# JTAG_-V1_6-ASCII.net
KiCad netlist of a schematic drawn in Altium Designer
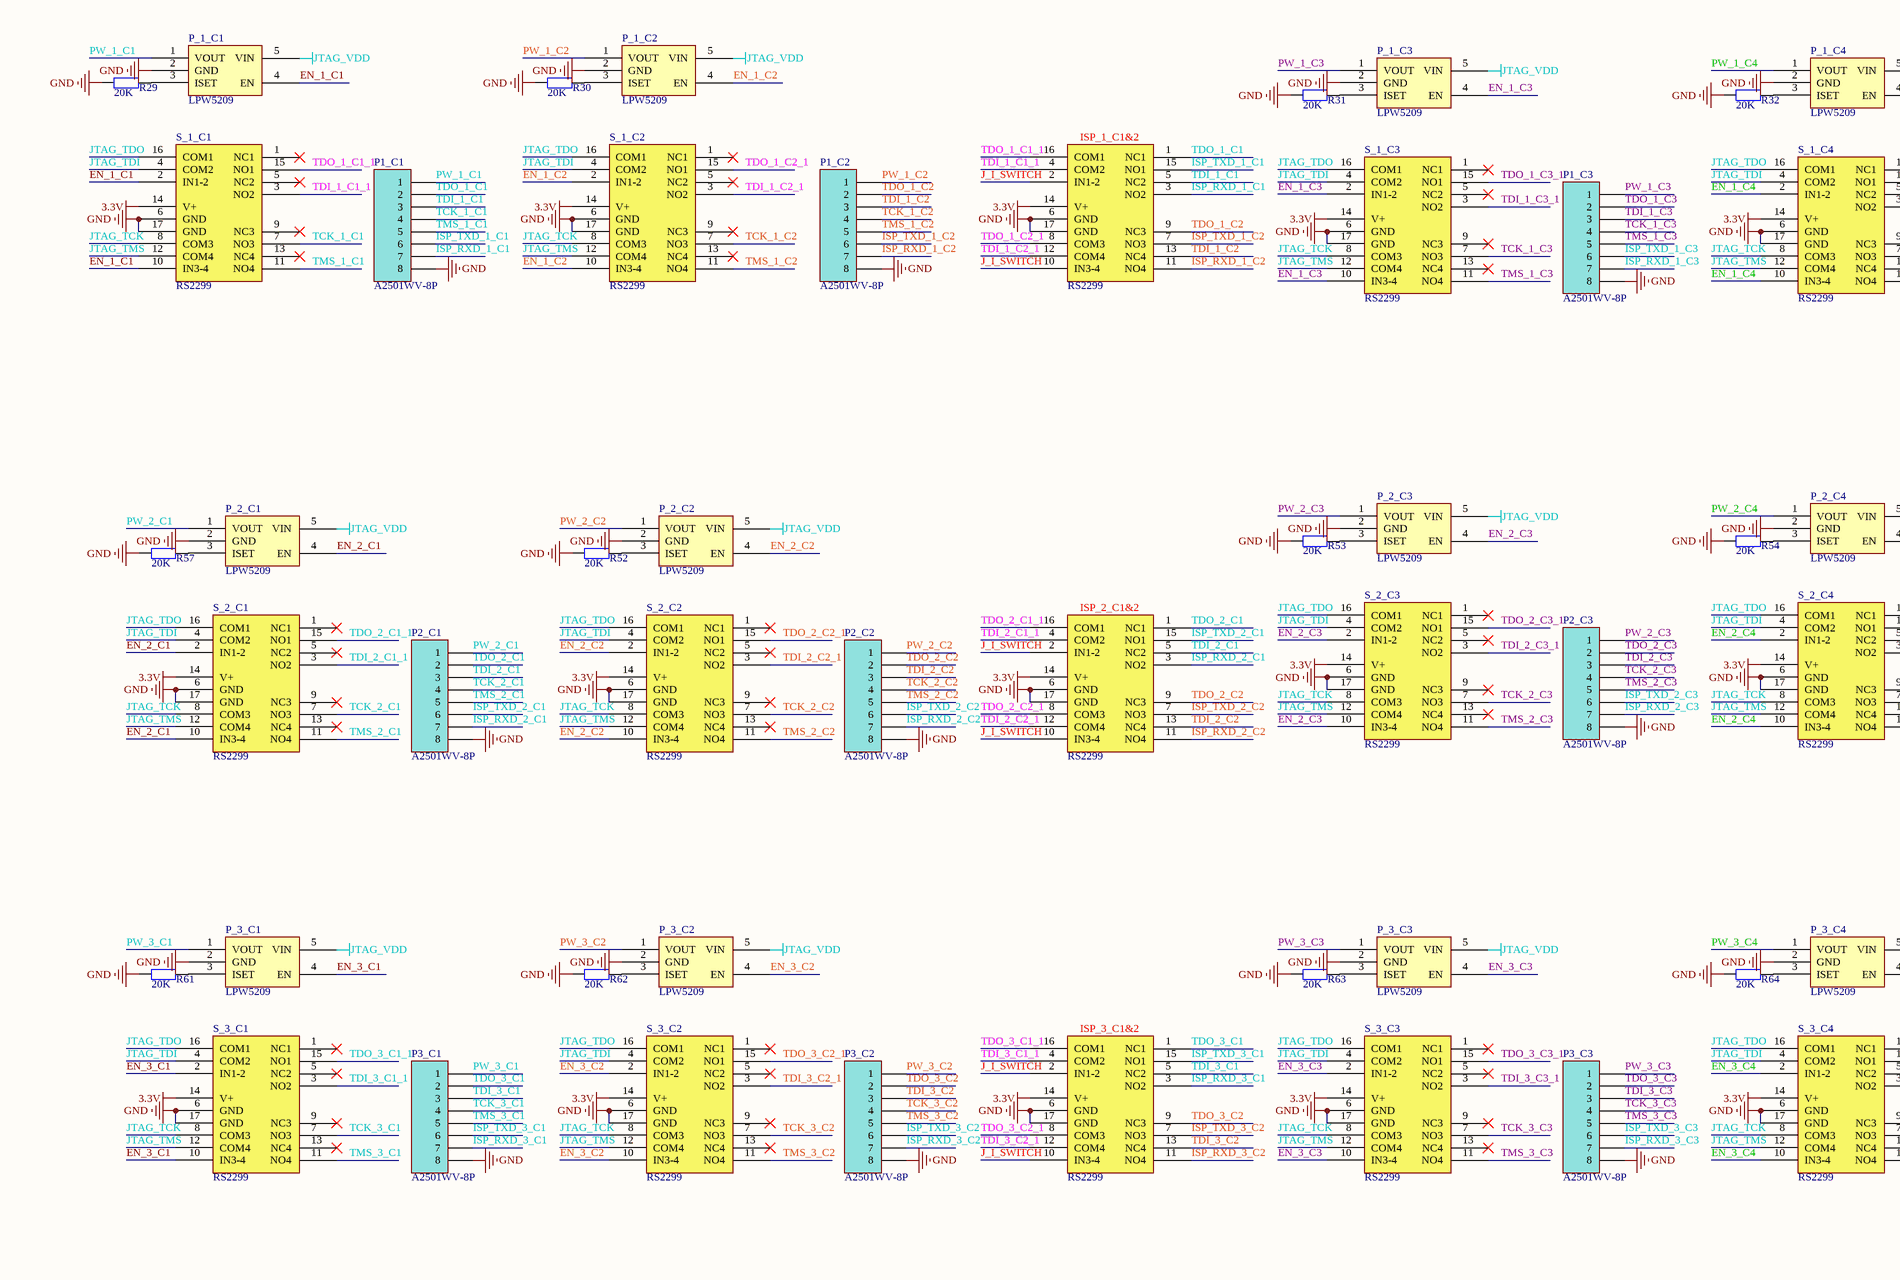
[diagram p0: JTAG批量下载板-V1.6-ASCII.SchDoc, top left]
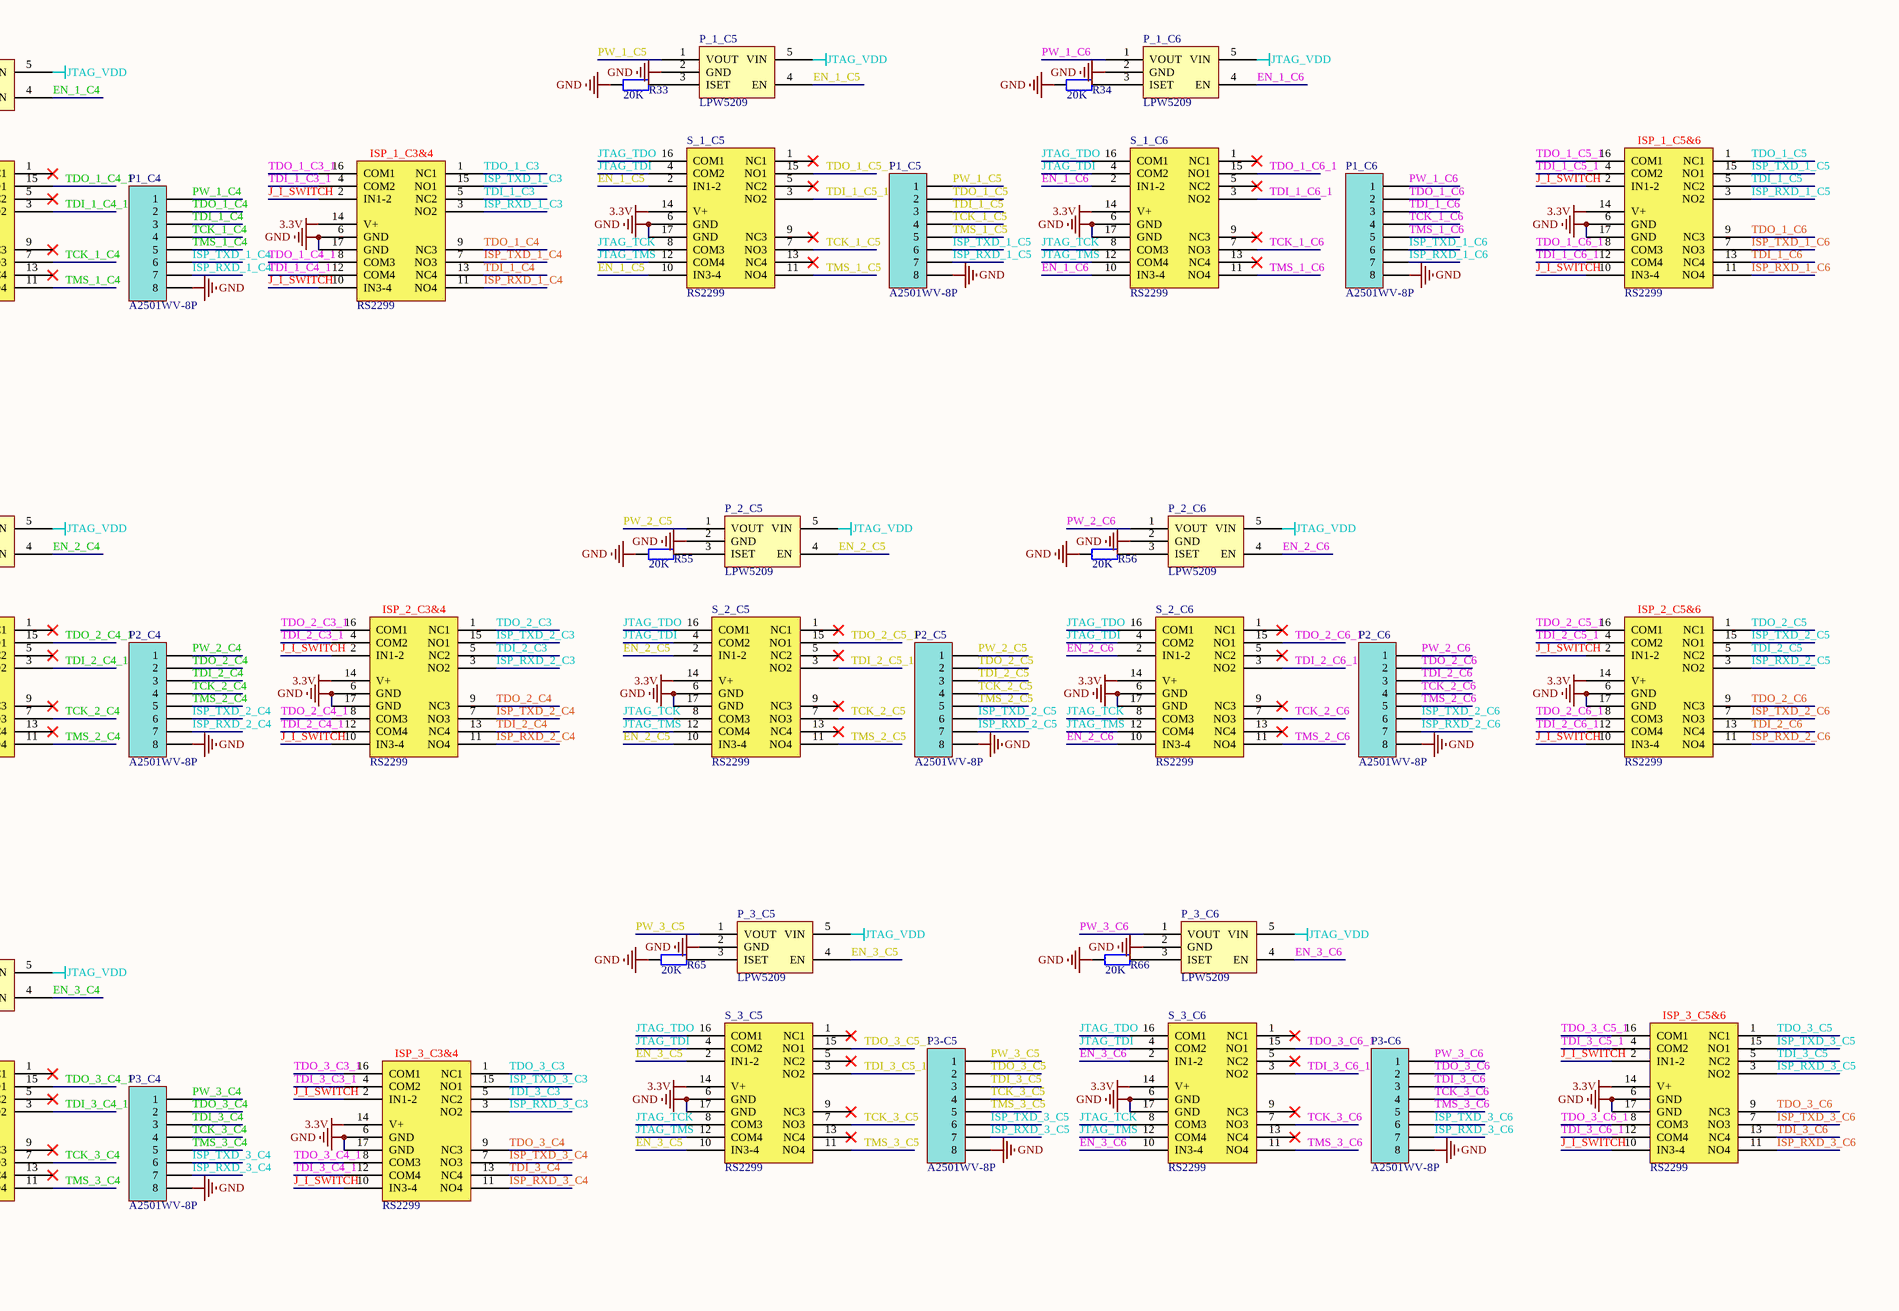
[diagram p1: JTAG批量下载板-V1.6-ASCII.SchDoc, top right]
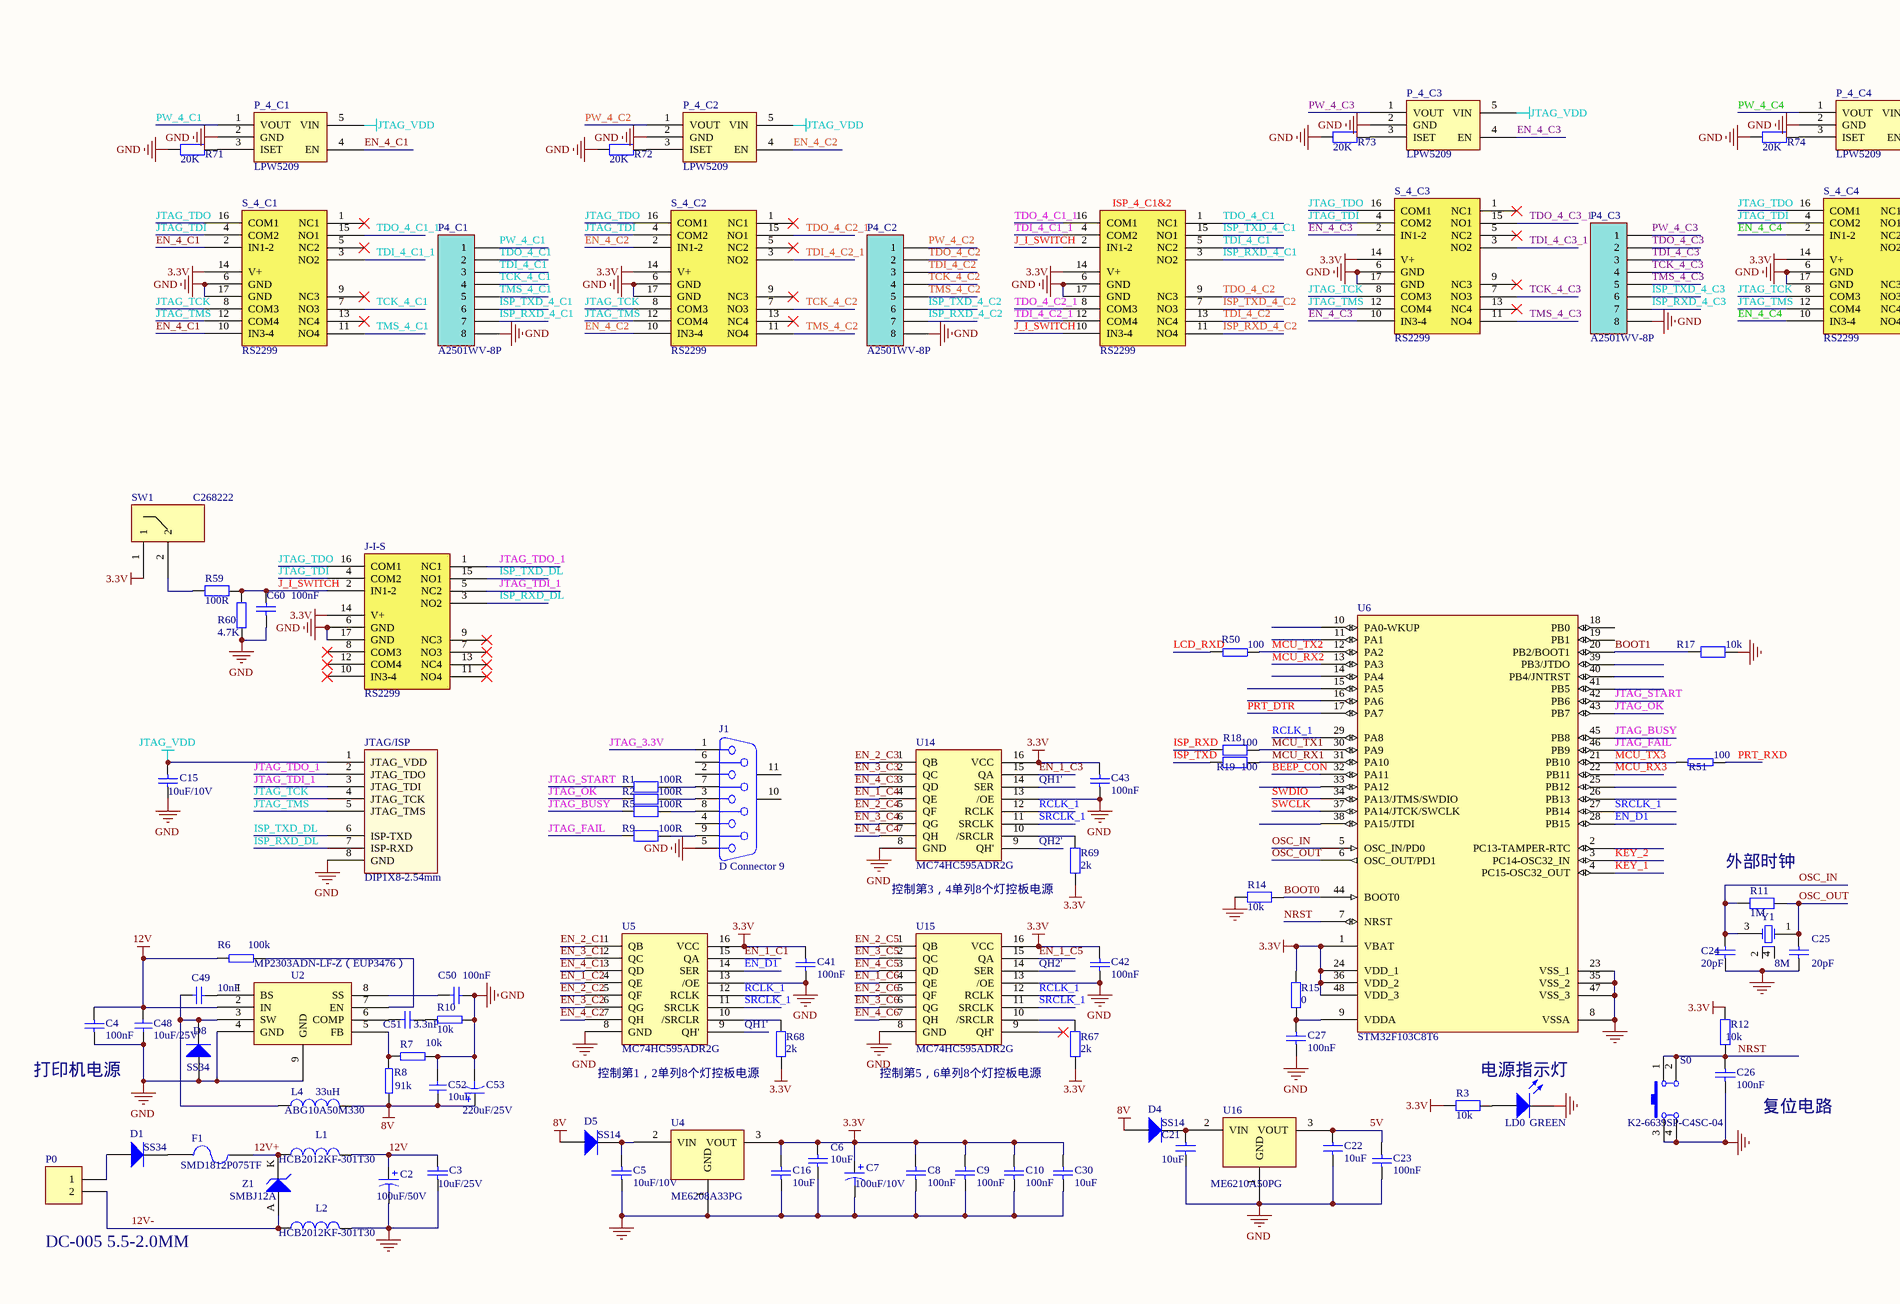
[diagram p2: JTAG批量下载板-V1.6-ASCII.SchDoc, bottom left]
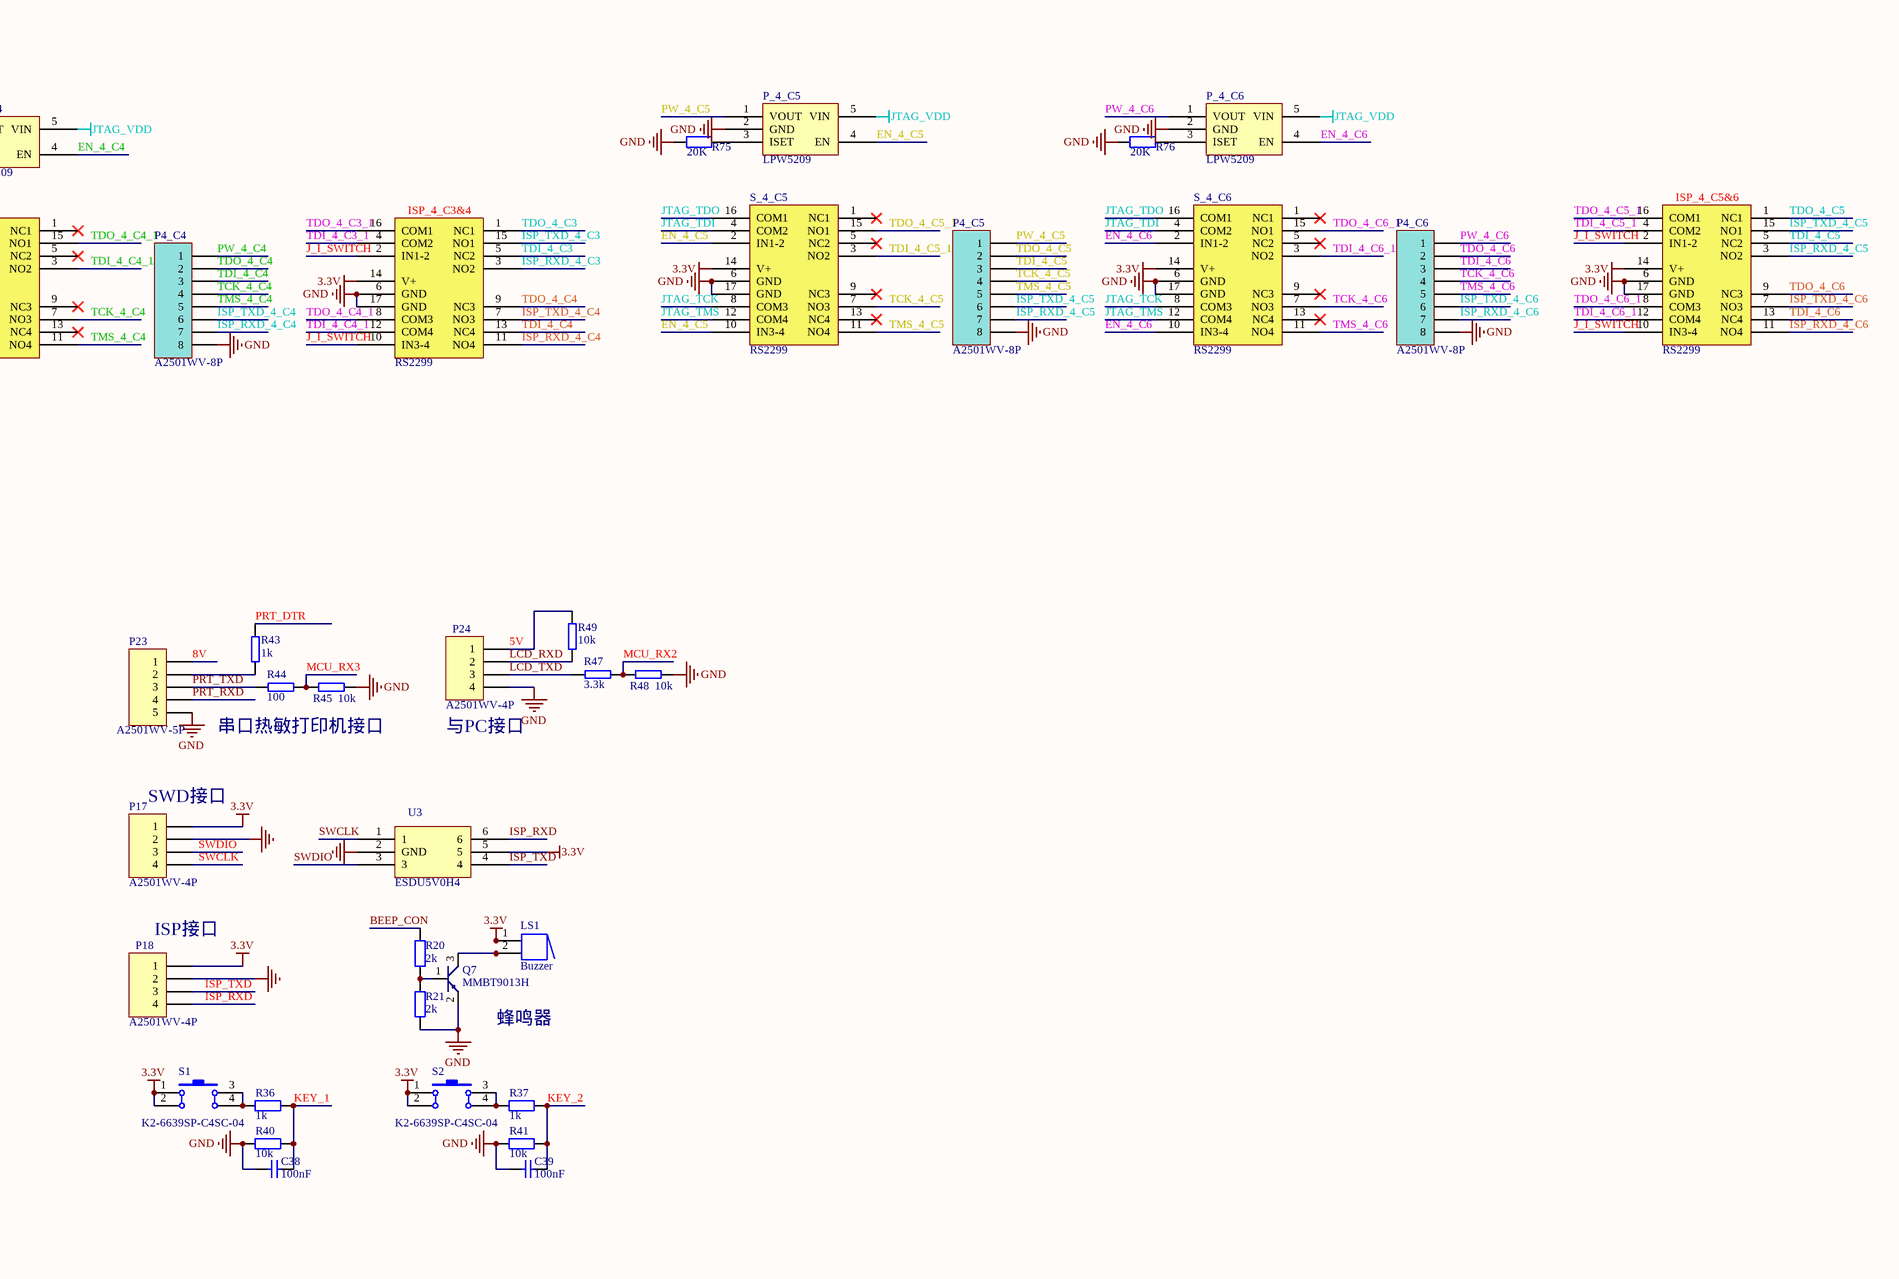
[diagram p3: JTAG批量下载板-V1.6-ASCII.SchDoc, bottom right]

(export (version "E")
  (design (tool "Eeschema 10.0.6"))
  (components
    (comp (ref "C2")
      (value "100uF/50V")
      (footprint "RB-6*9")
      (description "Polarized Capacitor (Radial)")
      (fields (field (name "PUBLISHER") "Altium Limited"))
      (libsource (lib "Miscellaneous Devices") (part "Cap Pol1"))
    )
    (comp (ref "C3")
      (value "10uF/25V")
      (footprint "C0805")
      (description "Capacitor")
      (fields (field (name "PUBLISHER") "Altium Limited"))
      (libsource (lib "Miscellaneous Devices") (part "Cap"))
    )
    (comp (ref "C4")
      (value "100nF")
      (footprint "C0603")
      (description "Capacitor")
      (fields (field (name "PUBLISHER") "Altium Limited"))
      (libsource (lib "Miscellaneous Devices") (part "Cap"))
    )
    (comp (ref "C5")
      (value "10uF/10V")
      (footprint "C0603")
      (description "Capacitor")
      (fields (field (name "PUBLISHER") "Altium Limited"))
      (libsource (lib "Miscellaneous Devices") (part "Cap"))
    )
    (comp (ref "C6")
      (value "10uF")
      (footprint "C0603")
      (description "Capacitor")
      (fields (field (name "PUBLISHER") "Altium Limited"))
      (libsource (lib "Miscellaneous Devices") (part "Cap"))
    )
    (comp (ref "C7")
      (value "100uF/10V")
      (footprint "C3528")
      (description "Polarized Capacitor (Radial)")
      (fields (field (name "PUBLISHER") "Altium Limited"))
      (libsource (lib "Miscellaneous Devices") (part "Cap Pol1"))
    )
    (comp (ref "C8")
      (value "100nF")
      (footprint "C0603")
      (description "Capacitor")
      (fields (field (name "PUBLISHER") "Altium Limited"))
      (libsource (lib "Miscellaneous Devices") (part "Cap"))
    )
    (comp (ref "C9")
      (value "100nF")
      (footprint "C0603")
      (description "Capacitor")
      (fields (field (name "PUBLISHER") "Altium Limited"))
      (libsource (lib "Miscellaneous Devices") (part "Cap"))
    )
    (comp (ref "C10")
      (value "100nF")
      (footprint "C0603")
      (description "Capacitor")
      (fields (field (name "PUBLISHER") "Altium Limited"))
      (libsource (lib "Miscellaneous Devices") (part "Cap"))
    )
    (comp (ref "C15")
      (value "10uF/10V")
      (footprint "C0603")
      (description "Capacitor")
      (fields (field (name "PUBLISHER") "Altium Limited"))
      (libsource (lib "Miscellaneous Devices") (part "Cap"))
    )
    (comp (ref "C16")
      (value "10uF")
      (footprint "C0603")
      (description "Capacitor")
      (fields (field (name "PUBLISHER") "Altium Limited"))
      (libsource (lib "Miscellaneous Devices") (part "Cap"))
    )
    (comp (ref "C21")
      (value "10uF")
      (footprint "C0603")
      (description "Capacitor")
      (fields (field (name "PUBLISHER") "Altium Limited"))
      (libsource (lib "Miscellaneous Devices") (part "Cap"))
    )
    (comp (ref "C22")
      (value "10uF")
      (footprint "C0603")
      (description "Capacitor")
      (fields (field (name "PUBLISHER") "Altium Limited"))
      (libsource (lib "Miscellaneous Devices") (part "Cap"))
    )
    (comp (ref "C23")
      (value "100nF")
      (footprint "C0603")
      (description "Capacitor")
      (fields (field (name "PUBLISHER") "Altium Limited"))
      (libsource (lib "Miscellaneous Devices") (part "Cap"))
    )
    (comp (ref "C24")
      (value "20pF")
      (footprint "C0603")
      (description "Capacitor")
      (fields (field (name "PUBLISHER") "Altium Limited"))
      (libsource (lib "Miscellaneous Devices") (part "Cap"))
    )
    (comp (ref "C25")
      (value "20pF")
      (footprint "C0603")
      (description "Capacitor")
      (fields (field (name "PUBLISHER") "Altium Limited"))
      (libsource (lib "Miscellaneous Devices") (part "Cap"))
    )
    (comp (ref "C26")
      (value "100nF")
      (footprint "C0603")
      (description "Capacitor")
      (fields (field (name "PUBLISHER") "Altium Limited"))
      (libsource (lib "Miscellaneous Devices") (part "Cap"))
    )
    (comp (ref "C27")
      (value "100nF")
      (footprint "C0603")
      (description "Capacitor")
      (fields (field (name "PUBLISHER") "Altium Limited"))
      (libsource (lib "Miscellaneous Devices") (part "Cap"))
    )
    (comp (ref "C30")
      (value "10uF")
      (footprint "C0603")
      (description "Capacitor")
      (fields (field (name "PUBLISHER") "Altium Limited"))
      (libsource (lib "Miscellaneous Devices") (part "Cap"))
    )
    (comp (ref "C38")
      (value "100nF")
      (footprint "C0603")
      (description "电容器")
      (libsource (lib "*") (part "Capacitor"))
    )
    (comp (ref "C39")
      (value "100nF")
      (footprint "C0603")
      (description "电容器")
      (libsource (lib "*") (part "Capacitor"))
    )
    (comp (ref "C41")
      (value "100nF")
      (footprint "C0603")
      (description "Capacitor")
      (fields (field (name "PUBLISHER") "Altium Limited"))
      (libsource (lib "Miscellaneous Devices") (part "Cap"))
    )
    (comp (ref "C42")
      (value "100nF")
      (footprint "C0603")
      (description "Capacitor")
      (fields (field (name "PUBLISHER") "Altium Limited"))
      (libsource (lib "Miscellaneous Devices") (part "Cap"))
    )
    (comp (ref "C43")
      (value "100nF")
      (footprint "C0603")
      (description "Capacitor")
      (fields (field (name "PUBLISHER") "Altium Limited"))
      (libsource (lib "Miscellaneous Devices") (part "Cap"))
    )
    (comp (ref "C48")
      (value "10uF/25V")
      (footprint "C0805")
      (description "电容器")
      (libsource (lib "*") (part "Capacitor"))
    )
    (comp (ref "C49")
      (value "10nF")
      (footprint "C0603")
      (description "电容器")
      (libsource (lib "*") (part "Capacitor"))
    )
    (comp (ref "C50")
      (value "100nF")
      (footprint "C0603")
      (description "电容器")
      (libsource (lib "*") (part "Capacitor"))
    )
    (comp (ref "C51")
      (value "3.3nF")
      (footprint "C0603")
      (description "电容器")
      (libsource (lib "*") (part "Capacitor"))
    )
    (comp (ref "C52")
      (value "10uF")
      (footprint "C0603")
      (description "电容器")
      (libsource (lib "*") (part "Capacitor"))
    )
    (comp (ref "C53")
      (value "220uF/25V")
      (footprint "RB-6*9")
      (description "Polarized Capacitor (Radial)")
      (fields (field (name "PUBLISHER") "Altium Limited"))
      (libsource (lib "Miscellaneous Devices") (part "Cap Pol1"))
    )
    (comp (ref "C60")
      (value "100nF")
      (footprint "C0603")
      (description "Capacitor")
      (fields (field (name "PUBLISHER") "Altium Limited"))
      (libsource (lib "Miscellaneous Devices") (part "Cap"))
    )
    (comp (ref "D1")
      (value "SS34")
      (footprint "SMB")
      (description "1 Amp General Purpose Rectifier")
      (fields (field (name "PUBLISHER") "Altium Limited"))
      (libsource (lib "Miscellaneous Devices") (part "Diode 1N4001"))
    )
    (comp (ref "D4")
      (value "SS14")
      (footprint "SOD-123F")
      (description "1 Amp General Purpose Rectifier")
      (fields (field (name "PUBLISHER") "Altium Limited"))
      (libsource (lib "Miscellaneous Devices") (part "Diode 1N4001"))
    )
    (comp (ref "D5")
      (value "SS14")
      (footprint "SOD-123F")
      (description "1 Amp General Purpose Rectifier")
      (fields (field (name "PUBLISHER") "Altium Limited"))
      (libsource (lib "Miscellaneous Devices") (part "Diode 1N4001"))
    )
    (comp (ref "D8")
      (value "SS34")
      (footprint "SMB")
      (description "通用二极管")
      (fields (field (name "PUBLISHER") "Altium Limited"))
      (libsource (lib "*") (part "Diode"))
    )
    (comp (ref "F1")
      (value "SMD1812P075TF")
      (footprint "1812")
      (description "Fuse")
      (fields (field (name "PUBLISHER") "Altium Limited"))
      (libsource (lib "Miscellaneous Devices") (part "Fuse 2"))
    )
    (comp (ref "ISP_1_C1&2")
      (value "RS2299")
      (footprint "QFN16")
      (libsource (lib "JTAG批量下载板-V0.5") (part "RS2299"))
    )
    (comp (ref "ISP_1_C3&4")
      (value "RS2299")
      (footprint "QFN16")
      (libsource (lib "JTAG批量下载板-V0.5") (part "RS2299"))
    )
    (comp (ref "ISP_1_C5&6")
      (value "RS2299")
      (footprint "QFN16")
      (libsource (lib "JTAG批量下载板-V0.5") (part "RS2299"))
    )
    (comp (ref "ISP_2_C1&2")
      (value "RS2299")
      (footprint "QFN16")
      (libsource (lib "JTAG批量下载板-V0.5") (part "RS2299"))
    )
    (comp (ref "ISP_2_C3&4")
      (value "RS2299")
      (footprint "QFN16")
      (libsource (lib "JTAG批量下载板-V0.5") (part "RS2299"))
    )
    (comp (ref "ISP_2_C5&6")
      (value "RS2299")
      (footprint "QFN16")
      (libsource (lib "JTAG批量下载板-V0.5") (part "RS2299"))
    )
    (comp (ref "ISP_3_C1&2")
      (value "RS2299")
      (footprint "QFN16")
      (libsource (lib "JTAG批量下载板-V0.5") (part "RS2299"))
    )
    (comp (ref "ISP_3_C3&4")
      (value "RS2299")
      (footprint "QFN16")
      (libsource (lib "JTAG批量下载板-V0.5") (part "RS2299"))
    )
    (comp (ref "ISP_3_C5&6")
      (value "RS2299")
      (footprint "QFN16")
      (libsource (lib "JTAG批量下载板-V0.5") (part "RS2299"))
    )
    (comp (ref "ISP_4_C1&2")
      (value "RS2299")
      (footprint "QFN16")
      (libsource (lib "JTAG批量下载板-V0.5") (part "RS2299"))
    )
    (comp (ref "ISP_4_C3&4")
      (value "RS2299")
      (footprint "QFN16")
      (libsource (lib "JTAG批量下载板-V0.5") (part "RS2299"))
    )
    (comp (ref "ISP_4_C5&6")
      (value "RS2299")
      (footprint "QFN16")
      (libsource (lib "JTAG批量下载板-V0.5") (part "RS2299"))
    )
    (comp (ref "J-I-S")
      (value "RS2299")
      (footprint "QFN16")
      (libsource (lib "JTAG批量下载板-V0.5") (part "RS2299"))
    )
    (comp (ref "J1")
      (value "D Connector 9")
      (footprint "DSUB1.385-2H9")
      (description "Receptacle Assembly, 9 Position, Right Angle")
      (fields (field (name "PUBLISHER") "Altium Limited"))
      (libsource (lib "Miscellaneous Connectors") (part "D Connector 9"))
    )
    (comp (ref "JTAG/ISP")
      (value "DIP1X8-2.54mm")
      (footprint "XH2.5-8P")
      (libsource (lib "JTAG批量下载板-V1.0") (part "DIP1X6-2.54mm"))
    )
    (comp (ref "L1")
      (value "HCB2012KF-301T30")
      (footprint "R0805")
      (description "Inductor")
      (fields (field (name "PUBLISHER") "Altium Limited"))
      (libsource (lib "Miscellaneous Devices") (part "Inductor"))
    )
    (comp (ref "L2")
      (value "HCB2012KF-301T30")
      (footprint "R0805")
      (description "Inductor")
      (fields (field (name "PUBLISHER") "Altium Limited"))
      (libsource (lib "Miscellaneous Devices") (part "Inductor"))
    )
    (comp (ref "L4")
      (value "33uH")
      (footprint "L1040")
      (description "Inductor")
      (fields (field (name "ALTIUM_VALUE") "ABG10A50M330") (field (name "PUBLISHER") "Altium Limited"))
      (libsource (lib "") (part "Inductor_1"))
    )
    (comp (ref "LD0")
      (value "GREEN")
      (footprint "LED-0603")
      (description "LED灯")
      (fields (field (name "PUBLISHER") "Altium Limited"))
      (libsource (lib "*") (part "LED0"))
    )
    (comp (ref "LS1")
      (value "Buzzer")
      (footprint "BUZZER-small")
      (description "Magnetic Transducer Buzzer")
      (fields (field (name "PUBLISHER") "Altium Limited"))
      (libsource (lib "JTAG-1") (part "Buzzer"))
    )
    (comp (ref "P0")
      (value "DC-005 5.5-2.0MM")
      (footprint "DC-005A")
      (description "Header, 2-Pin")
      (fields (field (name "PUBLISHER") "Altium Limited"))
      (libsource (lib "Miscellaneous Connectors") (part "Header 2"))
    )
    (comp (ref "P1_C1")
      (value "A2501WV-8P")
      (footprint "XH2.5-8P")
      (description "Header, 6-Pin")
      (fields (field (name "PUBLISHER") "Altium Limited"))
      (libsource (lib "JTAG批量下载板-V1.0") (part "Header 8"))
    )
    (comp (ref "P1_C2")
      (value "A2501WV-8P")
      (footprint "XH2.5-8P")
      (description "Header, 6-Pin")
      (fields (field (name "PUBLISHER") "Altium Limited"))
      (libsource (lib "JTAG批量下载板-V1.0") (part "Header 8"))
    )
    (comp (ref "P1_C3")
      (value "A2501WV-8P")
      (footprint "XH2.5-8P")
      (description "Header, 6-Pin")
      (fields (field (name "PUBLISHER") "Altium Limited"))
      (libsource (lib "JTAG批量下载板-V1.0") (part "Header 8"))
    )
    (comp (ref "P1_C4")
      (value "A2501WV-8P")
      (footprint "XH2.5-8P")
      (description "Header, 6-Pin")
      (fields (field (name "PUBLISHER") "Altium Limited"))
      (libsource (lib "JTAG批量下载板-V1.0") (part "Header 8"))
    )
    (comp (ref "P1_C5")
      (value "A2501WV-8P")
      (footprint "XH2.5-8P")
      (description "Header, 6-Pin")
      (fields (field (name "PUBLISHER") "Altium Limited"))
      (libsource (lib "JTAG批量下载板-V1.0") (part "Header 8"))
    )
    (comp (ref "P1_C6")
      (value "A2501WV-8P")
      (footprint "XH2.5-8P")
      (description "Header, 6-Pin")
      (fields (field (name "PUBLISHER") "Altium Limited"))
      (libsource (lib "JTAG批量下载板-V1.0") (part "Header 8"))
    )
    (comp (ref "P2_C1")
      (value "A2501WV-8P")
      (footprint "XH2.5-8P")
      (description "Header, 6-Pin")
      (fields (field (name "PUBLISHER") "Altium Limited"))
      (libsource (lib "JTAG批量下载板-V1.0") (part "Header 8"))
    )
    (comp (ref "P2_C2")
      (value "A2501WV-8P")
      (footprint "XH2.5-8P")
      (description "Header, 6-Pin")
      (fields (field (name "PUBLISHER") "Altium Limited"))
      (libsource (lib "JTAG批量下载板-V1.0") (part "Header 8"))
    )
    (comp (ref "P2_C3")
      (value "A2501WV-8P")
      (footprint "XH2.5-8P")
      (description "Header, 6-Pin")
      (fields (field (name "PUBLISHER") "Altium Limited"))
      (libsource (lib "JTAG批量下载板-V1.0") (part "Header 8"))
    )
    (comp (ref "P2_C4")
      (value "A2501WV-8P")
      (footprint "XH2.5-8P")
      (description "Header, 6-Pin")
      (fields (field (name "PUBLISHER") "Altium Limited"))
      (libsource (lib "JTAG批量下载板-V1.0") (part "Header 8"))
    )
    (comp (ref "P2_C5")
      (value "A2501WV-8P")
      (footprint "XH2.5-8P")
      (description "Header, 6-Pin")
      (fields (field (name "PUBLISHER") "Altium Limited"))
      (libsource (lib "JTAG批量下载板-V1.0") (part "Header 8"))
    )
    (comp (ref "P2_C6")
      (value "A2501WV-8P")
      (footprint "XH2.5-8P")
      (description "Header, 6-Pin")
      (fields (field (name "PUBLISHER") "Altium Limited"))
      (libsource (lib "JTAG批量下载板-V1.0") (part "Header 8"))
    )
    (comp (ref "P3-C5")
      (value "A2501WV-8P")
      (footprint "XH2.5-8P")
      (description "Header, 6-Pin")
      (fields (field (name "PUBLISHER") "Altium Limited"))
      (libsource (lib "JTAG批量下载板-V1.0") (part "Header 8"))
    )
    (comp (ref "P3-C6")
      (value "A2501WV-8P")
      (footprint "XH2.5-8P")
      (description "Header, 6-Pin")
      (fields (field (name "PUBLISHER") "Altium Limited"))
      (libsource (lib "JTAG批量下载板-V1.0") (part "Header 8"))
    )
    (comp (ref "P3_C1")
      (value "A2501WV-8P")
      (footprint "XH2.5-8P")
      (description "Header, 6-Pin")
      (fields (field (name "PUBLISHER") "Altium Limited"))
      (libsource (lib "JTAG批量下载板-V1.0") (part "Header 8"))
    )
    (comp (ref "P3_C2")
      (value "A2501WV-8P")
      (footprint "XH2.5-8P")
      (description "Header, 6-Pin")
      (fields (field (name "PUBLISHER") "Altium Limited"))
      (libsource (lib "JTAG批量下载板-V1.0") (part "Header 8"))
    )
    (comp (ref "P3_C3")
      (value "A2501WV-8P")
      (footprint "XH2.5-8P")
      (description "Header, 6-Pin")
      (fields (field (name "PUBLISHER") "Altium Limited"))
      (libsource (lib "JTAG批量下载板-V1.0") (part "Header 8"))
    )
    (comp (ref "P3_C4")
      (value "A2501WV-8P")
      (footprint "XH2.5-8P")
      (description "Header, 6-Pin")
      (fields (field (name "PUBLISHER") "Altium Limited"))
      (libsource (lib "JTAG批量下载板-V1.0") (part "Header 8"))
    )
    (comp (ref "P4_C1")
      (value "A2501WV-8P")
      (footprint "XH2.5-8P")
      (description "Header, 6-Pin")
      (fields (field (name "PUBLISHER") "Altium Limited"))
      (libsource (lib "JTAG批量下载板-V1.0") (part "Header 8"))
    )
    (comp (ref "P4_C2")
      (value "A2501WV-8P")
      (footprint "XH2.5-8P")
      (description "Header, 6-Pin")
      (fields (field (name "PUBLISHER") "Altium Limited"))
      (libsource (lib "JTAG批量下载板-V1.0") (part "Header 8"))
    )
    (comp (ref "P4_C3")
      (value "A2501WV-8P")
      (footprint "XH2.5-8P")
      (description "Header, 6-Pin")
      (fields (field (name "PUBLISHER") "Altium Limited"))
      (libsource (lib "JTAG批量下载板-V1.0") (part "Header 8"))
    )
    (comp (ref "P4_C4")
      (value "A2501WV-8P")
      (footprint "XH2.5-8P")
      (description "Header, 6-Pin")
      (fields (field (name "PUBLISHER") "Altium Limited"))
      (libsource (lib "JTAG批量下载板-V1.0") (part "Header 8"))
    )
    (comp (ref "P4_C5")
      (value "A2501WV-8P")
      (footprint "XH2.5-8P")
      (description "Header, 6-Pin")
      (fields (field (name "PUBLISHER") "Altium Limited"))
      (libsource (lib "JTAG批量下载板-V1.0") (part "Header 8"))
    )
    (comp (ref "P4_C6")
      (value "A2501WV-8P")
      (footprint "XH2.5-8P")
      (description "Header, 6-Pin")
      (fields (field (name "PUBLISHER") "Altium Limited"))
      (libsource (lib "JTAG批量下载板-V1.0") (part "Header 8"))
    )
    (comp (ref "P17")
      (value "A2501WV-4P")
      (footprint "XH2.5-4P")
      (description "Header, 4-Pin")
      (fields (field (name "PUBLISHER") "Altium Limited"))
      (libsource (lib "*") (part "Header 4"))
    )
    (comp (ref "P18")
      (value "A2501WV-4P")
      (footprint "XH2.5-4P")
      (description "Header, 4-Pin")
      (fields (field (name "PUBLISHER") "Altium Limited"))
      (libsource (lib "*") (part "Header 4"))
    )
    (comp (ref "P23")
      (value "A2501WV-5P")
      (footprint "XH2.5-5P")
      (description "Header, 5-Pin")
      (fields (field (name "PUBLISHER") "Altium Limited"))
      (libsource (lib "Miscellaneous Connectors") (part "Header 5"))
    )
    (comp (ref "P24")
      (value "A2501WV-4P")
      (footprint "XH2.5-4P")
      (description "Header, 4-Pin")
      (fields (field (name "PUBLISHER") "Altium Limited"))
      (libsource (lib "*") (part "Header 4"))
    )
    (comp (ref "P_1_C1")
      (value "LPW5209")
      (footprint "SOT-23-5")
      (libsource (lib "JTAG批量下载板-V0.1") (part "LPW5209"))
    )
    (comp (ref "P_1_C2")
      (value "LPW5209")
      (footprint "SOT-23-5")
      (libsource (lib "JTAG批量下载板-V0.1") (part "LPW5209"))
    )
    (comp (ref "P_1_C3")
      (value "LPW5209")
      (footprint "SOT-23-5")
      (libsource (lib "JTAG批量下载板-V0.1") (part "LPW5209"))
    )
    (comp (ref "P_1_C4")
      (value "LPW5209")
      (footprint "SOT-23-5")
      (libsource (lib "JTAG批量下载板-V0.1") (part "LPW5209"))
    )
    (comp (ref "P_1_C5")
      (value "LPW5209")
      (footprint "SOT-23-5")
      (libsource (lib "JTAG批量下载板-V0.1") (part "LPW5209"))
    )
    (comp (ref "P_1_C6")
      (value "LPW5209")
      (footprint "SOT-23-5")
      (libsource (lib "JTAG批量下载板-V0.1") (part "LPW5209"))
    )
    (comp (ref "P_2_C1")
      (value "LPW5209")
      (footprint "SOT-23-5")
      (libsource (lib "JTAG批量下载板-V0.1") (part "LPW5209"))
    )
    (comp (ref "P_2_C2")
      (value "LPW5209")
      (footprint "SOT-23-5")
      (libsource (lib "JTAG批量下载板-V0.1") (part "LPW5209"))
    )
    (comp (ref "P_2_C3")
      (value "LPW5209")
      (footprint "SOT-23-5")
      (libsource (lib "JTAG批量下载板-V0.1") (part "LPW5209"))
    )
    (comp (ref "P_2_C4")
      (value "LPW5209")
      (footprint "SOT-23-5")
      (libsource (lib "JTAG批量下载板-V0.1") (part "LPW5209"))
    )
    (comp (ref "P_2_C5")
      (value "LPW5209")
      (footprint "SOT-23-5")
      (libsource (lib "JTAG批量下载板-V0.1") (part "LPW5209"))
    )
    (comp (ref "P_2_C6")
      (value "LPW5209")
      (footprint "SOT-23-5")
      (libsource (lib "JTAG批量下载板-V0.1") (part "LPW5209"))
    )
    (comp (ref "P_3_C1")
      (value "LPW5209")
      (footprint "SOT-23-5")
      (libsource (lib "JTAG批量下载板-V0.1") (part "LPW5209"))
    )
    (comp (ref "P_3_C2")
      (value "LPW5209")
      (footprint "SOT-23-5")
      (libsource (lib "JTAG批量下载板-V0.1") (part "LPW5209"))
    )
    (comp (ref "P_3_C3")
      (value "LPW5209")
      (footprint "SOT-23-5")
      (libsource (lib "JTAG批量下载板-V0.1") (part "LPW5209"))
    )
    (comp (ref "P_3_C4")
      (value "LPW5209")
      (footprint "SOT-23-5")
      (libsource (lib "JTAG批量下载板-V0.1") (part "LPW5209"))
    )
    (comp (ref "P_3_C5")
      (value "LPW5209")
      (footprint "SOT-23-5")
      (libsource (lib "JTAG批量下载板-V0.1") (part "LPW5209"))
    )
    (comp (ref "P_3_C6")
      (value "LPW5209")
      (footprint "SOT-23-5")
      (libsource (lib "JTAG批量下载板-V0.1") (part "LPW5209"))
    )
    (comp (ref "P_4_C1")
      (value "LPW5209")
      (footprint "SOT-23-5")
      (libsource (lib "JTAG批量下载板-V0.1") (part "LPW5209"))
    )
    (comp (ref "P_4_C2")
      (value "LPW5209")
      (footprint "SOT-23-5")
      (libsource (lib "JTAG批量下载板-V0.1") (part "LPW5209"))
    )
    (comp (ref "P_4_C3")
      (value "LPW5209")
      (footprint "SOT-23-5")
      (libsource (lib "JTAG批量下载板-V0.1") (part "LPW5209"))
    )
    (comp (ref "P_4_C4")
      (value "LPW5209")
      (footprint "SOT-23-5")
      (libsource (lib "JTAG批量下载板-V0.1") (part "LPW5209"))
    )
    (comp (ref "P_4_C5")
      (value "LPW5209")
      (footprint "SOT-23-5")
      (libsource (lib "JTAG批量下载板-V0.1") (part "LPW5209"))
    )
    (comp (ref "P_4_C6")
      (value "LPW5209")
      (footprint "SOT-23-5")
      (libsource (lib "JTAG批量下载板-V0.1") (part "LPW5209"))
    )
    (comp (ref "Q7")
      (value "MMBT9013H")
      (footprint "SOT-23")
      (description "8050/BCW846/BCW847")
      (libsource (lib "MY_STD_SCH") (part "MY_NPN"))
    )
    (comp (ref "R1")
      (value "100R")
      (footprint "R0603")
      (description "Resistor")
      (fields (field (name "PUBLISHER") "Altium Limited"))
      (libsource (lib "") (part "Res2_1"))
    )
    (comp (ref "R2")
      (value "100R")
      (footprint "R0603")
      (description "Resistor")
      (fields (field (name "PUBLISHER") "Altium Limited"))
      (libsource (lib "") (part "Res2_1"))
    )
    (comp (ref "R3")
      (value "10k")
      (footprint "R0603")
      (description "Resistor")
      (fields (field (name "PUBLISHER") "Altium Limited"))
      (libsource (lib "Miscellaneous Devices") (part "Res2"))
    )
    (comp (ref "R5")
      (value "100R")
      (footprint "R0603")
      (description "Resistor")
      (fields (field (name "PUBLISHER") "Altium Limited"))
      (libsource (lib "") (part "Res2_1"))
    )
    (comp (ref "R6")
      (value "100k")
      (footprint "R0603")
      (description "电阻器")
      (libsource (lib "*") (part "Resistance"))
    )
    (comp (ref "R7")
      (value "10k")
      (footprint "R0603")
      (description "电阻器")
      (libsource (lib "*") (part "Resistance"))
    )
    (comp (ref "R8")
      (value "91k")
      (footprint "R0603")
      (description "电阻器")
      (libsource (lib "*") (part "Resistance"))
    )
    (comp (ref "R9")
      (value "100R")
      (footprint "R0603")
      (description "Resistor")
      (fields (field (name "PUBLISHER") "Altium Limited"))
      (libsource (lib "") (part "Res2_1"))
    )
    (comp (ref "R10")
      (value "10k")
      (footprint "R0603")
      (description "电阻器")
      (libsource (lib "*") (part "Resistance"))
    )
    (comp (ref "R11")
      (value "1M")
      (footprint "R0603")
      (description "Resistor")
      (fields (field (name "PUBLISHER") "Altium Limited"))
      (libsource (lib "Miscellaneous Devices") (part "Res2"))
    )
    (comp (ref "R12")
      (value "10k")
      (footprint "R0603")
      (description "Resistor")
      (fields (field (name "PUBLISHER") "Altium Limited"))
      (libsource (lib "") (part "Res2_2"))
    )
    (comp (ref "R14")
      (value "10k")
      (footprint "R0603")
      (description "Resistor")
      (fields (field (name "PUBLISHER") "Altium Limited"))
      (libsource (lib "Miscellaneous Devices") (part "Res2"))
    )
    (comp (ref "R15")
      (value "0")
      (footprint "R0603")
      (description "Resistor")
      (fields (field (name "PUBLISHER") "Altium Limited"))
      (libsource (lib "") (part "Res2_2"))
    )
    (comp (ref "R17")
      (value "10k")
      (footprint "R0603")
      (description "Resistor")
      (fields (field (name "PUBLISHER") "Altium Limited"))
      (libsource (lib "") (part "Res2_1"))
    )
    (comp (ref "R18")
      (value "100")
      (footprint "R0603")
      (description "Resistor")
      (fields (field (name "PUBLISHER") "Altium Limited"))
      (libsource (lib "Miscellaneous Devices") (part "Res2"))
    )
    (comp (ref "R19")
      (value "100")
      (footprint "R0603")
      (description "Resistor")
      (fields (field (name "PUBLISHER") "Altium Limited"))
      (libsource (lib "Miscellaneous Devices") (part "Res2"))
    )
    (comp (ref "R20")
      (value "2k")
      (footprint "R0603")
      (description "Resistor")
      (fields (field (name "PUBLISHER") "Altium Limited"))
      (libsource (lib "") (part "Res2_3"))
    )
    (comp (ref "R21")
      (value "2k")
      (footprint "R0603")
      (description "Resistor")
      (fields (field (name "PUBLISHER") "Altium Limited"))
      (libsource (lib "") (part "Res2_2"))
    )
    (comp (ref "R29")
      (value "20K")
      (footprint "R0603")
      (description "Resistor")
      (fields (field (name "PUBLISHER") "Altium Limited"))
      (libsource (lib "") (part "Res2_1"))
    )
    (comp (ref "R30")
      (value "20K")
      (footprint "R0603")
      (description "Resistor")
      (fields (field (name "PUBLISHER") "Altium Limited"))
      (libsource (lib "") (part "Res2_1"))
    )
    (comp (ref "R31")
      (value "20K")
      (footprint "R0603")
      (description "Resistor")
      (fields (field (name "PUBLISHER") "Altium Limited"))
      (libsource (lib "") (part "Res2_1"))
    )
    (comp (ref "R32")
      (value "20K")
      (footprint "R0603")
      (description "Resistor")
      (fields (field (name "PUBLISHER") "Altium Limited"))
      (libsource (lib "") (part "Res2_1"))
    )
    (comp (ref "R33")
      (value "20K")
      (footprint "R0603")
      (description "Resistor")
      (fields (field (name "PUBLISHER") "Altium Limited"))
      (libsource (lib "") (part "Res2_1"))
    )
    (comp (ref "R34")
      (value "20K")
      (footprint "R0603")
      (description "Resistor")
      (fields (field (name "PUBLISHER") "Altium Limited"))
      (libsource (lib "") (part "Res2_1"))
    )
    (comp (ref "R36")
      (value "1k")
      (footprint "R0603")
      (description "Resistor")
      (fields (field (name "PUBLISHER") "Altium Limited"))
      (libsource (lib "") (part "Res2_1"))
    )
    (comp (ref "R37")
      (value "1k")
      (footprint "R0603")
      (description "Resistor")
      (fields (field (name "PUBLISHER") "Altium Limited"))
      (libsource (lib "") (part "Res2_1"))
    )
    (comp (ref "R40")
      (value "10k")
      (footprint "R0603")
      (description "Resistor")
      (fields (field (name "PUBLISHER") "Altium Limited"))
      (libsource (lib "") (part "Res2_1"))
    )
    (comp (ref "R41")
      (value "10k")
      (footprint "R0603")
      (description "Resistor")
      (fields (field (name "PUBLISHER") "Altium Limited"))
      (libsource (lib "") (part "Res2_1"))
    )
    (comp (ref "R43")
      (value "1k")
      (footprint "R0603")
      (description "电阻器")
      (libsource (lib "*") (part "Resistance"))
    )
    (comp (ref "R44")
      (value "100")
      (footprint "R0603")
      (description "电阻器")
      (libsource (lib "*") (part "Resistance"))
    )
    (comp (ref "R45")
      (value "10k")
      (footprint "R0603")
      (description "电阻器")
      (libsource (lib "*") (part "Resistance"))
    )
    (comp (ref "R47")
      (value "3.3k")
      (footprint "R0603")
      (description "电阻器")
      (libsource (lib "*") (part "Resistance"))
    )
    (comp (ref "R48")
      (value "10k")
      (footprint "R0603")
      (description "电阻器")
      (libsource (lib "*") (part "Resistance"))
    )
    (comp (ref "R49")
      (value "10k")
      (footprint "R0603")
      (description "电阻器")
      (libsource (lib "*") (part "Resistance"))
    )
    (comp (ref "R50")
      (value "100")
      (footprint "R0603")
      (description "电阻器")
      (libsource (lib "*") (part "Resistance"))
    )
    (comp (ref "R51")
      (value "100")
      (footprint "R0603")
      (description "电阻器")
      (libsource (lib "*") (part "Resistance"))
    )
    (comp (ref "R52")
      (value "20K")
      (footprint "R0603")
      (description "Resistor")
      (fields (field (name "PUBLISHER") "Altium Limited"))
      (libsource (lib "") (part "Res2_1"))
    )
    (comp (ref "R53")
      (value "20K")
      (footprint "R0603")
      (description "Resistor")
      (fields (field (name "PUBLISHER") "Altium Limited"))
      (libsource (lib "") (part "Res2_1"))
    )
    (comp (ref "R54")
      (value "20K")
      (footprint "R0603")
      (description "Resistor")
      (fields (field (name "PUBLISHER") "Altium Limited"))
      (libsource (lib "") (part "Res2_1"))
    )
    (comp (ref "R55")
      (value "20K")
      (footprint "R0603")
      (description "Resistor")
      (fields (field (name "PUBLISHER") "Altium Limited"))
      (libsource (lib "") (part "Res2_1"))
    )
    (comp (ref "R56")
      (value "20K")
      (footprint "R0603")
      (description "Resistor")
      (fields (field (name "PUBLISHER") "Altium Limited"))
      (libsource (lib "") (part "Res2_1"))
    )
    (comp (ref "R57")
      (value "20K")
      (footprint "R0603")
      (description "Resistor")
      (fields (field (name "PUBLISHER") "Altium Limited"))
      (libsource (lib "") (part "Res2_1"))
    )
    (comp (ref "R59")
      (value "100R")
      (footprint "R0603")
      (description "Resistor")
      (fields (field (name "PUBLISHER") "Altium Limited"))
      (libsource (lib "Miscellaneous Devices") (part "Res2"))
    )
    (comp (ref "R60")
      (value "4.7K")
      (footprint "R0603")
      (description "Resistor")
      (fields (field (name "PUBLISHER") "Altium Limited"))
      (libsource (lib "") (part "Res2_3"))
    )
    (comp (ref "R61")
      (value "20K")
      (footprint "R0603")
      (description "Resistor")
      (fields (field (name "PUBLISHER") "Altium Limited"))
      (libsource (lib "") (part "Res2_1"))
    )
    (comp (ref "R62")
      (value "20K")
      (footprint "R0603")
      (description "Resistor")
      (fields (field (name "PUBLISHER") "Altium Limited"))
      (libsource (lib "") (part "Res2_1"))
    )
    (comp (ref "R63")
      (value "20K")
      (footprint "R0603")
      (description "Resistor")
      (fields (field (name "PUBLISHER") "Altium Limited"))
      (libsource (lib "") (part "Res2_1"))
    )
    (comp (ref "R64")
      (value "20K")
      (footprint "R0603")
      (description "Resistor")
      (fields (field (name "PUBLISHER") "Altium Limited"))
      (libsource (lib "") (part "Res2_1"))
    )
    (comp (ref "R65")
      (value "20K")
      (footprint "R0603")
      (description "Resistor")
      (fields (field (name "PUBLISHER") "Altium Limited"))
      (libsource (lib "") (part "Res2_1"))
    )
    (comp (ref "R66")
      (value "20K")
      (footprint "R0603")
      (description "Resistor")
      (fields (field (name "PUBLISHER") "Altium Limited"))
      (libsource (lib "") (part "Res2_1"))
    )
    (comp (ref "R67")
      (value "2k")
      (footprint "R0603")
      (description "Resistor")
      (fields (field (name "PUBLISHER") "Altium Limited"))
      (libsource (lib "") (part "Res2_2"))
    )
    (comp (ref "R68")
      (value "2k")
      (footprint "R0603")
      (description "Resistor")
      (fields (field (name "PUBLISHER") "Altium Limited"))
      (libsource (lib "") (part "Res2_2"))
    )
    (comp (ref "R69")
      (value "2k")
      (footprint "R0603")
      (description "Resistor")
      (fields (field (name "PUBLISHER") "Altium Limited"))
      (libsource (lib "") (part "Res2_2"))
    )
    (comp (ref "R71")
      (value "20K")
      (footprint "R0603")
      (description "Resistor")
      (fields (field (name "PUBLISHER") "Altium Limited"))
      (libsource (lib "") (part "Res2_1"))
    )
    (comp (ref "R72")
      (value "20K")
      (footprint "R0603")
      (description "Resistor")
      (fields (field (name "PUBLISHER") "Altium Limited"))
      (libsource (lib "") (part "Res2_1"))
    )
    (comp (ref "R73")
      (value "20K")
      (footprint "R0603")
      (description "Resistor")
      (fields (field (name "PUBLISHER") "Altium Limited"))
      (libsource (lib "") (part "Res2_1"))
    )
    (comp (ref "R74")
      (value "20K")
      (footprint "R0603")
      (description "Resistor")
      (fields (field (name "PUBLISHER") "Altium Limited"))
      (libsource (lib "") (part "Res2_1"))
    )
    (comp (ref "R75")
      (value "20K")
      (footprint "R0603")
      (description "Resistor")
      (fields (field (name "PUBLISHER") "Altium Limited"))
      (libsource (lib "") (part "Res2_1"))
    )
    (comp (ref "R76")
      (value "20K")
      (footprint "R0603")
      (description "Resistor")
      (fields (field (name "PUBLISHER") "Altium Limited"))
      (libsource (lib "") (part "Res2_1"))
    )
    (comp (ref "S0")
      (value "K2-6639SP-C4SC-04")
      (footprint "MY_KEYSOP4")
      (description "Switch")
      (fields (field (name "PUBLISHER") "Altium Limited"))
      (libsource (lib "MYSCH") (part "SW-PB-4pin"))
    )
    (comp (ref "S1")
      (value "K2-6639SP-C4SC-04")
      (footprint "MY_KEYSOP4")
      (description "Switch")
      (fields (field (name "PUBLISHER") "Altium Limited"))
      (libsource (lib "MYSCH") (part "SW-PB-4pin"))
    )
    (comp (ref "S2")
      (value "K2-6639SP-C4SC-04")
      (footprint "MY_KEYSOP4")
      (description "Switch")
      (fields (field (name "PUBLISHER") "Altium Limited"))
      (libsource (lib "MYSCH") (part "SW-PB-4pin"))
    )
    (comp (ref "SW1")
      (value "C268222")
      (footprint "MR-1")
      (libsource (lib "JTAG批量下载板-V1.0") (part "C268222"))
    )
    (comp (ref "S_1_C1")
      (value "RS2299")
      (footprint "QFN16")
      (libsource (lib "JTAG批量下载板-V0.5") (part "RS2299"))
    )
    (comp (ref "S_1_C2")
      (value "RS2299")
      (footprint "QFN16")
      (libsource (lib "JTAG批量下载板-V0.5") (part "RS2299"))
    )
    (comp (ref "S_1_C3")
      (value "RS2299")
      (footprint "QFN16")
      (libsource (lib "JTAG批量下载板-V0.5") (part "RS2299"))
    )
    (comp (ref "S_1_C4")
      (value "RS2299")
      (footprint "QFN16")
      (libsource (lib "JTAG批量下载板-V0.5") (part "RS2299"))
    )
    (comp (ref "S_1_C5")
      (value "RS2299")
      (footprint "QFN16")
      (libsource (lib "JTAG批量下载板-V0.5") (part "RS2299"))
    )
    (comp (ref "S_1_C6")
      (value "RS2299")
      (footprint "QFN16")
      (libsource (lib "JTAG批量下载板-V0.5") (part "RS2299"))
    )
    (comp (ref "S_2_C1")
      (value "RS2299")
      (footprint "QFN16")
      (libsource (lib "JTAG批量下载板-V0.5") (part "RS2299"))
    )
    (comp (ref "S_2_C2")
      (value "RS2299")
      (footprint "QFN16")
      (libsource (lib "JTAG批量下载板-V0.5") (part "RS2299"))
    )
    (comp (ref "S_2_C3")
      (value "RS2299")
      (footprint "QFN16")
      (libsource (lib "JTAG批量下载板-V0.5") (part "RS2299"))
    )
    (comp (ref "S_2_C4")
      (value "RS2299")
      (footprint "QFN16")
      (libsource (lib "JTAG批量下载板-V0.5") (part "RS2299"))
    )
    (comp (ref "S_2_C5")
      (value "RS2299")
      (footprint "QFN16")
      (libsource (lib "JTAG批量下载板-V0.5") (part "RS2299"))
    )
    (comp (ref "S_2_C6")
      (value "RS2299")
      (footprint "QFN16")
      (libsource (lib "JTAG批量下载板-V0.5") (part "RS2299"))
    )
    (comp (ref "S_3_C1")
      (value "RS2299")
      (footprint "QFN16")
      (libsource (lib "JTAG批量下载板-V0.5") (part "RS2299"))
    )
    (comp (ref "S_3_C2")
      (value "RS2299")
      (footprint "QFN16")
      (libsource (lib "JTAG批量下载板-V0.5") (part "RS2299"))
    )
    (comp (ref "S_3_C3")
      (value "RS2299")
      (footprint "QFN16")
      (libsource (lib "JTAG批量下载板-V0.5") (part "RS2299"))
    )
    (comp (ref "S_3_C4")
      (value "RS2299")
      (footprint "QFN16")
      (libsource (lib "JTAG批量下载板-V0.5") (part "RS2299"))
    )
    (comp (ref "S_3_C5")
      (value "RS2299")
      (footprint "QFN16")
      (libsource (lib "JTAG批量下载板-V0.5") (part "RS2299"))
    )
    (comp (ref "S_3_C6")
      (value "RS2299")
      (footprint "QFN16")
      (libsource (lib "JTAG批量下载板-V0.5") (part "RS2299"))
    )
    (comp (ref "S_4_C1")
      (value "RS2299")
      (footprint "QFN16")
      (libsource (lib "JTAG批量下载板-V0.5") (part "RS2299"))
    )
    (comp (ref "S_4_C2")
      (value "RS2299")
      (footprint "QFN16")
      (libsource (lib "JTAG批量下载板-V0.5") (part "RS2299"))
    )
    (comp (ref "S_4_C3")
      (value "RS2299")
      (footprint "QFN16")
      (libsource (lib "JTAG批量下载板-V0.5") (part "RS2299"))
    )
    (comp (ref "S_4_C4")
      (value "RS2299")
      (footprint "QFN16")
      (libsource (lib "JTAG批量下载板-V0.5") (part "RS2299"))
    )
    (comp (ref "S_4_C5")
      (value "RS2299")
      (footprint "QFN16")
      (libsource (lib "JTAG批量下载板-V0.5") (part "RS2299"))
    )
    (comp (ref "S_4_C6")
      (value "RS2299")
      (footprint "QFN16")
      (libsource (lib "JTAG批量下载板-V0.5") (part "RS2299"))
    )
    (comp (ref "U2")
      (value "MP2303ADN-LF-Z（EUP3476）")
      (footprint "SO-8-EP")
      (libsource (lib "Schlib1") (part "TD1519A"))
    )
    (comp (ref "U3")
      (value "ESDU5V0H4")
      (footprint "SOT-23-6")
      (libsource (lib "Schlib11") (part "CESDLC5V0M5"))
    )
    (comp (ref "U4")
      (value "ME6208A33PG")
      (footprint "SOT89N")
      (libsource (lib "Schlib1") (part "ME6208A50PG"))
    )
    (comp (ref "U5")
      (value "MC74HC595ADR2G")
      (footprint "SOP16_M")
      (libsource (lib "Schlib1") (part "74HC595"))
    )
    (comp (ref "U6")
      (value "STM32F103C8T6")
      (footprint "LQFP-48-1")
      (description "STM32 ARM-based 32-bit MCU with 64 Kbytes Flash, 48-pin LQFP, Industrial Temperature")
      (fields (field (name "PUBLISHER") "Altium Limited"))
      (libsource (lib "ST Microcontroller 32-Bit STM32") (part "STM32F103C8T6"))
    )
    (comp (ref "U14")
      (value "MC74HC595ADR2G")
      (footprint "SOP16_M")
      (libsource (lib "Schlib1") (part "74HC595"))
    )
    (comp (ref "U15")
      (value "MC74HC595ADR2G")
      (footprint "SOP16_M")
      (libsource (lib "Schlib1") (part "74HC595"))
    )
    (comp (ref "U16")
      (value "ME6210A50PG")
      (footprint "SOT89N")
      (libsource (lib "Schlib1") (part "ME6208A50PG"))
    )
    (comp (ref "Y1")
      (value "8M")
      (footprint "CRYSTAL_3.2*2.5")
      (libsource (lib "schlib-yves20140829") (part "CRYSTAL-PASSIVE_3225"))
    )
    (comp (ref "Z1")
      (value "SMBJ12A")
      (footprint "SMB")
      (description "Zener Diode")
      (fields (field (name "PUBLISHER") "Altium Limited"))
      (libsource (lib "Miscellaneous Devices") (part "D Zener"))
    )
  )
  (nets
    (net (code "1") (name "/5V") (class "Default")
      (node (ref "C22") (pin "1") (pinfunction "1_1") (pintype "passive"))
      (node (ref "C23") (pin "2") (pinfunction "2_2") (pintype "passive"))
      (node (ref "P24") (pin "1") (pinfunction "1_1") (pintype "passive"))
      (node (ref "R49") (pin "2") (pinfunction "2_2") (pintype "passive"))
      (node (ref "U16") (pin "3") (pinfunction "VOUT_3") (pintype "passive"))
    )
    (net (code "2") (name "/12V+") (class "Default")
      (node (ref "F1") (pin "2") (pinfunction "2_2") (pintype "passive"))
      (node (ref "L1") (pin "2") (pinfunction "2_2") (pintype "passive"))
      (node (ref "Z1") (pin "K") (pinfunction "K_K") (pintype "passive"))
    )
    (net (code "3") (name "/12V-") (class "Default")
      (node (ref "L2") (pin "2") (pinfunction "2_2") (pintype "passive"))
      (node (ref "P0") (pin "2") (pinfunction "2_2") (pintype "passive"))
      (node (ref "Z1") (pin "A") (pinfunction "A_A") (pintype "passive"))
    )
    (net (code "4") (name "/BEEP_CON") (class "Default")
      (node (ref "R20") (pin "1") (pinfunction "1_1") (pintype "passive"))
      (node (ref "U6") (pin "32") (pinfunction "PA11_32") (pintype "bidirectional"))
    )
    (net (code "5") (name "/BOOT0") (class "Default")
      (node (ref "R14") (pin "2") (pinfunction "2_2") (pintype "passive"))
      (node (ref "U6") (pin "44") (pinfunction "BOOT0_44") (pintype "input"))
    )
    (net (code "6") (name "/BOOT1") (class "Default")
      (node (ref "R17") (pin "2") (pinfunction "2_2") (pintype "passive"))
      (node (ref "U6") (pin "20") (pinfunction "PB2/BOOT1_20") (pintype "bidirectional"))
    )
    (net (code "7") (name "/EN_1_C1") (class "Default")
      (node (ref "P_1_C1") (pin "4") (pinfunction "EN_4") (pintype "passive"))
      (node (ref "S_1_C1") (pin "10") (pinfunction "IN3-4_10") (pintype "passive"))
      (node (ref "S_1_C1") (pin "2") (pinfunction "IN1-2_2") (pintype "passive"))
      (node (ref "U5") (pin "15") (pinfunction "QA_15") (pintype "passive"))
    )
    (net (code "8") (name "/EN_1_C2") (class "Default")
      (node (ref "P_1_C2") (pin "4") (pinfunction "EN_4") (pintype "passive"))
      (node (ref "S_1_C2") (pin "10") (pinfunction "IN3-4_10") (pintype "passive"))
      (node (ref "S_1_C2") (pin "2") (pinfunction "IN1-2_2") (pintype "passive"))
      (node (ref "U5") (pin "4") (pinfunction "QE_4") (pintype "passive"))
    )
    (net (code "9") (name "/EN_1_C3") (class "Default")
      (node (ref "P_1_C3") (pin "4") (pinfunction "EN_4") (pintype "passive"))
      (node (ref "S_1_C3") (pin "10") (pinfunction "IN3-4_10") (pintype "passive"))
      (node (ref "S_1_C3") (pin "2") (pinfunction "IN1-2_2") (pintype "passive"))
      (node (ref "U14") (pin "15") (pinfunction "QA_15") (pintype "passive"))
    )
    (net (code "10") (name "/EN_1_C4") (class "Default")
      (node (ref "P_1_C4") (pin "4") (pinfunction "EN_4") (pintype "passive"))
      (node (ref "S_1_C4") (pin "10") (pinfunction "IN3-4_10") (pintype "passive"))
      (node (ref "S_1_C4") (pin "2") (pinfunction "IN1-2_2") (pintype "passive"))
      (node (ref "U14") (pin "4") (pinfunction "QE_4") (pintype "passive"))
    )
    (net (code "11") (name "/EN_1_C5") (class "Default")
      (node (ref "P_1_C5") (pin "4") (pinfunction "EN_4") (pintype "passive"))
      (node (ref "S_1_C5") (pin "10") (pinfunction "IN3-4_10") (pintype "passive"))
      (node (ref "S_1_C5") (pin "2") (pinfunction "IN1-2_2") (pintype "passive"))
      (node (ref "U15") (pin "15") (pinfunction "QA_15") (pintype "passive"))
    )
    (net (code "12") (name "/EN_1_C6") (class "Default")
      (node (ref "P_1_C6") (pin "4") (pinfunction "EN_4") (pintype "passive"))
      (node (ref "S_1_C6") (pin "10") (pinfunction "IN3-4_10") (pintype "passive"))
      (node (ref "S_1_C6") (pin "2") (pinfunction "IN1-2_2") (pintype "passive"))
      (node (ref "U15") (pin "4") (pinfunction "QE_4") (pintype "passive"))
    )
    (net (code "13") (name "/EN_2_C1") (class "Default")
      (node (ref "P_2_C1") (pin "4") (pinfunction "EN_4") (pintype "passive"))
      (node (ref "S_2_C1") (pin "10") (pinfunction "IN3-4_10") (pintype "passive"))
      (node (ref "S_2_C1") (pin "2") (pinfunction "IN1-2_2") (pintype "passive"))
      (node (ref "U5") (pin "1") (pinfunction "QB_1") (pintype "passive"))
    )
    (net (code "14") (name "/EN_2_C2") (class "Default")
      (node (ref "P_2_C2") (pin "4") (pinfunction "EN_4") (pintype "passive"))
      (node (ref "S_2_C2") (pin "10") (pinfunction "IN3-4_10") (pintype "passive"))
      (node (ref "S_2_C2") (pin "2") (pinfunction "IN1-2_2") (pintype "passive"))
      (node (ref "U5") (pin "5") (pinfunction "QF_5") (pintype "passive"))
    )
    (net (code "15") (name "/EN_2_C3") (class "Default")
      (node (ref "P_2_C3") (pin "4") (pinfunction "EN_4") (pintype "passive"))
      (node (ref "S_2_C3") (pin "10") (pinfunction "IN3-4_10") (pintype "passive"))
      (node (ref "S_2_C3") (pin "2") (pinfunction "IN1-2_2") (pintype "passive"))
      (node (ref "U14") (pin "1") (pinfunction "QB_1") (pintype "passive"))
    )
    (net (code "16") (name "/EN_2_C4") (class "Default")
      (node (ref "P_2_C4") (pin "4") (pinfunction "EN_4") (pintype "passive"))
      (node (ref "S_2_C4") (pin "10") (pinfunction "IN3-4_10") (pintype "passive"))
      (node (ref "S_2_C4") (pin "2") (pinfunction "IN1-2_2") (pintype "passive"))
      (node (ref "U14") (pin "5") (pinfunction "QF_5") (pintype "passive"))
    )
    (net (code "17") (name "/EN_2_C5") (class "Default")
      (node (ref "P_2_C5") (pin "4") (pinfunction "EN_4") (pintype "passive"))
      (node (ref "S_2_C5") (pin "10") (pinfunction "IN3-4_10") (pintype "passive"))
      (node (ref "S_2_C5") (pin "2") (pinfunction "IN1-2_2") (pintype "passive"))
      (node (ref "U15") (pin "1") (pinfunction "QB_1") (pintype "passive"))
    )
    (net (code "18") (name "/EN_2_C6") (class "Default")
      (node (ref "P_2_C6") (pin "4") (pinfunction "EN_4") (pintype "passive"))
      (node (ref "S_2_C6") (pin "10") (pinfunction "IN3-4_10") (pintype "passive"))
      (node (ref "S_2_C6") (pin "2") (pinfunction "IN1-2_2") (pintype "passive"))
      (node (ref "U15") (pin "5") (pinfunction "QF_5") (pintype "passive"))
    )
    (net (code "19") (name "/EN_3_C1") (class "Default")
      (node (ref "P_3_C1") (pin "4") (pinfunction "EN_4") (pintype "passive"))
      (node (ref "S_3_C1") (pin "10") (pinfunction "IN3-4_10") (pintype "passive"))
      (node (ref "S_3_C1") (pin "2") (pinfunction "IN1-2_2") (pintype "passive"))
      (node (ref "U5") (pin "2") (pinfunction "QC_2") (pintype "passive"))
    )
    (net (code "20") (name "/EN_3_C2") (class "Default")
      (node (ref "P_3_C2") (pin "4") (pinfunction "EN_4") (pintype "passive"))
      (node (ref "S_3_C2") (pin "10") (pinfunction "IN3-4_10") (pintype "passive"))
      (node (ref "S_3_C2") (pin "2") (pinfunction "IN1-2_2") (pintype "passive"))
      (node (ref "U5") (pin "6") (pinfunction "QG_6") (pintype "passive"))
    )
    (net (code "21") (name "/EN_3_C3") (class "Default")
      (node (ref "P_3_C3") (pin "4") (pinfunction "EN_4") (pintype "passive"))
      (node (ref "S_3_C3") (pin "10") (pinfunction "IN3-4_10") (pintype "passive"))
      (node (ref "S_3_C3") (pin "2") (pinfunction "IN1-2_2") (pintype "passive"))
      (node (ref "U14") (pin "2") (pinfunction "QC_2") (pintype "passive"))
    )
    (net (code "22") (name "/EN_3_C4") (class "Default")
      (node (ref "P_3_C4") (pin "4") (pinfunction "EN_4") (pintype "passive"))
      (node (ref "S_3_C4") (pin "10") (pinfunction "IN3-4_10") (pintype "passive"))
      (node (ref "S_3_C4") (pin "2") (pinfunction "IN1-2_2") (pintype "passive"))
      (node (ref "U14") (pin "6") (pinfunction "QG_6") (pintype "passive"))
    )
    (net (code "23") (name "/EN_3_C5") (class "Default")
      (node (ref "P_3_C5") (pin "4") (pinfunction "EN_4") (pintype "passive"))
      (node (ref "S_3_C5") (pin "10") (pinfunction "IN3-4_10") (pintype "passive"))
      (node (ref "S_3_C5") (pin "2") (pinfunction "IN1-2_2") (pintype "passive"))
      (node (ref "U15") (pin "2") (pinfunction "QC_2") (pintype "passive"))
    )
    (net (code "24") (name "/EN_3_C6") (class "Default")
      (node (ref "P_3_C6") (pin "4") (pinfunction "EN_4") (pintype "passive"))
      (node (ref "S_3_C6") (pin "10") (pinfunction "IN3-4_10") (pintype "passive"))
      (node (ref "S_3_C6") (pin "2") (pinfunction "IN1-2_2") (pintype "passive"))
      (node (ref "U15") (pin "6") (pinfunction "QG_6") (pintype "passive"))
    )
    (net (code "25") (name "/EN_4_C1") (class "Default")
      (node (ref "P_4_C1") (pin "4") (pinfunction "EN_4") (pintype "passive"))
      (node (ref "S_4_C1") (pin "10") (pinfunction "IN3-4_10") (pintype "passive"))
      (node (ref "S_4_C1") (pin "2") (pinfunction "IN1-2_2") (pintype "passive"))
      (node (ref "U5") (pin "3") (pinfunction "QD_3") (pintype "passive"))
    )
    (net (code "26") (name "/EN_4_C2") (class "Default")
      (node (ref "P_4_C2") (pin "4") (pinfunction "EN_4") (pintype "passive"))
      (node (ref "S_4_C2") (pin "10") (pinfunction "IN3-4_10") (pintype "passive"))
      (node (ref "S_4_C2") (pin "2") (pinfunction "IN1-2_2") (pintype "passive"))
      (node (ref "U5") (pin "7") (pinfunction "QH_7") (pintype "passive"))
    )
    (net (code "27") (name "/EN_4_C3") (class "Default")
      (node (ref "P_4_C3") (pin "4") (pinfunction "EN_4") (pintype "passive"))
      (node (ref "S_4_C3") (pin "10") (pinfunction "IN3-4_10") (pintype "passive"))
      (node (ref "S_4_C3") (pin "2") (pinfunction "IN1-2_2") (pintype "passive"))
      (node (ref "U14") (pin "3") (pinfunction "QD_3") (pintype "passive"))
    )
    (net (code "28") (name "/EN_4_C4") (class "Default")
      (node (ref "P_4_C4") (pin "4") (pinfunction "EN_4") (pintype "passive"))
      (node (ref "S_4_C4") (pin "10") (pinfunction "IN3-4_10") (pintype "passive"))
      (node (ref "S_4_C4") (pin "2") (pinfunction "IN1-2_2") (pintype "passive"))
      (node (ref "U14") (pin "7") (pinfunction "QH_7") (pintype "passive"))
    )
    (net (code "29") (name "/EN_4_C5") (class "Default")
      (node (ref "P_4_C5") (pin "4") (pinfunction "EN_4") (pintype "passive"))
      (node (ref "S_4_C5") (pin "10") (pinfunction "IN3-4_10") (pintype "passive"))
      (node (ref "S_4_C5") (pin "2") (pinfunction "IN1-2_2") (pintype "passive"))
      (node (ref "U15") (pin "3") (pinfunction "QD_3") (pintype "passive"))
    )
    (net (code "30") (name "/EN_4_C6") (class "Default")
      (node (ref "P_4_C6") (pin "4") (pinfunction "EN_4") (pintype "passive"))
      (node (ref "S_4_C6") (pin "10") (pinfunction "IN3-4_10") (pintype "passive"))
      (node (ref "S_4_C6") (pin "2") (pinfunction "IN1-2_2") (pintype "passive"))
      (node (ref "U15") (pin "7") (pinfunction "QH_7") (pintype "passive"))
    )
    (net (code "31") (name "/EN_D1") (class "Default")
      (node (ref "U5") (pin "14") (pinfunction "SER_14") (pintype "passive"))
      (node (ref "U6") (pin "28") (pinfunction "PB15_28") (pintype "bidirectional"))
    )
    (net (code "32") (name "/ISP_RXD") (class "Default")
      (node (ref "P18") (pin "4") (pinfunction "4_4") (pintype "passive"))
      (node (ref "R18") (pin "1") (pinfunction "1_1") (pintype "passive"))
      (node (ref "U3") (pin "6") (pinfunction "6_6") (pintype "passive"))
    )
    (net (code "33") (name "/ISP_RXD_1_C1") (class "Default")
      (node (ref "ISP_1_C1&2") (pin "3") (pinfunction "NO2_3") (pintype "passive"))
      (node (ref "P1_C1") (pin "7") (pinfunction "7_7") (pintype "passive"))
    )
    (net (code "34") (name "/ISP_RXD_1_C2") (class "Default")
      (node (ref "ISP_1_C1&2") (pin "11") (pinfunction "NO4_11") (pintype "passive"))
      (node (ref "P1_C2") (pin "7") (pinfunction "7_7") (pintype "passive"))
    )
    (net (code "35") (name "/ISP_RXD_1_C3") (class "Default")
      (node (ref "ISP_1_C3&4") (pin "3") (pinfunction "NO2_3") (pintype "passive"))
      (node (ref "P1_C3") (pin "7") (pinfunction "7_7") (pintype "passive"))
    )
    (net (code "36") (name "/ISP_RXD_1_C4") (class "Default")
      (node (ref "ISP_1_C3&4") (pin "11") (pinfunction "NO4_11") (pintype "passive"))
      (node (ref "P1_C4") (pin "7") (pinfunction "7_7") (pintype "passive"))
    )
    (net (code "37") (name "/ISP_RXD_1_C5") (class "Default")
      (node (ref "ISP_1_C5&6") (pin "3") (pinfunction "NO2_3") (pintype "passive"))
      (node (ref "P1_C5") (pin "7") (pinfunction "7_7") (pintype "passive"))
    )
    (net (code "38") (name "/ISP_RXD_1_C6") (class "Default")
      (node (ref "ISP_1_C5&6") (pin "11") (pinfunction "NO4_11") (pintype "passive"))
      (node (ref "P1_C6") (pin "7") (pinfunction "7_7") (pintype "passive"))
    )
    (net (code "39") (name "/ISP_RXD_2_C1") (class "Default")
      (node (ref "ISP_2_C1&2") (pin "3") (pinfunction "NO2_3") (pintype "passive"))
      (node (ref "P2_C1") (pin "7") (pinfunction "7_7") (pintype "passive"))
    )
    (net (code "40") (name "/ISP_RXD_2_C2") (class "Default")
      (node (ref "ISP_2_C1&2") (pin "11") (pinfunction "NO4_11") (pintype "passive"))
      (node (ref "P2_C2") (pin "7") (pinfunction "7_7") (pintype "passive"))
    )
    (net (code "41") (name "/ISP_RXD_2_C3") (class "Default")
      (node (ref "ISP_2_C3&4") (pin "3") (pinfunction "NO2_3") (pintype "passive"))
      (node (ref "P2_C3") (pin "7") (pinfunction "7_7") (pintype "passive"))
    )
    (net (code "42") (name "/ISP_RXD_2_C4") (class "Default")
      (node (ref "ISP_2_C3&4") (pin "11") (pinfunction "NO4_11") (pintype "passive"))
      (node (ref "P2_C4") (pin "7") (pinfunction "7_7") (pintype "passive"))
    )
    (net (code "43") (name "/ISP_RXD_2_C5") (class "Default")
      (node (ref "ISP_2_C5&6") (pin "3") (pinfunction "NO2_3") (pintype "passive"))
      (node (ref "P2_C5") (pin "7") (pinfunction "7_7") (pintype "passive"))
    )
    (net (code "44") (name "/ISP_RXD_2_C6") (class "Default")
      (node (ref "ISP_2_C5&6") (pin "11") (pinfunction "NO4_11") (pintype "passive"))
      (node (ref "P2_C6") (pin "7") (pinfunction "7_7") (pintype "passive"))
    )
    (net (code "45") (name "/ISP_RXD_3_C1") (class "Default")
      (node (ref "ISP_3_C1&2") (pin "3") (pinfunction "NO2_3") (pintype "passive"))
      (node (ref "P3_C1") (pin "7") (pinfunction "7_7") (pintype "passive"))
    )
    (net (code "46") (name "/ISP_RXD_3_C2") (class "Default")
      (node (ref "ISP_3_C1&2") (pin "11") (pinfunction "NO4_11") (pintype "passive"))
      (node (ref "P3_C2") (pin "7") (pinfunction "7_7") (pintype "passive"))
    )
    (net (code "47") (name "/ISP_RXD_3_C3") (class "Default")
      (node (ref "ISP_3_C3&4") (pin "3") (pinfunction "NO2_3") (pintype "passive"))
      (node (ref "P3_C3") (pin "7") (pinfunction "7_7") (pintype "passive"))
    )
    (net (code "48") (name "/ISP_RXD_3_C4") (class "Default")
      (node (ref "ISP_3_C3&4") (pin "11") (pinfunction "NO4_11") (pintype "passive"))
      (node (ref "P3_C4") (pin "7") (pinfunction "7_7") (pintype "passive"))
    )
    (net (code "49") (name "/ISP_RXD_3_C5") (class "Default")
      (node (ref "ISP_3_C5&6") (pin "3") (pinfunction "NO2_3") (pintype "passive"))
      (node (ref "P3-C5") (pin "7") (pinfunction "7_7") (pintype "passive"))
    )
    (net (code "50") (name "/ISP_RXD_3_C6") (class "Default")
      (node (ref "ISP_3_C5&6") (pin "11") (pinfunction "NO4_11") (pintype "passive"))
      (node (ref "P3-C6") (pin "7") (pinfunction "7_7") (pintype "passive"))
    )
    (net (code "51") (name "/ISP_RXD_4_C1") (class "Default")
      (node (ref "ISP_4_C1&2") (pin "3") (pinfunction "NO2_3") (pintype "passive"))
      (node (ref "P4_C1") (pin "7") (pinfunction "7_7") (pintype "passive"))
    )
    (net (code "52") (name "/ISP_RXD_4_C2") (class "Default")
      (node (ref "ISP_4_C1&2") (pin "11") (pinfunction "NO4_11") (pintype "passive"))
      (node (ref "P4_C2") (pin "7") (pinfunction "7_7") (pintype "passive"))
    )
    (net (code "53") (name "/ISP_RXD_4_C3") (class "Default")
      (node (ref "ISP_4_C3&4") (pin "3") (pinfunction "NO2_3") (pintype "passive"))
      (node (ref "P4_C3") (pin "7") (pinfunction "7_7") (pintype "passive"))
    )
    (net (code "54") (name "/ISP_RXD_4_C4") (class "Default")
      (node (ref "ISP_4_C3&4") (pin "11") (pinfunction "NO4_11") (pintype "passive"))
      (node (ref "P4_C4") (pin "7") (pinfunction "7_7") (pintype "passive"))
    )
    (net (code "55") (name "/ISP_RXD_4_C5") (class "Default")
      (node (ref "ISP_4_C5&6") (pin "3") (pinfunction "NO2_3") (pintype "passive"))
      (node (ref "P4_C5") (pin "7") (pinfunction "7_7") (pintype "passive"))
    )
    (net (code "56") (name "/ISP_RXD_4_C6") (class "Default")
      (node (ref "ISP_4_C5&6") (pin "11") (pinfunction "NO4_11") (pintype "passive"))
      (node (ref "P4_C6") (pin "7") (pinfunction "7_7") (pintype "passive"))
    )
    (net (code "57") (name "/ISP_RXD_DL") (class "Default")
      (node (ref "J-I-S") (pin "3") (pinfunction "NO2_3") (pintype "passive"))
      (node (ref "JTAG/ISP") (pin "7") (pinfunction "ISP-RXD_7") (pintype "passive"))
    )
    (net (code "58") (name "/ISP_TXD") (class "Default")
      (node (ref "P18") (pin "3") (pinfunction "3_3") (pintype "passive"))
      (node (ref "R19") (pin "1") (pinfunction "1_1") (pintype "passive"))
      (node (ref "U3") (pin "4") (pinfunction "4_4") (pintype "passive"))
    )
    (net (code "59") (name "/ISP_TXD_1_C1") (class "Default")
      (node (ref "ISP_1_C1&2") (pin "15") (pinfunction "NO1_15") (pintype "passive"))
      (node (ref "P1_C1") (pin "6") (pinfunction "6_6") (pintype "passive"))
    )
    (net (code "60") (name "/ISP_TXD_1_C2") (class "Default")
      (node (ref "ISP_1_C1&2") (pin "7") (pinfunction "NO3_7") (pintype "passive"))
      (node (ref "P1_C2") (pin "6") (pinfunction "6_6") (pintype "passive"))
    )
    (net (code "61") (name "/ISP_TXD_1_C3") (class "Default")
      (node (ref "ISP_1_C3&4") (pin "15") (pinfunction "NO1_15") (pintype "passive"))
      (node (ref "P1_C3") (pin "6") (pinfunction "6_6") (pintype "passive"))
    )
    (net (code "62") (name "/ISP_TXD_1_C4") (class "Default")
      (node (ref "ISP_1_C3&4") (pin "7") (pinfunction "NO3_7") (pintype "passive"))
      (node (ref "P1_C4") (pin "6") (pinfunction "6_6") (pintype "passive"))
    )
    (net (code "63") (name "/ISP_TXD_1_C5") (class "Default")
      (node (ref "ISP_1_C5&6") (pin "15") (pinfunction "NO1_15") (pintype "passive"))
      (node (ref "P1_C5") (pin "6") (pinfunction "6_6") (pintype "passive"))
    )
    (net (code "64") (name "/ISP_TXD_1_C6") (class "Default")
      (node (ref "ISP_1_C5&6") (pin "7") (pinfunction "NO3_7") (pintype "passive"))
      (node (ref "P1_C6") (pin "6") (pinfunction "6_6") (pintype "passive"))
    )
    (net (code "65") (name "/ISP_TXD_2_C1") (class "Default")
      (node (ref "ISP_2_C1&2") (pin "15") (pinfunction "NO1_15") (pintype "passive"))
      (node (ref "P2_C1") (pin "6") (pinfunction "6_6") (pintype "passive"))
    )
    (net (code "66") (name "/ISP_TXD_2_C2") (class "Default")
      (node (ref "ISP_2_C1&2") (pin "7") (pinfunction "NO3_7") (pintype "passive"))
      (node (ref "P2_C2") (pin "6") (pinfunction "6_6") (pintype "passive"))
    )
    (net (code "67") (name "/ISP_TXD_2_C3") (class "Default")
      (node (ref "ISP_2_C3&4") (pin "15") (pinfunction "NO1_15") (pintype "passive"))
      (node (ref "P2_C3") (pin "6") (pinfunction "6_6") (pintype "passive"))
    )
    (net (code "68") (name "/ISP_TXD_2_C4") (class "Default")
      (node (ref "ISP_2_C3&4") (pin "7") (pinfunction "NO3_7") (pintype "passive"))
      (node (ref "P2_C4") (pin "6") (pinfunction "6_6") (pintype "passive"))
    )
    (net (code "69") (name "/ISP_TXD_2_C5") (class "Default")
      (node (ref "ISP_2_C5&6") (pin "15") (pinfunction "NO1_15") (pintype "passive"))
      (node (ref "P2_C5") (pin "6") (pinfunction "6_6") (pintype "passive"))
    )
    (net (code "70") (name "/ISP_TXD_2_C6") (class "Default")
      (node (ref "ISP_2_C5&6") (pin "7") (pinfunction "NO3_7") (pintype "passive"))
      (node (ref "P2_C6") (pin "6") (pinfunction "6_6") (pintype "passive"))
    )
    (net (code "71") (name "/ISP_TXD_3_C1") (class "Default")
      (node (ref "ISP_3_C1&2") (pin "15") (pinfunction "NO1_15") (pintype "passive"))
      (node (ref "P3_C1") (pin "6") (pinfunction "6_6") (pintype "passive"))
    )
    (net (code "72") (name "/ISP_TXD_3_C2") (class "Default")
      (node (ref "ISP_3_C1&2") (pin "7") (pinfunction "NO3_7") (pintype "passive"))
      (node (ref "P3_C2") (pin "6") (pinfunction "6_6") (pintype "passive"))
    )
    (net (code "73") (name "/ISP_TXD_3_C3") (class "Default")
      (node (ref "ISP_3_C3&4") (pin "15") (pinfunction "NO1_15") (pintype "passive"))
      (node (ref "P3_C3") (pin "6") (pinfunction "6_6") (pintype "passive"))
    )
    (net (code "74") (name "/ISP_TXD_3_C4") (class "Default")
      (node (ref "ISP_3_C3&4") (pin "7") (pinfunction "NO3_7") (pintype "passive"))
      (node (ref "P3_C4") (pin "6") (pinfunction "6_6") (pintype "passive"))
    )
    (net (code "75") (name "/ISP_TXD_3_C5") (class "Default")
      (node (ref "ISP_3_C5&6") (pin "15") (pinfunction "NO1_15") (pintype "passive"))
      (node (ref "P3-C5") (pin "6") (pinfunction "6_6") (pintype "passive"))
    )
    (net (code "76") (name "/ISP_TXD_3_C6") (class "Default")
      (node (ref "ISP_3_C5&6") (pin "7") (pinfunction "NO3_7") (pintype "passive"))
      (node (ref "P3-C6") (pin "6") (pinfunction "6_6") (pintype "passive"))
    )
    (net (code "77") (name "/ISP_TXD_4_C1") (class "Default")
      (node (ref "ISP_4_C1&2") (pin "15") (pinfunction "NO1_15") (pintype "passive"))
      (node (ref "P4_C1") (pin "6") (pinfunction "6_6") (pintype "passive"))
    )
    (net (code "78") (name "/ISP_TXD_4_C2") (class "Default")
      (node (ref "ISP_4_C1&2") (pin "7") (pinfunction "NO3_7") (pintype "passive"))
      (node (ref "P4_C2") (pin "6") (pinfunction "6_6") (pintype "passive"))
    )
    (net (code "79") (name "/ISP_TXD_4_C3") (class "Default")
      (node (ref "ISP_4_C3&4") (pin "15") (pinfunction "NO1_15") (pintype "passive"))
      (node (ref "P4_C3") (pin "6") (pinfunction "6_6") (pintype "passive"))
    )
    (net (code "80") (name "/ISP_TXD_4_C4") (class "Default")
      (node (ref "ISP_4_C3&4") (pin "7") (pinfunction "NO3_7") (pintype "passive"))
      (node (ref "P4_C4") (pin "6") (pinfunction "6_6") (pintype "passive"))
    )
    (net (code "81") (name "/ISP_TXD_4_C5") (class "Default")
      (node (ref "ISP_4_C5&6") (pin "15") (pinfunction "NO1_15") (pintype "passive"))
      (node (ref "P4_C5") (pin "6") (pinfunction "6_6") (pintype "passive"))
    )
    (net (code "82") (name "/ISP_TXD_4_C6") (class "Default")
      (node (ref "ISP_4_C5&6") (pin "7") (pinfunction "NO3_7") (pintype "passive"))
      (node (ref "P4_C6") (pin "6") (pinfunction "6_6") (pintype "passive"))
    )
    (net (code "83") (name "/ISP_TXD_DL") (class "Default")
      (node (ref "J-I-S") (pin "15") (pinfunction "NO1_15") (pintype "passive"))
      (node (ref "JTAG/ISP") (pin "6") (pinfunction "ISP-TXD_6") (pintype "passive"))
    )
    (net (code "84") (name "/JTAG_3.3V") (class "Default")
      (node (ref "J1") (pin "1") (pinfunction "1_1") (pintype "passive"))
    )
    (net (code "85") (name "/JTAG_BUSY") (class "Default")
      (node (ref "R5") (pin "2") (pinfunction "2_2") (pintype "passive"))
      (node (ref "U6") (pin "45") (pinfunction "PB8_45") (pintype "bidirectional"))
    )
    (net (code "86") (name "/JTAG_FAIL") (class "Default")
      (node (ref "R9") (pin "2") (pinfunction "2_2") (pintype "passive"))
      (node (ref "U6") (pin "46") (pinfunction "PB9_46") (pintype "bidirectional"))
    )
    (net (code "87") (name "/JTAG_OK") (class "Default")
      (node (ref "R2") (pin "2") (pinfunction "2_2") (pintype "passive"))
      (node (ref "U6") (pin "43") (pinfunction "PB7_43") (pintype "bidirectional"))
    )
    (net (code "88") (name "/JTAG_START") (class "Default")
      (node (ref "R1") (pin "2") (pinfunction "2_2") (pintype "passive"))
      (node (ref "U6") (pin "42") (pinfunction "PB6_42") (pintype "bidirectional"))
    )
    (net (code "89") (name "/JTAG_TCK") (class "Default")
      (node (ref "JTAG/ISP") (pin "4") (pinfunction "JTAG_TCK_4") (pintype "passive"))
      (node (ref "S_1_C1") (pin "8") (pinfunction "COM3_8") (pintype "passive"))
      (node (ref "S_1_C2") (pin "8") (pinfunction "COM3_8") (pintype "passive"))
      (node (ref "S_1_C3") (pin "8") (pinfunction "COM3_8") (pintype "passive"))
      (node (ref "S_1_C4") (pin "8") (pinfunction "COM3_8") (pintype "passive"))
      (node (ref "S_1_C5") (pin "8") (pinfunction "COM3_8") (pintype "passive"))
      (node (ref "S_1_C6") (pin "8") (pinfunction "COM3_8") (pintype "passive"))
      (node (ref "S_2_C1") (pin "8") (pinfunction "COM3_8") (pintype "passive"))
      (node (ref "S_2_C2") (pin "8") (pinfunction "COM3_8") (pintype "passive"))
      (node (ref "S_2_C3") (pin "8") (pinfunction "COM3_8") (pintype "passive"))
      (node (ref "S_2_C4") (pin "8") (pinfunction "COM3_8") (pintype "passive"))
      (node (ref "S_2_C5") (pin "8") (pinfunction "COM3_8") (pintype "passive"))
      (node (ref "S_2_C6") (pin "8") (pinfunction "COM3_8") (pintype "passive"))
      (node (ref "S_3_C1") (pin "8") (pinfunction "COM3_8") (pintype "passive"))
      (node (ref "S_3_C2") (pin "8") (pinfunction "COM3_8") (pintype "passive"))
      (node (ref "S_3_C3") (pin "8") (pinfunction "COM3_8") (pintype "passive"))
      (node (ref "S_3_C4") (pin "8") (pinfunction "COM3_8") (pintype "passive"))
      (node (ref "S_3_C5") (pin "8") (pinfunction "COM3_8") (pintype "passive"))
      (node (ref "S_3_C6") (pin "8") (pinfunction "COM3_8") (pintype "passive"))
      (node (ref "S_4_C1") (pin "8") (pinfunction "COM3_8") (pintype "passive"))
      (node (ref "S_4_C2") (pin "8") (pinfunction "COM3_8") (pintype "passive"))
      (node (ref "S_4_C3") (pin "8") (pinfunction "COM3_8") (pintype "passive"))
      (node (ref "S_4_C4") (pin "8") (pinfunction "COM3_8") (pintype "passive"))
      (node (ref "S_4_C5") (pin "8") (pinfunction "COM3_8") (pintype "passive"))
      (node (ref "S_4_C6") (pin "8") (pinfunction "COM3_8") (pintype "passive"))
    )
    (net (code "90") (name "/JTAG_TDI") (class "Default")
      (node (ref "J-I-S") (pin "4") (pinfunction "COM2_4") (pintype "passive"))
      (node (ref "S_1_C1") (pin "4") (pinfunction "COM2_4") (pintype "passive"))
      (node (ref "S_1_C2") (pin "4") (pinfunction "COM2_4") (pintype "passive"))
      (node (ref "S_1_C3") (pin "4") (pinfunction "COM2_4") (pintype "passive"))
      (node (ref "S_1_C4") (pin "4") (pinfunction "COM2_4") (pintype "passive"))
      (node (ref "S_1_C5") (pin "4") (pinfunction "COM2_4") (pintype "passive"))
      (node (ref "S_1_C6") (pin "4") (pinfunction "COM2_4") (pintype "passive"))
      (node (ref "S_2_C1") (pin "4") (pinfunction "COM2_4") (pintype "passive"))
      (node (ref "S_2_C2") (pin "4") (pinfunction "COM2_4") (pintype "passive"))
      (node (ref "S_2_C3") (pin "4") (pinfunction "COM2_4") (pintype "passive"))
      (node (ref "S_2_C4") (pin "4") (pinfunction "COM2_4") (pintype "passive"))
      (node (ref "S_2_C5") (pin "4") (pinfunction "COM2_4") (pintype "passive"))
      (node (ref "S_2_C6") (pin "4") (pinfunction "COM2_4") (pintype "passive"))
      (node (ref "S_3_C1") (pin "4") (pinfunction "COM2_4") (pintype "passive"))
      (node (ref "S_3_C2") (pin "4") (pinfunction "COM2_4") (pintype "passive"))
      (node (ref "S_3_C3") (pin "4") (pinfunction "COM2_4") (pintype "passive"))
      (node (ref "S_3_C4") (pin "4") (pinfunction "COM2_4") (pintype "passive"))
      (node (ref "S_3_C5") (pin "4") (pinfunction "COM2_4") (pintype "passive"))
      (node (ref "S_3_C6") (pin "4") (pinfunction "COM2_4") (pintype "passive"))
      (node (ref "S_4_C1") (pin "4") (pinfunction "COM2_4") (pintype "passive"))
      (node (ref "S_4_C2") (pin "4") (pinfunction "COM2_4") (pintype "passive"))
      (node (ref "S_4_C3") (pin "4") (pinfunction "COM2_4") (pintype "passive"))
      (node (ref "S_4_C4") (pin "4") (pinfunction "COM2_4") (pintype "passive"))
      (node (ref "S_4_C5") (pin "4") (pinfunction "COM2_4") (pintype "passive"))
      (node (ref "S_4_C6") (pin "4") (pinfunction "COM2_4") (pintype "passive"))
    )
    (net (code "91") (name "/JTAG_TDI_1") (class "Default")
      (node (ref "J-I-S") (pin "5") (pinfunction "NC2_5") (pintype "passive"))
      (node (ref "JTAG/ISP") (pin "3") (pinfunction "JTAG_TDI_3") (pintype "passive"))
    )
    (net (code "92") (name "/JTAG_TDO") (class "Default")
      (node (ref "J-I-S") (pin "16") (pinfunction "COM1_16") (pintype "passive"))
      (node (ref "S_1_C1") (pin "16") (pinfunction "COM1_16") (pintype "passive"))
      (node (ref "S_1_C2") (pin "16") (pinfunction "COM1_16") (pintype "passive"))
      (node (ref "S_1_C3") (pin "16") (pinfunction "COM1_16") (pintype "passive"))
      (node (ref "S_1_C4") (pin "16") (pinfunction "COM1_16") (pintype "passive"))
      (node (ref "S_1_C5") (pin "16") (pinfunction "COM1_16") (pintype "passive"))
      (node (ref "S_1_C6") (pin "16") (pinfunction "COM1_16") (pintype "passive"))
      (node (ref "S_2_C1") (pin "16") (pinfunction "COM1_16") (pintype "passive"))
      (node (ref "S_2_C2") (pin "16") (pinfunction "COM1_16") (pintype "passive"))
      (node (ref "S_2_C3") (pin "16") (pinfunction "COM1_16") (pintype "passive"))
      (node (ref "S_2_C4") (pin "16") (pinfunction "COM1_16") (pintype "passive"))
      (node (ref "S_2_C5") (pin "16") (pinfunction "COM1_16") (pintype "passive"))
      (node (ref "S_2_C6") (pin "16") (pinfunction "COM1_16") (pintype "passive"))
      (node (ref "S_3_C1") (pin "16") (pinfunction "COM1_16") (pintype "passive"))
      (node (ref "S_3_C2") (pin "16") (pinfunction "COM1_16") (pintype "passive"))
      (node (ref "S_3_C3") (pin "16") (pinfunction "COM1_16") (pintype "passive"))
      (node (ref "S_3_C4") (pin "16") (pinfunction "COM1_16") (pintype "passive"))
      (node (ref "S_3_C5") (pin "16") (pinfunction "COM1_16") (pintype "passive"))
      (node (ref "S_3_C6") (pin "16") (pinfunction "COM1_16") (pintype "passive"))
      (node (ref "S_4_C1") (pin "16") (pinfunction "COM1_16") (pintype "passive"))
      (node (ref "S_4_C2") (pin "16") (pinfunction "COM1_16") (pintype "passive"))
      (node (ref "S_4_C3") (pin "16") (pinfunction "COM1_16") (pintype "passive"))
      (node (ref "S_4_C4") (pin "16") (pinfunction "COM1_16") (pintype "passive"))
      (node (ref "S_4_C5") (pin "16") (pinfunction "COM1_16") (pintype "passive"))
      (node (ref "S_4_C6") (pin "16") (pinfunction "COM1_16") (pintype "passive"))
    )
    (net (code "93") (name "/JTAG_TDO_1") (class "Default")
      (node (ref "J-I-S") (pin "1") (pinfunction "NC1_1") (pintype "passive"))
      (node (ref "JTAG/ISP") (pin "2") (pinfunction "JTAG_TDO_2") (pintype "passive"))
    )
    (net (code "94") (name "/JTAG_TMS") (class "Default")
      (node (ref "JTAG/ISP") (pin "5") (pinfunction "JTAG_TMS_5") (pintype "passive"))
      (node (ref "S_1_C1") (pin "12") (pinfunction "COM4_12") (pintype "passive"))
      (node (ref "S_1_C2") (pin "12") (pinfunction "COM4_12") (pintype "passive"))
      (node (ref "S_1_C3") (pin "12") (pinfunction "COM4_12") (pintype "passive"))
      (node (ref "S_1_C4") (pin "12") (pinfunction "COM4_12") (pintype "passive"))
      (node (ref "S_1_C5") (pin "12") (pinfunction "COM4_12") (pintype "passive"))
      (node (ref "S_1_C6") (pin "12") (pinfunction "COM4_12") (pintype "passive"))
      (node (ref "S_2_C1") (pin "12") (pinfunction "COM4_12") (pintype "passive"))
      (node (ref "S_2_C2") (pin "12") (pinfunction "COM4_12") (pintype "passive"))
      (node (ref "S_2_C3") (pin "12") (pinfunction "COM4_12") (pintype "passive"))
      (node (ref "S_2_C4") (pin "12") (pinfunction "COM4_12") (pintype "passive"))
      (node (ref "S_2_C5") (pin "12") (pinfunction "COM4_12") (pintype "passive"))
      (node (ref "S_2_C6") (pin "12") (pinfunction "COM4_12") (pintype "passive"))
      (node (ref "S_3_C1") (pin "12") (pinfunction "COM4_12") (pintype "passive"))
      (node (ref "S_3_C2") (pin "12") (pinfunction "COM4_12") (pintype "passive"))
      (node (ref "S_3_C3") (pin "12") (pinfunction "COM4_12") (pintype "passive"))
      (node (ref "S_3_C4") (pin "12") (pinfunction "COM4_12") (pintype "passive"))
      (node (ref "S_3_C5") (pin "12") (pinfunction "COM4_12") (pintype "passive"))
      (node (ref "S_3_C6") (pin "12") (pinfunction "COM4_12") (pintype "passive"))
      (node (ref "S_4_C1") (pin "12") (pinfunction "COM4_12") (pintype "passive"))
      (node (ref "S_4_C2") (pin "12") (pinfunction "COM4_12") (pintype "passive"))
      (node (ref "S_4_C3") (pin "12") (pinfunction "COM4_12") (pintype "passive"))
      (node (ref "S_4_C4") (pin "12") (pinfunction "COM4_12") (pintype "passive"))
      (node (ref "S_4_C5") (pin "12") (pinfunction "COM4_12") (pintype "passive"))
      (node (ref "S_4_C6") (pin "12") (pinfunction "COM4_12") (pintype "passive"))
    )
    (net (code "95") (name "/J_I_SWITCH") (class "Default")
      (node (ref "C60") (pin "1") (pinfunction "1_1") (pintype "passive"))
      (node (ref "ISP_1_C1&2") (pin "10") (pinfunction "IN3-4_10") (pintype "passive"))
      (node (ref "ISP_1_C1&2") (pin "2") (pinfunction "IN1-2_2") (pintype "passive"))
      (node (ref "ISP_1_C3&4") (pin "10") (pinfunction "IN3-4_10") (pintype "passive"))
      (node (ref "ISP_1_C3&4") (pin "2") (pinfunction "IN1-2_2") (pintype "passive"))
      (node (ref "ISP_1_C5&6") (pin "10") (pinfunction "IN3-4_10") (pintype "passive"))
      (node (ref "ISP_1_C5&6") (pin "2") (pinfunction "IN1-2_2") (pintype "passive"))
      (node (ref "ISP_2_C1&2") (pin "10") (pinfunction "IN3-4_10") (pintype "passive"))
      (node (ref "ISP_2_C1&2") (pin "2") (pinfunction "IN1-2_2") (pintype "passive"))
      (node (ref "ISP_2_C3&4") (pin "10") (pinfunction "IN3-4_10") (pintype "passive"))
      (node (ref "ISP_2_C3&4") (pin "2") (pinfunction "IN1-2_2") (pintype "passive"))
      (node (ref "ISP_2_C5&6") (pin "10") (pinfunction "IN3-4_10") (pintype "passive"))
      (node (ref "ISP_2_C5&6") (pin "2") (pinfunction "IN1-2_2") (pintype "passive"))
      (node (ref "ISP_3_C1&2") (pin "10") (pinfunction "IN3-4_10") (pintype "passive"))
      (node (ref "ISP_3_C1&2") (pin "2") (pinfunction "IN1-2_2") (pintype "passive"))
      (node (ref "ISP_3_C3&4") (pin "10") (pinfunction "IN3-4_10") (pintype "passive"))
      (node (ref "ISP_3_C3&4") (pin "2") (pinfunction "IN1-2_2") (pintype "passive"))
      (node (ref "ISP_3_C5&6") (pin "10") (pinfunction "IN3-4_10") (pintype "passive"))
      (node (ref "ISP_3_C5&6") (pin "2") (pinfunction "IN1-2_2") (pintype "passive"))
      (node (ref "ISP_4_C1&2") (pin "10") (pinfunction "IN3-4_10") (pintype "passive"))
      (node (ref "ISP_4_C1&2") (pin "2") (pinfunction "IN1-2_2") (pintype "passive"))
      (node (ref "ISP_4_C3&4") (pin "10") (pinfunction "IN3-4_10") (pintype "passive"))
      (node (ref "ISP_4_C3&4") (pin "2") (pinfunction "IN1-2_2") (pintype "passive"))
      (node (ref "ISP_4_C5&6") (pin "10") (pinfunction "IN3-4_10") (pintype "passive"))
      (node (ref "ISP_4_C5&6") (pin "2") (pinfunction "IN1-2_2") (pintype "passive"))
      (node (ref "J-I-S") (pin "2") (pinfunction "IN1-2_2") (pintype "passive"))
      (node (ref "R59") (pin "2") (pinfunction "2_2") (pintype "passive"))
      (node (ref "R60") (pin "1") (pinfunction "1_1") (pintype "passive"))
    )
    (net (code "96") (name "/KEY_1") (class "Default")
      (node (ref "C38") (pin "2") (pinfunction "2_2") (pintype "passive"))
      (node (ref "R36") (pin "1") (pinfunction "1_1") (pintype "passive"))
      (node (ref "R40") (pin "1") (pinfunction "1_1") (pintype "passive"))
      (node (ref "U6") (pin "4") (pinfunction "PC15-OSC32_OUT_4") (pintype "bidirectional"))
    )
    (net (code "97") (name "/KEY_2") (class "Default")
      (node (ref "C39") (pin "2") (pinfunction "2_2") (pintype "passive"))
      (node (ref "R37") (pin "1") (pinfunction "1_1") (pintype "passive"))
      (node (ref "R41") (pin "1") (pinfunction "1_1") (pintype "passive"))
      (node (ref "U6") (pin "3") (pinfunction "PC14-OSC32_IN_3") (pintype "bidirectional"))
    )
    (net (code "98") (name "/LCD_RXD") (class "Default")
      (node (ref "P24") (pin "2") (pinfunction "2_2") (pintype "passive"))
      (node (ref "R49") (pin "1") (pinfunction "1_1") (pintype "passive"))
      (node (ref "R50") (pin "1") (pinfunction "1_1") (pintype "passive"))
    )
    (net (code "99") (name "/LCD_TXD") (class "Default")
      (node (ref "P24") (pin "3") (pinfunction "3_3") (pintype "passive"))
      (node (ref "R47") (pin "1") (pinfunction "1_1") (pintype "passive"))
    )
    (net (code "100") (name "/MCU_RX1") (class "Default")
      (node (ref "R19") (pin "2") (pinfunction "2_2") (pintype "passive"))
      (node (ref "U6") (pin "31") (pinfunction "PA10_31") (pintype "bidirectional"))
    )
    (net (code "101") (name "/MCU_RX2") (class "Default")
      (node (ref "R47") (pin "2") (pinfunction "2_2") (pintype "passive"))
      (node (ref "R48") (pin "2") (pinfunction "2_2") (pintype "passive"))
      (node (ref "U6") (pin "13") (pinfunction "PA3_13") (pintype "bidirectional"))
    )
    (net (code "102") (name "/MCU_RX3") (class "Default")
      (node (ref "R44") (pin "2") (pinfunction "2_2") (pintype "passive"))
      (node (ref "R45") (pin "2") (pinfunction "2_2") (pintype "passive"))
      (node (ref "U6") (pin "22") (pinfunction "PB11_22") (pintype "bidirectional"))
    )
    (net (code "103") (name "/MCU_TX1") (class "Default")
      (node (ref "R18") (pin "2") (pinfunction "2_2") (pintype "passive"))
      (node (ref "U6") (pin "30") (pinfunction "PA9_30") (pintype "bidirectional"))
    )
    (net (code "104") (name "/MCU_TX2") (class "Default")
      (node (ref "R50") (pin "2") (pinfunction "2_2") (pintype "passive"))
      (node (ref "U6") (pin "12") (pinfunction "PA2_12") (pintype "bidirectional"))
    )
    (net (code "105") (name "/MCU_TX3") (class "Default")
      (node (ref "R51") (pin "2") (pinfunction "2_2") (pintype "passive"))
      (node (ref "U6") (pin "21") (pinfunction "PB10_21") (pintype "bidirectional"))
    )
    (net (code "106") (name "/NRST") (class "Default")
      (node (ref "C26") (pin "1") (pinfunction "1_1") (pintype "passive"))
      (node (ref "R12") (pin "1") (pinfunction "1_1") (pintype "passive"))
      (node (ref "S0") (pin "1") (pinfunction "1_1") (pintype "passive"))
      (node (ref "S0") (pin "2") (pinfunction "2_2") (pintype "passive"))
      (node (ref "U6") (pin "7") (pinfunction "NRST_7") (pintype "bidirectional"))
    )
    (net (code "107") (name "/OSC_IN") (class "Default")
      (node (ref "C24") (pin "1") (pinfunction "1_1") (pintype "passive"))
      (node (ref "R11") (pin "1") (pinfunction "1_1") (pintype "passive"))
      (node (ref "U6") (pin "5") (pinfunction "OSC_IN/PD0_5") (pintype "input"))
      (node (ref "Y1") (pin "3") (pinfunction "OUTPUT_3") (pintype "passive"))
    )
    (net (code "108") (name "/OSC_OUT") (class "Default")
      (node (ref "C25") (pin "1") (pinfunction "1_1") (pintype "passive"))
      (node (ref "R11") (pin "2") (pinfunction "2_2") (pintype "passive"))
      (node (ref "U6") (pin "6") (pinfunction "OSC_OUT/PD1_6") (pintype "output"))
      (node (ref "Y1") (pin "1") (pinfunction "INPUT_1") (pintype "passive"))
    )
    (net (code "109") (name "/PRT_DTR") (class "Default")
      (node (ref "R43") (pin "2") (pinfunction "2_2") (pintype "passive"))
      (node (ref "U6") (pin "17") (pinfunction "PA7_17") (pintype "bidirectional"))
    )
    (net (code "110") (name "/PRT_RXD") (class "Default")
      (node (ref "P23") (pin "4") (pinfunction "4_4") (pintype "passive"))
      (node (ref "R51") (pin "1") (pinfunction "1_1") (pintype "passive"))
    )
    (net (code "111") (name "/PRT_TXD") (class "Default")
      (node (ref "P23") (pin "3") (pinfunction "3_3") (pintype "passive"))
      (node (ref "R44") (pin "1") (pinfunction "1_1") (pintype "passive"))
    )
    (net (code "112") (name "/PW_1_C1") (class "Default")
      (node (ref "P1_C1") (pin "1") (pinfunction "1_1") (pintype "passive"))
      (node (ref "P_1_C1") (pin "1") (pinfunction "VOUT_1") (pintype "passive"))
    )
    (net (code "113") (name "/PW_1_C2") (class "Default")
      (node (ref "P1_C2") (pin "1") (pinfunction "1_1") (pintype "passive"))
      (node (ref "P_1_C2") (pin "1") (pinfunction "VOUT_1") (pintype "passive"))
    )
    (net (code "114") (name "/PW_1_C3") (class "Default")
      (node (ref "P1_C3") (pin "1") (pinfunction "1_1") (pintype "passive"))
      (node (ref "P_1_C3") (pin "1") (pinfunction "VOUT_1") (pintype "passive"))
    )
    (net (code "115") (name "/PW_1_C4") (class "Default")
      (node (ref "P1_C4") (pin "1") (pinfunction "1_1") (pintype "passive"))
      (node (ref "P_1_C4") (pin "1") (pinfunction "VOUT_1") (pintype "passive"))
    )
    (net (code "116") (name "/PW_1_C5") (class "Default")
      (node (ref "P1_C5") (pin "1") (pinfunction "1_1") (pintype "passive"))
      (node (ref "P_1_C5") (pin "1") (pinfunction "VOUT_1") (pintype "passive"))
    )
    (net (code "117") (name "/PW_1_C6") (class "Default")
      (node (ref "P1_C6") (pin "1") (pinfunction "1_1") (pintype "passive"))
      (node (ref "P_1_C6") (pin "1") (pinfunction "VOUT_1") (pintype "passive"))
    )
    (net (code "118") (name "/PW_2_C1") (class "Default")
      (node (ref "P2_C1") (pin "1") (pinfunction "1_1") (pintype "passive"))
      (node (ref "P_2_C1") (pin "1") (pinfunction "VOUT_1") (pintype "passive"))
    )
    (net (code "119") (name "/PW_2_C2") (class "Default")
      (node (ref "P2_C2") (pin "1") (pinfunction "1_1") (pintype "passive"))
      (node (ref "P_2_C2") (pin "1") (pinfunction "VOUT_1") (pintype "passive"))
    )
    (net (code "120") (name "/PW_2_C3") (class "Default")
      (node (ref "P2_C3") (pin "1") (pinfunction "1_1") (pintype "passive"))
      (node (ref "P_2_C3") (pin "1") (pinfunction "VOUT_1") (pintype "passive"))
    )
    (net (code "121") (name "/PW_2_C4") (class "Default")
      (node (ref "P2_C4") (pin "1") (pinfunction "1_1") (pintype "passive"))
      (node (ref "P_2_C4") (pin "1") (pinfunction "VOUT_1") (pintype "passive"))
    )
    (net (code "122") (name "/PW_2_C5") (class "Default")
      (node (ref "P2_C5") (pin "1") (pinfunction "1_1") (pintype "passive"))
      (node (ref "P_2_C5") (pin "1") (pinfunction "VOUT_1") (pintype "passive"))
    )
    (net (code "123") (name "/PW_2_C6") (class "Default")
      (node (ref "P2_C6") (pin "1") (pinfunction "1_1") (pintype "passive"))
      (node (ref "P_2_C6") (pin "1") (pinfunction "VOUT_1") (pintype "passive"))
    )
    (net (code "124") (name "/PW_3_C1") (class "Default")
      (node (ref "P3_C1") (pin "1") (pinfunction "1_1") (pintype "passive"))
      (node (ref "P_3_C1") (pin "1") (pinfunction "VOUT_1") (pintype "passive"))
    )
    (net (code "125") (name "/PW_3_C2") (class "Default")
      (node (ref "P3_C2") (pin "1") (pinfunction "1_1") (pintype "passive"))
      (node (ref "P_3_C2") (pin "1") (pinfunction "VOUT_1") (pintype "passive"))
    )
    (net (code "126") (name "/PW_3_C3") (class "Default")
      (node (ref "P3_C3") (pin "1") (pinfunction "1_1") (pintype "passive"))
      (node (ref "P_3_C3") (pin "1") (pinfunction "VOUT_1") (pintype "passive"))
    )
    (net (code "127") (name "/PW_3_C4") (class "Default")
      (node (ref "P3_C4") (pin "1") (pinfunction "1_1") (pintype "passive"))
      (node (ref "P_3_C4") (pin "1") (pinfunction "VOUT_1") (pintype "passive"))
    )
    (net (code "128") (name "/PW_3_C5") (class "Default")
      (node (ref "P3-C5") (pin "1") (pinfunction "1_1") (pintype "passive"))
      (node (ref "P_3_C5") (pin "1") (pinfunction "VOUT_1") (pintype "passive"))
    )
    (net (code "129") (name "/PW_3_C6") (class "Default")
      (node (ref "P3-C6") (pin "1") (pinfunction "1_1") (pintype "passive"))
      (node (ref "P_3_C6") (pin "1") (pinfunction "VOUT_1") (pintype "passive"))
    )
    (net (code "130") (name "/PW_4_C1") (class "Default")
      (node (ref "P4_C1") (pin "1") (pinfunction "1_1") (pintype "passive"))
      (node (ref "P_4_C1") (pin "1") (pinfunction "VOUT_1") (pintype "passive"))
    )
    (net (code "131") (name "/PW_4_C2") (class "Default")
      (node (ref "P4_C2") (pin "1") (pinfunction "1_1") (pintype "passive"))
      (node (ref "P_4_C2") (pin "1") (pinfunction "VOUT_1") (pintype "passive"))
    )
    (net (code "132") (name "/PW_4_C3") (class "Default")
      (node (ref "P4_C3") (pin "1") (pinfunction "1_1") (pintype "passive"))
      (node (ref "P_4_C3") (pin "1") (pinfunction "VOUT_1") (pintype "passive"))
    )
    (net (code "133") (name "/PW_4_C4") (class "Default")
      (node (ref "P4_C4") (pin "1") (pinfunction "1_1") (pintype "passive"))
      (node (ref "P_4_C4") (pin "1") (pinfunction "VOUT_1") (pintype "passive"))
    )
    (net (code "134") (name "/PW_4_C5") (class "Default")
      (node (ref "P4_C5") (pin "1") (pinfunction "1_1") (pintype "passive"))
      (node (ref "P_4_C5") (pin "1") (pinfunction "VOUT_1") (pintype "passive"))
    )
    (net (code "135") (name "/PW_4_C6") (class "Default")
      (node (ref "P4_C6") (pin "1") (pinfunction "1_1") (pintype "passive"))
      (node (ref "P_4_C6") (pin "1") (pinfunction "VOUT_1") (pintype "passive"))
    )
    (net (code "136") (name "/QH1'") (class "Default")
      (node (ref "U14") (pin "14") (pinfunction "SER_14") (pintype "passive"))
      (node (ref "U5") (pin "9") (pinfunction "QH'_9") (pintype "passive"))
    )
    (net (code "137") (name "/QH2'") (class "Default")
      (node (ref "U14") (pin "9") (pinfunction "QH'_9") (pintype "passive"))
      (node (ref "U15") (pin "14") (pinfunction "SER_14") (pintype "passive"))
    )
    (net (code "138") (name "/RCLK_1") (class "Default")
      (node (ref "U14") (pin "12") (pinfunction "RCLK_12") (pintype "passive"))
      (node (ref "U15") (pin "12") (pinfunction "RCLK_12") (pintype "passive"))
      (node (ref "U5") (pin "12") (pinfunction "RCLK_12") (pintype "passive"))
      (node (ref "U6") (pin "29") (pinfunction "PA8_29") (pintype "bidirectional"))
    )
    (net (code "139") (name "/SRCLK_1") (class "Default")
      (node (ref "U14") (pin "11") (pinfunction "SRCLK_11") (pintype "passive"))
      (node (ref "U15") (pin "11") (pinfunction "SRCLK_11") (pintype "passive"))
      (node (ref "U5") (pin "11") (pinfunction "SRCLK_11") (pintype "passive"))
      (node (ref "U6") (pin "27") (pinfunction "PB14_27") (pintype "bidirectional"))
    )
    (net (code "140") (name "/SWCLK") (class "Default")
      (node (ref "P17") (pin "4") (pinfunction "4_4") (pintype "passive"))
      (node (ref "U3") (pin "1") (pinfunction "1_1") (pintype "passive"))
      (node (ref "U6") (pin "37") (pinfunction "PA14/JTCK/SWCLK_37") (pintype "bidirectional"))
    )
    (net (code "141") (name "/SWDIO") (class "Default")
      (node (ref "P17") (pin "3") (pinfunction "3_3") (pintype "passive"))
      (node (ref "U3") (pin "3") (pinfunction "3_3") (pintype "passive"))
      (node (ref "U6") (pin "34") (pinfunction "PA13/JTMS/SWDIO_34") (pintype "bidirectional"))
    )
    (net (code "142") (name "/TCK_1_C1") (class "Default")
      (node (ref "P1_C1") (pin "4") (pinfunction "4_4") (pintype "passive"))
      (node (ref "S_1_C1") (pin "7") (pinfunction "NO3_7") (pintype "passive"))
    )
    (net (code "143") (name "/TCK_1_C2") (class "Default")
      (node (ref "P1_C2") (pin "4") (pinfunction "4_4") (pintype "passive"))
      (node (ref "S_1_C2") (pin "7") (pinfunction "NO3_7") (pintype "passive"))
    )
    (net (code "144") (name "/TCK_1_C3") (class "Default")
      (node (ref "P1_C3") (pin "4") (pinfunction "4_4") (pintype "passive"))
      (node (ref "S_1_C3") (pin "7") (pinfunction "NO3_7") (pintype "passive"))
    )
    (net (code "145") (name "/TCK_1_C4") (class "Default")
      (node (ref "P1_C4") (pin "4") (pinfunction "4_4") (pintype "passive"))
      (node (ref "S_1_C4") (pin "7") (pinfunction "NO3_7") (pintype "passive"))
    )
    (net (code "146") (name "/TCK_1_C5") (class "Default")
      (node (ref "P1_C5") (pin "4") (pinfunction "4_4") (pintype "passive"))
      (node (ref "S_1_C5") (pin "7") (pinfunction "NO3_7") (pintype "passive"))
    )
    (net (code "147") (name "/TCK_1_C6") (class "Default")
      (node (ref "P1_C6") (pin "4") (pinfunction "4_4") (pintype "passive"))
      (node (ref "S_1_C6") (pin "7") (pinfunction "NO3_7") (pintype "passive"))
    )
    (net (code "148") (name "/TCK_2_C1") (class "Default")
      (node (ref "P2_C1") (pin "4") (pinfunction "4_4") (pintype "passive"))
      (node (ref "S_2_C1") (pin "7") (pinfunction "NO3_7") (pintype "passive"))
    )
    (net (code "149") (name "/TCK_2_C2") (class "Default")
      (node (ref "P2_C2") (pin "4") (pinfunction "4_4") (pintype "passive"))
      (node (ref "S_2_C2") (pin "7") (pinfunction "NO3_7") (pintype "passive"))
    )
    (net (code "150") (name "/TCK_2_C3") (class "Default")
      (node (ref "P2_C3") (pin "4") (pinfunction "4_4") (pintype "passive"))
      (node (ref "S_2_C3") (pin "7") (pinfunction "NO3_7") (pintype "passive"))
    )
    (net (code "151") (name "/TCK_2_C4") (class "Default")
      (node (ref "P2_C4") (pin "4") (pinfunction "4_4") (pintype "passive"))
      (node (ref "S_2_C4") (pin "7") (pinfunction "NO3_7") (pintype "passive"))
    )
    (net (code "152") (name "/TCK_2_C5") (class "Default")
      (node (ref "P2_C5") (pin "4") (pinfunction "4_4") (pintype "passive"))
      (node (ref "S_2_C5") (pin "7") (pinfunction "NO3_7") (pintype "passive"))
    )
    (net (code "153") (name "/TCK_2_C6") (class "Default")
      (node (ref "P2_C6") (pin "4") (pinfunction "4_4") (pintype "passive"))
      (node (ref "S_2_C6") (pin "7") (pinfunction "NO3_7") (pintype "passive"))
    )
    (net (code "154") (name "/TCK_3_C1") (class "Default")
      (node (ref "P3_C1") (pin "4") (pinfunction "4_4") (pintype "passive"))
      (node (ref "S_3_C1") (pin "7") (pinfunction "NO3_7") (pintype "passive"))
    )
    (net (code "155") (name "/TCK_3_C2") (class "Default")
      (node (ref "P3_C2") (pin "4") (pinfunction "4_4") (pintype "passive"))
      (node (ref "S_3_C2") (pin "7") (pinfunction "NO3_7") (pintype "passive"))
    )
    (net (code "156") (name "/TCK_3_C3") (class "Default")
      (node (ref "P3_C3") (pin "4") (pinfunction "4_4") (pintype "passive"))
      (node (ref "S_3_C3") (pin "7") (pinfunction "NO3_7") (pintype "passive"))
    )
    (net (code "157") (name "/TCK_3_C4") (class "Default")
      (node (ref "P3_C4") (pin "4") (pinfunction "4_4") (pintype "passive"))
      (node (ref "S_3_C4") (pin "7") (pinfunction "NO3_7") (pintype "passive"))
    )
    (net (code "158") (name "/TCK_3_C5") (class "Default")
      (node (ref "P3-C5") (pin "4") (pinfunction "4_4") (pintype "passive"))
      (node (ref "S_3_C5") (pin "7") (pinfunction "NO3_7") (pintype "passive"))
    )
    (net (code "159") (name "/TCK_3_C6") (class "Default")
      (node (ref "P3-C6") (pin "4") (pinfunction "4_4") (pintype "passive"))
      (node (ref "S_3_C6") (pin "7") (pinfunction "NO3_7") (pintype "passive"))
    )
    (net (code "160") (name "/TCK_4_C1") (class "Default")
      (node (ref "P4_C1") (pin "4") (pinfunction "4_4") (pintype "passive"))
      (node (ref "S_4_C1") (pin "7") (pinfunction "NO3_7") (pintype "passive"))
    )
    (net (code "161") (name "/TCK_4_C2") (class "Default")
      (node (ref "P4_C2") (pin "4") (pinfunction "4_4") (pintype "passive"))
      (node (ref "S_4_C2") (pin "7") (pinfunction "NO3_7") (pintype "passive"))
    )
    (net (code "162") (name "/TCK_4_C3") (class "Default")
      (node (ref "P4_C3") (pin "4") (pinfunction "4_4") (pintype "passive"))
      (node (ref "S_4_C3") (pin "7") (pinfunction "NO3_7") (pintype "passive"))
    )
    (net (code "163") (name "/TCK_4_C4") (class "Default")
      (node (ref "P4_C4") (pin "4") (pinfunction "4_4") (pintype "passive"))
      (node (ref "S_4_C4") (pin "7") (pinfunction "NO3_7") (pintype "passive"))
    )
    (net (code "164") (name "/TCK_4_C5") (class "Default")
      (node (ref "P4_C5") (pin "4") (pinfunction "4_4") (pintype "passive"))
      (node (ref "S_4_C5") (pin "7") (pinfunction "NO3_7") (pintype "passive"))
    )
    (net (code "165") (name "/TCK_4_C6") (class "Default")
      (node (ref "P4_C6") (pin "4") (pinfunction "4_4") (pintype "passive"))
      (node (ref "S_4_C6") (pin "7") (pinfunction "NO3_7") (pintype "passive"))
    )
    (net (code "166") (name "/TDI_1_C1") (class "Default")
      (node (ref "ISP_1_C1&2") (pin "5") (pinfunction "NC2_5") (pintype "passive"))
      (node (ref "P1_C1") (pin "3") (pinfunction "3_3") (pintype "passive"))
    )
    (net (code "167") (name "/TDI_1_C1_1") (class "Default")
      (node (ref "ISP_1_C1&2") (pin "4") (pinfunction "COM2_4") (pintype "passive"))
      (node (ref "S_1_C1") (pin "3") (pinfunction "NO2_3") (pintype "passive"))
    )
    (net (code "168") (name "/TDI_1_C2") (class "Default")
      (node (ref "ISP_1_C1&2") (pin "13") (pinfunction "NC4_13") (pintype "passive"))
      (node (ref "P1_C2") (pin "3") (pinfunction "3_3") (pintype "passive"))
    )
    (net (code "169") (name "/TDI_1_C2_1") (class "Default")
      (node (ref "ISP_1_C1&2") (pin "12") (pinfunction "COM4_12") (pintype "passive"))
      (node (ref "S_1_C2") (pin "3") (pinfunction "NO2_3") (pintype "passive"))
    )
    (net (code "170") (name "/TDI_1_C3") (class "Default")
      (node (ref "ISP_1_C3&4") (pin "5") (pinfunction "NC2_5") (pintype "passive"))
      (node (ref "P1_C3") (pin "3") (pinfunction "3_3") (pintype "passive"))
    )
    (net (code "171") (name "/TDI_1_C3_1") (class "Default")
      (node (ref "ISP_1_C3&4") (pin "4") (pinfunction "COM2_4") (pintype "passive"))
      (node (ref "S_1_C3") (pin "3") (pinfunction "NO2_3") (pintype "passive"))
    )
    (net (code "172") (name "/TDI_1_C4") (class "Default")
      (node (ref "ISP_1_C3&4") (pin "13") (pinfunction "NC4_13") (pintype "passive"))
      (node (ref "P1_C4") (pin "3") (pinfunction "3_3") (pintype "passive"))
    )
    (net (code "173") (name "/TDI_1_C4_1") (class "Default")
      (node (ref "ISP_1_C3&4") (pin "12") (pinfunction "COM4_12") (pintype "passive"))
      (node (ref "S_1_C4") (pin "3") (pinfunction "NO2_3") (pintype "passive"))
    )
    (net (code "174") (name "/TDI_1_C5") (class "Default")
      (node (ref "ISP_1_C5&6") (pin "5") (pinfunction "NC2_5") (pintype "passive"))
      (node (ref "P1_C5") (pin "3") (pinfunction "3_3") (pintype "passive"))
    )
    (net (code "175") (name "/TDI_1_C5_1") (class "Default")
      (node (ref "ISP_1_C5&6") (pin "4") (pinfunction "COM2_4") (pintype "passive"))
      (node (ref "S_1_C5") (pin "3") (pinfunction "NO2_3") (pintype "passive"))
    )
    (net (code "176") (name "/TDI_1_C6") (class "Default")
      (node (ref "ISP_1_C5&6") (pin "13") (pinfunction "NC4_13") (pintype "passive"))
      (node (ref "P1_C6") (pin "3") (pinfunction "3_3") (pintype "passive"))
    )
    (net (code "177") (name "/TDI_1_C6_1") (class "Default")
      (node (ref "ISP_1_C5&6") (pin "12") (pinfunction "COM4_12") (pintype "passive"))
      (node (ref "S_1_C6") (pin "3") (pinfunction "NO2_3") (pintype "passive"))
    )
    (net (code "178") (name "/TDI_2_C1") (class "Default")
      (node (ref "ISP_2_C1&2") (pin "5") (pinfunction "NC2_5") (pintype "passive"))
      (node (ref "P2_C1") (pin "3") (pinfunction "3_3") (pintype "passive"))
    )
    (net (code "179") (name "/TDI_2_C1_1") (class "Default")
      (node (ref "ISP_2_C1&2") (pin "4") (pinfunction "COM2_4") (pintype "passive"))
      (node (ref "S_2_C1") (pin "3") (pinfunction "NO2_3") (pintype "passive"))
    )
    (net (code "180") (name "/TDI_2_C2") (class "Default")
      (node (ref "ISP_2_C1&2") (pin "13") (pinfunction "NC4_13") (pintype "passive"))
      (node (ref "P2_C2") (pin "3") (pinfunction "3_3") (pintype "passive"))
    )
    (net (code "181") (name "/TDI_2_C2_1") (class "Default")
      (node (ref "ISP_2_C1&2") (pin "12") (pinfunction "COM4_12") (pintype "passive"))
      (node (ref "S_2_C2") (pin "3") (pinfunction "NO2_3") (pintype "passive"))
    )
    (net (code "182") (name "/TDI_2_C3") (class "Default")
      (node (ref "ISP_2_C3&4") (pin "5") (pinfunction "NC2_5") (pintype "passive"))
      (node (ref "P2_C3") (pin "3") (pinfunction "3_3") (pintype "passive"))
    )
    (net (code "183") (name "/TDI_2_C3_1") (class "Default")
      (node (ref "ISP_2_C3&4") (pin "4") (pinfunction "COM2_4") (pintype "passive"))
      (node (ref "S_2_C3") (pin "3") (pinfunction "NO2_3") (pintype "passive"))
    )
    (net (code "184") (name "/TDI_2_C4") (class "Default")
      (node (ref "ISP_2_C3&4") (pin "13") (pinfunction "NC4_13") (pintype "passive"))
      (node (ref "P2_C4") (pin "3") (pinfunction "3_3") (pintype "passive"))
    )
    (net (code "185") (name "/TDI_2_C4_1") (class "Default")
      (node (ref "ISP_2_C3&4") (pin "12") (pinfunction "COM4_12") (pintype "passive"))
      (node (ref "S_2_C4") (pin "3") (pinfunction "NO2_3") (pintype "passive"))
    )
    (net (code "186") (name "/TDI_2_C5") (class "Default")
      (node (ref "ISP_2_C5&6") (pin "5") (pinfunction "NC2_5") (pintype "passive"))
      (node (ref "P2_C5") (pin "3") (pinfunction "3_3") (pintype "passive"))
    )
    (net (code "187") (name "/TDI_2_C5_1") (class "Default")
      (node (ref "ISP_2_C5&6") (pin "4") (pinfunction "COM2_4") (pintype "passive"))
      (node (ref "S_2_C5") (pin "3") (pinfunction "NO2_3") (pintype "passive"))
    )
    (net (code "188") (name "/TDI_2_C6") (class "Default")
      (node (ref "ISP_2_C5&6") (pin "13") (pinfunction "NC4_13") (pintype "passive"))
      (node (ref "P2_C6") (pin "3") (pinfunction "3_3") (pintype "passive"))
    )
    (net (code "189") (name "/TDI_2_C6_1") (class "Default")
      (node (ref "ISP_2_C5&6") (pin "12") (pinfunction "COM4_12") (pintype "passive"))
      (node (ref "S_2_C6") (pin "3") (pinfunction "NO2_3") (pintype "passive"))
    )
    (net (code "190") (name "/TDI_3_C1") (class "Default")
      (node (ref "ISP_3_C1&2") (pin "5") (pinfunction "NC2_5") (pintype "passive"))
      (node (ref "P3_C1") (pin "3") (pinfunction "3_3") (pintype "passive"))
    )
    (net (code "191") (name "/TDI_3_C1_1") (class "Default")
      (node (ref "ISP_3_C1&2") (pin "4") (pinfunction "COM2_4") (pintype "passive"))
      (node (ref "S_3_C1") (pin "3") (pinfunction "NO2_3") (pintype "passive"))
    )
    (net (code "192") (name "/TDI_3_C2") (class "Default")
      (node (ref "ISP_3_C1&2") (pin "13") (pinfunction "NC4_13") (pintype "passive"))
      (node (ref "P3_C2") (pin "3") (pinfunction "3_3") (pintype "passive"))
    )
    (net (code "193") (name "/TDI_3_C2_1") (class "Default")
      (node (ref "ISP_3_C1&2") (pin "12") (pinfunction "COM4_12") (pintype "passive"))
      (node (ref "S_3_C2") (pin "3") (pinfunction "NO2_3") (pintype "passive"))
    )
    (net (code "194") (name "/TDI_3_C3") (class "Default")
      (node (ref "ISP_3_C3&4") (pin "5") (pinfunction "NC2_5") (pintype "passive"))
      (node (ref "P3_C3") (pin "3") (pinfunction "3_3") (pintype "passive"))
    )
    (net (code "195") (name "/TDI_3_C3_1") (class "Default")
      (node (ref "ISP_3_C3&4") (pin "4") (pinfunction "COM2_4") (pintype "passive"))
      (node (ref "S_3_C3") (pin "3") (pinfunction "NO2_3") (pintype "passive"))
    )
    (net (code "196") (name "/TDI_3_C4") (class "Default")
      (node (ref "ISP_3_C3&4") (pin "13") (pinfunction "NC4_13") (pintype "passive"))
      (node (ref "P3_C4") (pin "3") (pinfunction "3_3") (pintype "passive"))
    )
    (net (code "197") (name "/TDI_3_C4_1") (class "Default")
      (node (ref "ISP_3_C3&4") (pin "12") (pinfunction "COM4_12") (pintype "passive"))
      (node (ref "S_3_C4") (pin "3") (pinfunction "NO2_3") (pintype "passive"))
    )
    (net (code "198") (name "/TDI_3_C5") (class "Default")
      (node (ref "ISP_3_C5&6") (pin "5") (pinfunction "NC2_5") (pintype "passive"))
      (node (ref "P3-C5") (pin "3") (pinfunction "3_3") (pintype "passive"))
    )
    (net (code "199") (name "/TDI_3_C5_1") (class "Default")
      (node (ref "ISP_3_C5&6") (pin "4") (pinfunction "COM2_4") (pintype "passive"))
      (node (ref "S_3_C5") (pin "3") (pinfunction "NO2_3") (pintype "passive"))
    )
    (net (code "200") (name "/TDI_3_C6") (class "Default")
      (node (ref "ISP_3_C5&6") (pin "13") (pinfunction "NC4_13") (pintype "passive"))
      (node (ref "P3-C6") (pin "3") (pinfunction "3_3") (pintype "passive"))
    )
    (net (code "201") (name "/TDI_3_C6_1") (class "Default")
      (node (ref "ISP_3_C5&6") (pin "12") (pinfunction "COM4_12") (pintype "passive"))
      (node (ref "S_3_C6") (pin "3") (pinfunction "NO2_3") (pintype "passive"))
    )
    (net (code "202") (name "/TDI_4_C1") (class "Default")
      (node (ref "ISP_4_C1&2") (pin "5") (pinfunction "NC2_5") (pintype "passive"))
      (node (ref "P4_C1") (pin "3") (pinfunction "3_3") (pintype "passive"))
    )
    (net (code "203") (name "/TDI_4_C1_1") (class "Default")
      (node (ref "ISP_4_C1&2") (pin "4") (pinfunction "COM2_4") (pintype "passive"))
      (node (ref "S_4_C1") (pin "3") (pinfunction "NO2_3") (pintype "passive"))
    )
    (net (code "204") (name "/TDI_4_C2") (class "Default")
      (node (ref "ISP_4_C1&2") (pin "13") (pinfunction "NC4_13") (pintype "passive"))
      (node (ref "P4_C2") (pin "3") (pinfunction "3_3") (pintype "passive"))
    )
    (net (code "205") (name "/TDI_4_C2_1") (class "Default")
      (node (ref "ISP_4_C1&2") (pin "12") (pinfunction "COM4_12") (pintype "passive"))
      (node (ref "S_4_C2") (pin "3") (pinfunction "NO2_3") (pintype "passive"))
    )
    (net (code "206") (name "/TDI_4_C3") (class "Default")
      (node (ref "ISP_4_C3&4") (pin "5") (pinfunction "NC2_5") (pintype "passive"))
      (node (ref "P4_C3") (pin "3") (pinfunction "3_3") (pintype "passive"))
    )
    (net (code "207") (name "/TDI_4_C3_1") (class "Default")
      (node (ref "ISP_4_C3&4") (pin "4") (pinfunction "COM2_4") (pintype "passive"))
      (node (ref "S_4_C3") (pin "3") (pinfunction "NO2_3") (pintype "passive"))
    )
    (net (code "208") (name "/TDI_4_C4") (class "Default")
      (node (ref "ISP_4_C3&4") (pin "13") (pinfunction "NC4_13") (pintype "passive"))
      (node (ref "P4_C4") (pin "3") (pinfunction "3_3") (pintype "passive"))
    )
    (net (code "209") (name "/TDI_4_C4_1") (class "Default")
      (node (ref "ISP_4_C3&4") (pin "12") (pinfunction "COM4_12") (pintype "passive"))
      (node (ref "S_4_C4") (pin "3") (pinfunction "NO2_3") (pintype "passive"))
    )
    (net (code "210") (name "/TDI_4_C5") (class "Default")
      (node (ref "ISP_4_C5&6") (pin "5") (pinfunction "NC2_5") (pintype "passive"))
      (node (ref "P4_C5") (pin "3") (pinfunction "3_3") (pintype "passive"))
    )
    (net (code "211") (name "/TDI_4_C5_1") (class "Default")
      (node (ref "ISP_4_C5&6") (pin "4") (pinfunction "COM2_4") (pintype "passive"))
      (node (ref "S_4_C5") (pin "3") (pinfunction "NO2_3") (pintype "passive"))
    )
    (net (code "212") (name "/TDI_4_C6") (class "Default")
      (node (ref "ISP_4_C5&6") (pin "13") (pinfunction "NC4_13") (pintype "passive"))
      (node (ref "P4_C6") (pin "3") (pinfunction "3_3") (pintype "passive"))
    )
    (net (code "213") (name "/TDI_4_C6_1") (class "Default")
      (node (ref "ISP_4_C5&6") (pin "12") (pinfunction "COM4_12") (pintype "passive"))
      (node (ref "S_4_C6") (pin "3") (pinfunction "NO2_3") (pintype "passive"))
    )
    (net (code "214") (name "/TDO_1_C1") (class "Default")
      (node (ref "ISP_1_C1&2") (pin "1") (pinfunction "NC1_1") (pintype "passive"))
      (node (ref "P1_C1") (pin "2") (pinfunction "2_2") (pintype "passive"))
    )
    (net (code "215") (name "/TDO_1_C1_1") (class "Default")
      (node (ref "ISP_1_C1&2") (pin "16") (pinfunction "COM1_16") (pintype "passive"))
      (node (ref "S_1_C1") (pin "15") (pinfunction "NO1_15") (pintype "passive"))
    )
    (net (code "216") (name "/TDO_1_C2") (class "Default")
      (node (ref "ISP_1_C1&2") (pin "9") (pinfunction "NC3_9") (pintype "passive"))
      (node (ref "P1_C2") (pin "2") (pinfunction "2_2") (pintype "passive"))
    )
    (net (code "217") (name "/TDO_1_C2_1") (class "Default")
      (node (ref "ISP_1_C1&2") (pin "8") (pinfunction "COM3_8") (pintype "passive"))
      (node (ref "S_1_C2") (pin "15") (pinfunction "NO1_15") (pintype "passive"))
    )
    (net (code "218") (name "/TDO_1_C3") (class "Default")
      (node (ref "ISP_1_C3&4") (pin "1") (pinfunction "NC1_1") (pintype "passive"))
      (node (ref "P1_C3") (pin "2") (pinfunction "2_2") (pintype "passive"))
    )
    (net (code "219") (name "/TDO_1_C3_1") (class "Default")
      (node (ref "ISP_1_C3&4") (pin "16") (pinfunction "COM1_16") (pintype "passive"))
      (node (ref "S_1_C3") (pin "15") (pinfunction "NO1_15") (pintype "passive"))
    )
    (net (code "220") (name "/TDO_1_C4") (class "Default")
      (node (ref "ISP_1_C3&4") (pin "9") (pinfunction "NC3_9") (pintype "passive"))
      (node (ref "P1_C4") (pin "2") (pinfunction "2_2") (pintype "passive"))
    )
    (net (code "221") (name "/TDO_1_C4_1") (class "Default")
      (node (ref "ISP_1_C3&4") (pin "8") (pinfunction "COM3_8") (pintype "passive"))
      (node (ref "S_1_C4") (pin "15") (pinfunction "NO1_15") (pintype "passive"))
    )
    (net (code "222") (name "/TDO_1_C5") (class "Default")
      (node (ref "ISP_1_C5&6") (pin "1") (pinfunction "NC1_1") (pintype "passive"))
      (node (ref "P1_C5") (pin "2") (pinfunction "2_2") (pintype "passive"))
    )
    (net (code "223") (name "/TDO_1_C5_1") (class "Default")
      (node (ref "ISP_1_C5&6") (pin "16") (pinfunction "COM1_16") (pintype "passive"))
      (node (ref "S_1_C5") (pin "15") (pinfunction "NO1_15") (pintype "passive"))
    )
    (net (code "224") (name "/TDO_1_C6") (class "Default")
      (node (ref "ISP_1_C5&6") (pin "9") (pinfunction "NC3_9") (pintype "passive"))
      (node (ref "P1_C6") (pin "2") (pinfunction "2_2") (pintype "passive"))
    )
    (net (code "225") (name "/TDO_1_C6_1") (class "Default")
      (node (ref "ISP_1_C5&6") (pin "8") (pinfunction "COM3_8") (pintype "passive"))
      (node (ref "S_1_C6") (pin "15") (pinfunction "NO1_15") (pintype "passive"))
    )
    (net (code "226") (name "/TDO_2_C1") (class "Default")
      (node (ref "ISP_2_C1&2") (pin "1") (pinfunction "NC1_1") (pintype "passive"))
      (node (ref "P2_C1") (pin "2") (pinfunction "2_2") (pintype "passive"))
    )
    (net (code "227") (name "/TDO_2_C1_1") (class "Default")
      (node (ref "ISP_2_C1&2") (pin "16") (pinfunction "COM1_16") (pintype "passive"))
      (node (ref "S_2_C1") (pin "15") (pinfunction "NO1_15") (pintype "passive"))
    )
    (net (code "228") (name "/TDO_2_C2") (class "Default")
      (node (ref "ISP_2_C1&2") (pin "9") (pinfunction "NC3_9") (pintype "passive"))
      (node (ref "P2_C2") (pin "2") (pinfunction "2_2") (pintype "passive"))
    )
    (net (code "229") (name "/TDO_2_C2_1") (class "Default")
      (node (ref "ISP_2_C1&2") (pin "8") (pinfunction "COM3_8") (pintype "passive"))
      (node (ref "S_2_C2") (pin "15") (pinfunction "NO1_15") (pintype "passive"))
    )
    (net (code "230") (name "/TDO_2_C3") (class "Default")
      (node (ref "ISP_2_C3&4") (pin "1") (pinfunction "NC1_1") (pintype "passive"))
      (node (ref "P2_C3") (pin "2") (pinfunction "2_2") (pintype "passive"))
    )
    (net (code "231") (name "/TDO_2_C3_1") (class "Default")
      (node (ref "ISP_2_C3&4") (pin "16") (pinfunction "COM1_16") (pintype "passive"))
      (node (ref "S_2_C3") (pin "15") (pinfunction "NO1_15") (pintype "passive"))
    )
    (net (code "232") (name "/TDO_2_C4") (class "Default")
      (node (ref "ISP_2_C3&4") (pin "9") (pinfunction "NC3_9") (pintype "passive"))
      (node (ref "P2_C4") (pin "2") (pinfunction "2_2") (pintype "passive"))
    )
    (net (code "233") (name "/TDO_2_C4_1") (class "Default")
      (node (ref "ISP_2_C3&4") (pin "8") (pinfunction "COM3_8") (pintype "passive"))
      (node (ref "S_2_C4") (pin "15") (pinfunction "NO1_15") (pintype "passive"))
    )
    (net (code "234") (name "/TDO_2_C5") (class "Default")
      (node (ref "ISP_2_C5&6") (pin "1") (pinfunction "NC1_1") (pintype "passive"))
      (node (ref "P2_C5") (pin "2") (pinfunction "2_2") (pintype "passive"))
    )
    (net (code "235") (name "/TDO_2_C5_1") (class "Default")
      (node (ref "ISP_2_C5&6") (pin "16") (pinfunction "COM1_16") (pintype "passive"))
      (node (ref "S_2_C5") (pin "15") (pinfunction "NO1_15") (pintype "passive"))
    )
    (net (code "236") (name "/TDO_2_C6") (class "Default")
      (node (ref "ISP_2_C5&6") (pin "9") (pinfunction "NC3_9") (pintype "passive"))
      (node (ref "P2_C6") (pin "2") (pinfunction "2_2") (pintype "passive"))
    )
    (net (code "237") (name "/TDO_2_C6_1") (class "Default")
      (node (ref "ISP_2_C5&6") (pin "8") (pinfunction "COM3_8") (pintype "passive"))
      (node (ref "S_2_C6") (pin "15") (pinfunction "NO1_15") (pintype "passive"))
    )
    (net (code "238") (name "/TDO_3_C1") (class "Default")
      (node (ref "ISP_3_C1&2") (pin "1") (pinfunction "NC1_1") (pintype "passive"))
      (node (ref "P3_C1") (pin "2") (pinfunction "2_2") (pintype "passive"))
    )
    (net (code "239") (name "/TDO_3_C1_1") (class "Default")
      (node (ref "ISP_3_C1&2") (pin "16") (pinfunction "COM1_16") (pintype "passive"))
      (node (ref "S_3_C1") (pin "15") (pinfunction "NO1_15") (pintype "passive"))
    )
    (net (code "240") (name "/TDO_3_C2") (class "Default")
      (node (ref "ISP_3_C1&2") (pin "9") (pinfunction "NC3_9") (pintype "passive"))
      (node (ref "P3_C2") (pin "2") (pinfunction "2_2") (pintype "passive"))
    )
    (net (code "241") (name "/TDO_3_C2_1") (class "Default")
      (node (ref "ISP_3_C1&2") (pin "8") (pinfunction "COM3_8") (pintype "passive"))
      (node (ref "S_3_C2") (pin "15") (pinfunction "NO1_15") (pintype "passive"))
    )
    (net (code "242") (name "/TDO_3_C3") (class "Default")
      (node (ref "ISP_3_C3&4") (pin "1") (pinfunction "NC1_1") (pintype "passive"))
      (node (ref "P3_C3") (pin "2") (pinfunction "2_2") (pintype "passive"))
    )
    (net (code "243") (name "/TDO_3_C3_1") (class "Default")
      (node (ref "ISP_3_C3&4") (pin "16") (pinfunction "COM1_16") (pintype "passive"))
      (node (ref "S_3_C3") (pin "15") (pinfunction "NO1_15") (pintype "passive"))
    )
    (net (code "244") (name "/TDO_3_C4") (class "Default")
      (node (ref "ISP_3_C3&4") (pin "9") (pinfunction "NC3_9") (pintype "passive"))
      (node (ref "P3_C4") (pin "2") (pinfunction "2_2") (pintype "passive"))
    )
    (net (code "245") (name "/TDO_3_C4_1") (class "Default")
      (node (ref "ISP_3_C3&4") (pin "8") (pinfunction "COM3_8") (pintype "passive"))
      (node (ref "S_3_C4") (pin "15") (pinfunction "NO1_15") (pintype "passive"))
    )
    (net (code "246") (name "/TDO_3_C5") (class "Default")
      (node (ref "ISP_3_C5&6") (pin "1") (pinfunction "NC1_1") (pintype "passive"))
      (node (ref "P3-C5") (pin "2") (pinfunction "2_2") (pintype "passive"))
    )
    (net (code "247") (name "/TDO_3_C5_1") (class "Default")
      (node (ref "ISP_3_C5&6") (pin "16") (pinfunction "COM1_16") (pintype "passive"))
      (node (ref "S_3_C5") (pin "15") (pinfunction "NO1_15") (pintype "passive"))
    )
    (net (code "248") (name "/TDO_3_C6") (class "Default")
      (node (ref "ISP_3_C5&6") (pin "9") (pinfunction "NC3_9") (pintype "passive"))
      (node (ref "P3-C6") (pin "2") (pinfunction "2_2") (pintype "passive"))
    )
    (net (code "249") (name "/TDO_3_C6_1") (class "Default")
      (node (ref "ISP_3_C5&6") (pin "8") (pinfunction "COM3_8") (pintype "passive"))
      (node (ref "S_3_C6") (pin "15") (pinfunction "NO1_15") (pintype "passive"))
    )
    (net (code "250") (name "/TDO_4_C1") (class "Default")
      (node (ref "ISP_4_C1&2") (pin "1") (pinfunction "NC1_1") (pintype "passive"))
      (node (ref "P4_C1") (pin "2") (pinfunction "2_2") (pintype "passive"))
    )
    (net (code "251") (name "/TDO_4_C1_1") (class "Default")
      (node (ref "ISP_4_C1&2") (pin "16") (pinfunction "COM1_16") (pintype "passive"))
      (node (ref "S_4_C1") (pin "15") (pinfunction "NO1_15") (pintype "passive"))
    )
    (net (code "252") (name "/TDO_4_C2") (class "Default")
      (node (ref "ISP_4_C1&2") (pin "9") (pinfunction "NC3_9") (pintype "passive"))
      (node (ref "P4_C2") (pin "2") (pinfunction "2_2") (pintype "passive"))
    )
    (net (code "253") (name "/TDO_4_C2_1") (class "Default")
      (node (ref "ISP_4_C1&2") (pin "8") (pinfunction "COM3_8") (pintype "passive"))
      (node (ref "S_4_C2") (pin "15") (pinfunction "NO1_15") (pintype "passive"))
    )
    (net (code "254") (name "/TDO_4_C3") (class "Default")
      (node (ref "ISP_4_C3&4") (pin "1") (pinfunction "NC1_1") (pintype "passive"))
      (node (ref "P4_C3") (pin "2") (pinfunction "2_2") (pintype "passive"))
    )
    (net (code "255") (name "/TDO_4_C3_1") (class "Default")
      (node (ref "ISP_4_C3&4") (pin "16") (pinfunction "COM1_16") (pintype "passive"))
      (node (ref "S_4_C3") (pin "15") (pinfunction "NO1_15") (pintype "passive"))
    )
    (net (code "256") (name "/TDO_4_C4") (class "Default")
      (node (ref "ISP_4_C3&4") (pin "9") (pinfunction "NC3_9") (pintype "passive"))
      (node (ref "P4_C4") (pin "2") (pinfunction "2_2") (pintype "passive"))
    )
    (net (code "257") (name "/TDO_4_C4_1") (class "Default")
      (node (ref "ISP_4_C3&4") (pin "8") (pinfunction "COM3_8") (pintype "passive"))
      (node (ref "S_4_C4") (pin "15") (pinfunction "NO1_15") (pintype "passive"))
    )
    (net (code "258") (name "/TDO_4_C5") (class "Default")
      (node (ref "ISP_4_C5&6") (pin "1") (pinfunction "NC1_1") (pintype "passive"))
      (node (ref "P4_C5") (pin "2") (pinfunction "2_2") (pintype "passive"))
    )
    (net (code "259") (name "/TDO_4_C5_1") (class "Default")
      (node (ref "ISP_4_C5&6") (pin "16") (pinfunction "COM1_16") (pintype "passive"))
      (node (ref "S_4_C5") (pin "15") (pinfunction "NO1_15") (pintype "passive"))
    )
    (net (code "260") (name "/TDO_4_C6") (class "Default")
      (node (ref "ISP_4_C5&6") (pin "9") (pinfunction "NC3_9") (pintype "passive"))
      (node (ref "P4_C6") (pin "2") (pinfunction "2_2") (pintype "passive"))
    )
    (net (code "261") (name "/TDO_4_C6_1") (class "Default")
      (node (ref "ISP_4_C5&6") (pin "8") (pinfunction "COM3_8") (pintype "passive"))
      (node (ref "S_4_C6") (pin "15") (pinfunction "NO1_15") (pintype "passive"))
    )
    (net (code "262") (name "/TMS_1_C1") (class "Default")
      (node (ref "P1_C1") (pin "5") (pinfunction "5_5") (pintype "passive"))
      (node (ref "S_1_C1") (pin "11") (pinfunction "NO4_11") (pintype "passive"))
    )
    (net (code "263") (name "/TMS_1_C2") (class "Default")
      (node (ref "P1_C2") (pin "5") (pinfunction "5_5") (pintype "passive"))
      (node (ref "S_1_C2") (pin "11") (pinfunction "NO4_11") (pintype "passive"))
    )
    (net (code "264") (name "/TMS_1_C3") (class "Default")
      (node (ref "P1_C3") (pin "5") (pinfunction "5_5") (pintype "passive"))
      (node (ref "S_1_C3") (pin "11") (pinfunction "NO4_11") (pintype "passive"))
    )
    (net (code "265") (name "/TMS_1_C4") (class "Default")
      (node (ref "P1_C4") (pin "5") (pinfunction "5_5") (pintype "passive"))
      (node (ref "S_1_C4") (pin "11") (pinfunction "NO4_11") (pintype "passive"))
    )
    (net (code "266") (name "/TMS_1_C5") (class "Default")
      (node (ref "P1_C5") (pin "5") (pinfunction "5_5") (pintype "passive"))
      (node (ref "S_1_C5") (pin "11") (pinfunction "NO4_11") (pintype "passive"))
    )
    (net (code "267") (name "/TMS_1_C6") (class "Default")
      (node (ref "P1_C6") (pin "5") (pinfunction "5_5") (pintype "passive"))
      (node (ref "S_1_C6") (pin "11") (pinfunction "NO4_11") (pintype "passive"))
    )
    (net (code "268") (name "/TMS_2_C1") (class "Default")
      (node (ref "P2_C1") (pin "5") (pinfunction "5_5") (pintype "passive"))
      (node (ref "S_2_C1") (pin "11") (pinfunction "NO4_11") (pintype "passive"))
    )
    (net (code "269") (name "/TMS_2_C2") (class "Default")
      (node (ref "P2_C2") (pin "5") (pinfunction "5_5") (pintype "passive"))
      (node (ref "S_2_C2") (pin "11") (pinfunction "NO4_11") (pintype "passive"))
    )
    (net (code "270") (name "/TMS_2_C3") (class "Default")
      (node (ref "P2_C3") (pin "5") (pinfunction "5_5") (pintype "passive"))
      (node (ref "S_2_C3") (pin "11") (pinfunction "NO4_11") (pintype "passive"))
    )
    (net (code "271") (name "/TMS_2_C4") (class "Default")
      (node (ref "P2_C4") (pin "5") (pinfunction "5_5") (pintype "passive"))
      (node (ref "S_2_C4") (pin "11") (pinfunction "NO4_11") (pintype "passive"))
    )
    (net (code "272") (name "/TMS_2_C5") (class "Default")
      (node (ref "P2_C5") (pin "5") (pinfunction "5_5") (pintype "passive"))
      (node (ref "S_2_C5") (pin "11") (pinfunction "NO4_11") (pintype "passive"))
    )
    (net (code "273") (name "/TMS_2_C6") (class "Default")
      (node (ref "P2_C6") (pin "5") (pinfunction "5_5") (pintype "passive"))
      (node (ref "S_2_C6") (pin "11") (pinfunction "NO4_11") (pintype "passive"))
    )
    (net (code "274") (name "/TMS_3_C1") (class "Default")
      (node (ref "P3_C1") (pin "5") (pinfunction "5_5") (pintype "passive"))
      (node (ref "S_3_C1") (pin "11") (pinfunction "NO4_11") (pintype "passive"))
    )
    (net (code "275") (name "/TMS_3_C2") (class "Default")
      (node (ref "P3_C2") (pin "5") (pinfunction "5_5") (pintype "passive"))
      (node (ref "S_3_C2") (pin "11") (pinfunction "NO4_11") (pintype "passive"))
    )
    (net (code "276") (name "/TMS_3_C3") (class "Default")
      (node (ref "P3_C3") (pin "5") (pinfunction "5_5") (pintype "passive"))
      (node (ref "S_3_C3") (pin "11") (pinfunction "NO4_11") (pintype "passive"))
    )
    (net (code "277") (name "/TMS_3_C4") (class "Default")
      (node (ref "P3_C4") (pin "5") (pinfunction "5_5") (pintype "passive"))
      (node (ref "S_3_C4") (pin "11") (pinfunction "NO4_11") (pintype "passive"))
    )
    (net (code "278") (name "/TMS_3_C5") (class "Default")
      (node (ref "P3-C5") (pin "5") (pinfunction "5_5") (pintype "passive"))
      (node (ref "S_3_C5") (pin "11") (pinfunction "NO4_11") (pintype "passive"))
    )
    (net (code "279") (name "/TMS_3_C6") (class "Default")
      (node (ref "P3-C6") (pin "5") (pinfunction "5_5") (pintype "passive"))
      (node (ref "S_3_C6") (pin "11") (pinfunction "NO4_11") (pintype "passive"))
    )
    (net (code "280") (name "/TMS_4_C1") (class "Default")
      (node (ref "P4_C1") (pin "5") (pinfunction "5_5") (pintype "passive"))
      (node (ref "S_4_C1") (pin "11") (pinfunction "NO4_11") (pintype "passive"))
    )
    (net (code "281") (name "/TMS_4_C2") (class "Default")
      (node (ref "P4_C2") (pin "5") (pinfunction "5_5") (pintype "passive"))
      (node (ref "S_4_C2") (pin "11") (pinfunction "NO4_11") (pintype "passive"))
    )
    (net (code "282") (name "/TMS_4_C3") (class "Default")
      (node (ref "P4_C3") (pin "5") (pinfunction "5_5") (pintype "passive"))
      (node (ref "S_4_C3") (pin "11") (pinfunction "NO4_11") (pintype "passive"))
    )
    (net (code "283") (name "/TMS_4_C4") (class "Default")
      (node (ref "P4_C4") (pin "5") (pinfunction "5_5") (pintype "passive"))
      (node (ref "S_4_C4") (pin "11") (pinfunction "NO4_11") (pintype "passive"))
    )
    (net (code "284") (name "/TMS_4_C5") (class "Default")
      (node (ref "P4_C5") (pin "5") (pinfunction "5_5") (pintype "passive"))
      (node (ref "S_4_C5") (pin "11") (pinfunction "NO4_11") (pintype "passive"))
    )
    (net (code "285") (name "/TMS_4_C6") (class "Default")
      (node (ref "P4_C6") (pin "5") (pinfunction "5_5") (pintype "passive"))
      (node (ref "S_4_C6") (pin "11") (pinfunction "NO4_11") (pintype "passive"))
    )
    (net (code "286") (name "3.3V") (class "Default")
      (node (ref "C10") (pin "1") (pinfunction "1_1") (pintype "passive"))
      (node (ref "C16") (pin "1") (pinfunction "1_1") (pintype "passive"))
      (node (ref "C30") (pin "1") (pinfunction "1_1") (pintype "passive"))
      (node (ref "C41") (pin "1") (pinfunction "1_1") (pintype "passive"))
      (node (ref "C42") (pin "1") (pinfunction "1_1") (pintype "passive"))
      (node (ref "C43") (pin "1") (pinfunction "1_1") (pintype "passive"))
      (node (ref "C6") (pin "1") (pinfunction "1_1") (pintype "passive"))
      (node (ref "C7") (pin "1") (pinfunction "1_1") (pintype "passive"))
      (node (ref "C8") (pin "1") (pinfunction "1_1") (pintype "passive"))
      (node (ref "C9") (pin "1") (pinfunction "1_1") (pintype "passive"))
      (node (ref "ISP_1_C1&2") (pin "14") (pinfunction "V+_14") (pintype "passive"))
      (node (ref "ISP_1_C3&4") (pin "14") (pinfunction "V+_14") (pintype "passive"))
      (node (ref "ISP_1_C5&6") (pin "14") (pinfunction "V+_14") (pintype "passive"))
      (node (ref "ISP_2_C1&2") (pin "14") (pinfunction "V+_14") (pintype "passive"))
      (node (ref "ISP_2_C3&4") (pin "14") (pinfunction "V+_14") (pintype "passive"))
      (node (ref "ISP_2_C5&6") (pin "14") (pinfunction "V+_14") (pintype "passive"))
      (node (ref "ISP_3_C1&2") (pin "14") (pinfunction "V+_14") (pintype "passive"))
      (node (ref "ISP_3_C3&4") (pin "14") (pinfunction "V+_14") (pintype "passive"))
      (node (ref "ISP_3_C5&6") (pin "14") (pinfunction "V+_14") (pintype "passive"))
      (node (ref "ISP_4_C1&2") (pin "14") (pinfunction "V+_14") (pintype "passive"))
      (node (ref "ISP_4_C3&4") (pin "14") (pinfunction "V+_14") (pintype "passive"))
      (node (ref "ISP_4_C5&6") (pin "14") (pinfunction "V+_14") (pintype "passive"))
      (node (ref "J-I-S") (pin "14") (pinfunction "V+_14") (pintype "passive"))
      (node (ref "LS1") (pin "1") (pinfunction "1_1") (pintype "passive"))
      (node (ref "P17") (pin "1") (pinfunction "1_1") (pintype "passive"))
      (node (ref "P18") (pin "1") (pinfunction "1_1") (pintype "passive"))
      (node (ref "R12") (pin "2") (pinfunction "2_2") (pintype "passive"))
      (node (ref "R15") (pin "2") (pinfunction "2_2") (pintype "passive"))
      (node (ref "R3") (pin "1") (pinfunction "1_1") (pintype "passive"))
      (node (ref "R67") (pin "1") (pinfunction "1_1") (pintype "passive"))
      (node (ref "R68") (pin "1") (pinfunction "1_1") (pintype "passive"))
      (node (ref "R69") (pin "1") (pinfunction "1_1") (pintype "passive"))
      (node (ref "S1") (pin "1") (pinfunction "1_1") (pintype "passive"))
      (node (ref "S1") (pin "2") (pinfunction "2_2") (pintype "passive"))
      (node (ref "S2") (pin "1") (pinfunction "1_1") (pintype "passive"))
      (node (ref "S2") (pin "2") (pinfunction "2_2") (pintype "passive"))
      (node (ref "SW1") (pin "1") (pinfunction "1_1") (pintype "passive"))
      (node (ref "S_1_C1") (pin "14") (pinfunction "V+_14") (pintype "passive"))
      (node (ref "S_1_C2") (pin "14") (pinfunction "V+_14") (pintype "passive"))
      (node (ref "S_1_C3") (pin "14") (pinfunction "V+_14") (pintype "passive"))
      (node (ref "S_1_C4") (pin "14") (pinfunction "V+_14") (pintype "passive"))
      (node (ref "S_1_C5") (pin "14") (pinfunction "V+_14") (pintype "passive"))
      (node (ref "S_1_C6") (pin "14") (pinfunction "V+_14") (pintype "passive"))
      (node (ref "S_2_C1") (pin "14") (pinfunction "V+_14") (pintype "passive"))
      (node (ref "S_2_C2") (pin "14") (pinfunction "V+_14") (pintype "passive"))
      (node (ref "S_2_C3") (pin "14") (pinfunction "V+_14") (pintype "passive"))
      (node (ref "S_2_C4") (pin "14") (pinfunction "V+_14") (pintype "passive"))
      (node (ref "S_2_C5") (pin "14") (pinfunction "V+_14") (pintype "passive"))
      (node (ref "S_2_C6") (pin "14") (pinfunction "V+_14") (pintype "passive"))
      (node (ref "S_3_C1") (pin "14") (pinfunction "V+_14") (pintype "passive"))
      (node (ref "S_3_C2") (pin "14") (pinfunction "V+_14") (pintype "passive"))
      (node (ref "S_3_C3") (pin "14") (pinfunction "V+_14") (pintype "passive"))
      (node (ref "S_3_C4") (pin "14") (pinfunction "V+_14") (pintype "passive"))
      (node (ref "S_3_C5") (pin "14") (pinfunction "V+_14") (pintype "passive"))
      (node (ref "S_3_C6") (pin "14") (pinfunction "V+_14") (pintype "passive"))
      (node (ref "S_4_C1") (pin "14") (pinfunction "V+_14") (pintype "passive"))
      (node (ref "S_4_C2") (pin "14") (pinfunction "V+_14") (pintype "passive"))
      (node (ref "S_4_C3") (pin "14") (pinfunction "V+_14") (pintype "passive"))
      (node (ref "S_4_C4") (pin "14") (pinfunction "V+_14") (pintype "passive"))
      (node (ref "S_4_C5") (pin "14") (pinfunction "V+_14") (pintype "passive"))
      (node (ref "S_4_C6") (pin "14") (pinfunction "V+_14") (pintype "passive"))
      (node (ref "U14") (pin "16") (pinfunction "VCC_16") (pintype "passive"))
      (node (ref "U15") (pin "16") (pinfunction "VCC_16") (pintype "passive"))
      (node (ref "U3") (pin "5") (pinfunction "5_5") (pintype "passive"))
      (node (ref "U4") (pin "3") (pinfunction "VOUT_3") (pintype "passive"))
      (node (ref "U5") (pin "16") (pinfunction "VCC_16") (pintype "passive"))
      (node (ref "U6") (pin "1") (pinfunction "VBAT_1") (pintype "power_in"))
      (node (ref "U6") (pin "24") (pinfunction "VDD_1_24") (pintype "power_in"))
      (node (ref "U6") (pin "36") (pinfunction "VDD_2_36") (pintype "power_in"))
      (node (ref "U6") (pin "48") (pinfunction "VDD_3_48") (pintype "power_in"))
    )
    (net (code "287") (name "8V") (class "Default")
      (node (ref "C52") (pin "1") (pinfunction "1_1") (pintype "passive"))
      (node (ref "C53") (pin "1") (pinfunction "1_1") (pintype "passive"))
      (node (ref "D4") (pin "1") (pinfunction "A_1") (pintype "passive"))
      (node (ref "D5") (pin "1") (pinfunction "A_1") (pintype "passive"))
      (node (ref "L4") (pin "2") (pinfunction "2_2") (pintype "passive"))
      (node (ref "P23") (pin "1") (pinfunction "1_1") (pintype "passive"))
      (node (ref "R8") (pin "2") (pinfunction "2_2") (pintype "passive"))
    )
    (net (code "288") (name "12V") (class "Default")
      (node (ref "C2") (pin "1") (pinfunction "1_1") (pintype "passive"))
      (node (ref "C3") (pin "1") (pinfunction "1_1") (pintype "passive"))
      (node (ref "C4") (pin "1") (pinfunction "1_1") (pintype "passive"))
      (node (ref "C48") (pin "1") (pinfunction "1_1") (pintype "passive"))
      (node (ref "L1") (pin "1") (pinfunction "1_1") (pintype "passive"))
      (node (ref "R6") (pin "2") (pinfunction "2_2") (pintype "passive"))
      (node (ref "U2") (pin "2") (pinfunction "IN_2") (pintype "passive"))
    )
    (net (code "289") (name "GND") (class "Default")
      (node (ref "C10") (pin "2") (pinfunction "2_2") (pintype "passive"))
      (node (ref "C15") (pin "2") (pinfunction "2_2") (pintype "passive"))
      (node (ref "C16") (pin "2") (pinfunction "2_2") (pintype "passive"))
      (node (ref "C2") (pin "2") (pinfunction "2_2") (pintype "passive"))
      (node (ref "C21") (pin "2") (pinfunction "2_2") (pintype "passive"))
      (node (ref "C22") (pin "2") (pinfunction "2_2") (pintype "passive"))
      (node (ref "C23") (pin "1") (pinfunction "1_1") (pintype "passive"))
      (node (ref "C24") (pin "2") (pinfunction "2_2") (pintype "passive"))
      (node (ref "C25") (pin "2") (pinfunction "2_2") (pintype "passive"))
      (node (ref "C26") (pin "2") (pinfunction "2_2") (pintype "passive"))
      (node (ref "C27") (pin "2") (pinfunction "2_2") (pintype "passive"))
      (node (ref "C3") (pin "2") (pinfunction "2_2") (pintype "passive"))
      (node (ref "C30") (pin "2") (pinfunction "2_2") (pintype "passive"))
      (node (ref "C38") (pin "1") (pinfunction "1_1") (pintype "passive"))
      (node (ref "C39") (pin "1") (pinfunction "1_1") (pintype "passive"))
      (node (ref "C4") (pin "2") (pinfunction "2_2") (pintype "passive"))
      (node (ref "C41") (pin "2") (pinfunction "2_2") (pintype "passive"))
      (node (ref "C42") (pin "2") (pinfunction "2_2") (pintype "passive"))
      (node (ref "C43") (pin "2") (pinfunction "2_2") (pintype "passive"))
      (node (ref "C48") (pin "2") (pinfunction "2_2") (pintype "passive"))
      (node (ref "C5") (pin "2") (pinfunction "2_2") (pintype "passive"))
      (node (ref "C50") (pin "2") (pinfunction "2_2") (pintype "passive"))
      (node (ref "C52") (pin "2") (pinfunction "2_2") (pintype "passive"))
      (node (ref "C53") (pin "2") (pinfunction "2_2") (pintype "passive"))
      (node (ref "C6") (pin "2") (pinfunction "2_2") (pintype "passive"))
      (node (ref "C60") (pin "2") (pinfunction "2_2") (pintype "passive"))
      (node (ref "C7") (pin "2") (pinfunction "2_2") (pintype "passive"))
      (node (ref "C8") (pin "2") (pinfunction "2_2") (pintype "passive"))
      (node (ref "C9") (pin "2") (pinfunction "2_2") (pintype "passive"))
      (node (ref "D8") (pin "1") (pinfunction "A_1") (pintype "passive"))
      (node (ref "ISP_1_C1&2") (pin "17") (pinfunction "GND_17") (pintype "passive"))
      (node (ref "ISP_1_C1&2") (pin "6") (pinfunction "GND_6") (pintype "passive"))
      (node (ref "ISP_1_C3&4") (pin "17") (pinfunction "GND_17") (pintype "passive"))
      (node (ref "ISP_1_C3&4") (pin "6") (pinfunction "GND_6") (pintype "passive"))
      (node (ref "ISP_1_C5&6") (pin "17") (pinfunction "GND_17") (pintype "passive"))
      (node (ref "ISP_1_C5&6") (pin "6") (pinfunction "GND_6") (pintype "passive"))
      (node (ref "ISP_2_C1&2") (pin "17") (pinfunction "GND_17") (pintype "passive"))
      (node (ref "ISP_2_C1&2") (pin "6") (pinfunction "GND_6") (pintype "passive"))
      (node (ref "ISP_2_C3&4") (pin "17") (pinfunction "GND_17") (pintype "passive"))
      (node (ref "ISP_2_C3&4") (pin "6") (pinfunction "GND_6") (pintype "passive"))
      (node (ref "ISP_2_C5&6") (pin "17") (pinfunction "GND_17") (pintype "passive"))
      (node (ref "ISP_2_C5&6") (pin "6") (pinfunction "GND_6") (pintype "passive"))
      (node (ref "ISP_3_C1&2") (pin "17") (pinfunction "GND_17") (pintype "passive"))
      (node (ref "ISP_3_C1&2") (pin "6") (pinfunction "GND_6") (pintype "passive"))
      (node (ref "ISP_3_C3&4") (pin "17") (pinfunction "GND_17") (pintype "passive"))
      (node (ref "ISP_3_C3&4") (pin "6") (pinfunction "GND_6") (pintype "passive"))
      (node (ref "ISP_3_C5&6") (pin "17") (pinfunction "GND_17") (pintype "passive"))
      (node (ref "ISP_3_C5&6") (pin "6") (pinfunction "GND_6") (pintype "passive"))
      (node (ref "ISP_4_C1&2") (pin "17") (pinfunction "GND_17") (pintype "passive"))
      (node (ref "ISP_4_C1&2") (pin "6") (pinfunction "GND_6") (pintype "passive"))
      (node (ref "ISP_4_C3&4") (pin "17") (pinfunction "GND_17") (pintype "passive"))
      (node (ref "ISP_4_C3&4") (pin "6") (pinfunction "GND_6") (pintype "passive"))
      (node (ref "ISP_4_C5&6") (pin "17") (pinfunction "GND_17") (pintype "passive"))
      (node (ref "ISP_4_C5&6") (pin "6") (pinfunction "GND_6") (pintype "passive"))
      (node (ref "J-I-S") (pin "17") (pinfunction "GND_17") (pintype "passive"))
      (node (ref "J-I-S") (pin "6") (pinfunction "GND_6") (pintype "passive"))
      (node (ref "J1") (pin "5") (pinfunction "5_5") (pintype "passive"))
      (node (ref "JTAG/ISP") (pin "8") (pinfunction "GND_8") (pintype "passive"))
      (node (ref "L2") (pin "1") (pinfunction "1_1") (pintype "passive"))
      (node (ref "LD0") (pin "2") (pinfunction "K_2") (pintype "passive"))
      (node (ref "P17") (pin "2") (pinfunction "2_2") (pintype "passive"))
      (node (ref "P18") (pin "2") (pinfunction "2_2") (pintype "passive"))
      (node (ref "P1_C1") (pin "8") (pinfunction "8_8") (pintype "passive"))
      (node (ref "P1_C2") (pin "8") (pinfunction "8_8") (pintype "passive"))
      (node (ref "P1_C3") (pin "8") (pinfunction "8_8") (pintype "passive"))
      (node (ref "P1_C4") (pin "8") (pinfunction "8_8") (pintype "passive"))
      (node (ref "P1_C5") (pin "8") (pinfunction "8_8") (pintype "passive"))
      (node (ref "P1_C6") (pin "8") (pinfunction "8_8") (pintype "passive"))
      (node (ref "P23") (pin "5") (pinfunction "5_5") (pintype "passive"))
      (node (ref "P24") (pin "4") (pinfunction "4_4") (pintype "passive"))
      (node (ref "P2_C1") (pin "8") (pinfunction "8_8") (pintype "passive"))
      (node (ref "P2_C2") (pin "8") (pinfunction "8_8") (pintype "passive"))
      (node (ref "P2_C3") (pin "8") (pinfunction "8_8") (pintype "passive"))
      (node (ref "P2_C4") (pin "8") (pinfunction "8_8") (pintype "passive"))
      (node (ref "P2_C5") (pin "8") (pinfunction "8_8") (pintype "passive"))
      (node (ref "P2_C6") (pin "8") (pinfunction "8_8") (pintype "passive"))
      (node (ref "P3-C5") (pin "8") (pinfunction "8_8") (pintype "passive"))
      (node (ref "P3-C6") (pin "8") (pinfunction "8_8") (pintype "passive"))
      (node (ref "P3_C1") (pin "8") (pinfunction "8_8") (pintype "passive"))
      (node (ref "P3_C2") (pin "8") (pinfunction "8_8") (pintype "passive"))
      (node (ref "P3_C3") (pin "8") (pinfunction "8_8") (pintype "passive"))
      (node (ref "P3_C4") (pin "8") (pinfunction "8_8") (pintype "passive"))
      (node (ref "P4_C1") (pin "8") (pinfunction "8_8") (pintype "passive"))
      (node (ref "P4_C2") (pin "8") (pinfunction "8_8") (pintype "passive"))
      (node (ref "P4_C3") (pin "8") (pinfunction "8_8") (pintype "passive"))
      (node (ref "P4_C4") (pin "8") (pinfunction "8_8") (pintype "passive"))
      (node (ref "P4_C5") (pin "8") (pinfunction "8_8") (pintype "passive"))
      (node (ref "P4_C6") (pin "8") (pinfunction "8_8") (pintype "passive"))
      (node (ref "P_1_C1") (pin "2") (pinfunction "GND_2") (pintype "passive"))
      (node (ref "P_1_C2") (pin "2") (pinfunction "GND_2") (pintype "passive"))
      (node (ref "P_1_C3") (pin "2") (pinfunction "GND_2") (pintype "passive"))
      (node (ref "P_1_C4") (pin "2") (pinfunction "GND_2") (pintype "passive"))
      (node (ref "P_1_C5") (pin "2") (pinfunction "GND_2") (pintype "passive"))
      (node (ref "P_1_C6") (pin "2") (pinfunction "GND_2") (pintype "passive"))
      (node (ref "P_2_C1") (pin "2") (pinfunction "GND_2") (pintype "passive"))
      (node (ref "P_2_C2") (pin "2") (pinfunction "GND_2") (pintype "passive"))
      (node (ref "P_2_C3") (pin "2") (pinfunction "GND_2") (pintype "passive"))
      (node (ref "P_2_C4") (pin "2") (pinfunction "GND_2") (pintype "passive"))
      (node (ref "P_2_C5") (pin "2") (pinfunction "GND_2") (pintype "passive"))
      (node (ref "P_2_C6") (pin "2") (pinfunction "GND_2") (pintype "passive"))
      (node (ref "P_3_C1") (pin "2") (pinfunction "GND_2") (pintype "passive"))
      (node (ref "P_3_C2") (pin "2") (pinfunction "GND_2") (pintype "passive"))
      (node (ref "P_3_C3") (pin "2") (pinfunction "GND_2") (pintype "passive"))
      (node (ref "P_3_C4") (pin "2") (pinfunction "GND_2") (pintype "passive"))
      (node (ref "P_3_C5") (pin "2") (pinfunction "GND_2") (pintype "passive"))
      (node (ref "P_3_C6") (pin "2") (pinfunction "GND_2") (pintype "passive"))
      (node (ref "P_4_C1") (pin "2") (pinfunction "GND_2") (pintype "passive"))
      (node (ref "P_4_C2") (pin "2") (pinfunction "GND_2") (pintype "passive"))
      (node (ref "P_4_C3") (pin "2") (pinfunction "GND_2") (pintype "passive"))
      (node (ref "P_4_C4") (pin "2") (pinfunction "GND_2") (pintype "passive"))
      (node (ref "P_4_C5") (pin "2") (pinfunction "GND_2") (pintype "passive"))
      (node (ref "P_4_C6") (pin "2") (pinfunction "GND_2") (pintype "passive"))
      (node (ref "Q7") (pin "2") (pinfunction "E_2") (pintype "passive"))
      (node (ref "R10") (pin "1") (pinfunction "1_1") (pintype "passive"))
      (node (ref "R14") (pin "1") (pinfunction "1_1") (pintype "passive"))
      (node (ref "R17") (pin "1") (pinfunction "1_1") (pintype "passive"))
      (node (ref "R21") (pin "1") (pinfunction "1_1") (pintype "passive"))
      (node (ref "R29") (pin "2") (pinfunction "2_2") (pintype "passive"))
      (node (ref "R30") (pin "2") (pinfunction "2_2") (pintype "passive"))
      (node (ref "R31") (pin "2") (pinfunction "2_2") (pintype "passive"))
      (node (ref "R32") (pin "2") (pinfunction "2_2") (pintype "passive"))
      (node (ref "R33") (pin "2") (pinfunction "2_2") (pintype "passive"))
      (node (ref "R34") (pin "2") (pinfunction "2_2") (pintype "passive"))
      (node (ref "R40") (pin "2") (pinfunction "2_2") (pintype "passive"))
      (node (ref "R41") (pin "2") (pinfunction "2_2") (pintype "passive"))
      (node (ref "R45") (pin "1") (pinfunction "1_1") (pintype "passive"))
      (node (ref "R48") (pin "1") (pinfunction "1_1") (pintype "passive"))
      (node (ref "R52") (pin "2") (pinfunction "2_2") (pintype "passive"))
      (node (ref "R53") (pin "2") (pinfunction "2_2") (pintype "passive"))
      (node (ref "R54") (pin "2") (pinfunction "2_2") (pintype "passive"))
      (node (ref "R55") (pin "2") (pinfunction "2_2") (pintype "passive"))
      (node (ref "R56") (pin "2") (pinfunction "2_2") (pintype "passive"))
      (node (ref "R57") (pin "2") (pinfunction "2_2") (pintype "passive"))
      (node (ref "R60") (pin "2") (pinfunction "2_2") (pintype "passive"))
      (node (ref "R61") (pin "2") (pinfunction "2_2") (pintype "passive"))
      (node (ref "R62") (pin "2") (pinfunction "2_2") (pintype "passive"))
      (node (ref "R63") (pin "2") (pinfunction "2_2") (pintype "passive"))
      (node (ref "R64") (pin "2") (pinfunction "2_2") (pintype "passive"))
      (node (ref "R65") (pin "2") (pinfunction "2_2") (pintype "passive"))
      (node (ref "R66") (pin "2") (pinfunction "2_2") (pintype "passive"))
      (node (ref "R7") (pin "1") (pinfunction "1_1") (pintype "passive"))
      (node (ref "R71") (pin "2") (pinfunction "2_2") (pintype "passive"))
      (node (ref "R72") (pin "2") (pinfunction "2_2") (pintype "passive"))
      (node (ref "R73") (pin "2") (pinfunction "2_2") (pintype "passive"))
      (node (ref "R74") (pin "2") (pinfunction "2_2") (pintype "passive"))
      (node (ref "R75") (pin "2") (pinfunction "2_2") (pintype "passive"))
      (node (ref "R76") (pin "2") (pinfunction "2_2") (pintype "passive"))
      (node (ref "S0") (pin "3") (pinfunction "3_3") (pintype "passive"))
      (node (ref "S0") (pin "4") (pinfunction "4_4") (pintype "passive"))
      (node (ref "S_1_C1") (pin "17") (pinfunction "GND_17") (pintype "passive"))
      (node (ref "S_1_C1") (pin "6") (pinfunction "GND_6") (pintype "passive"))
      (node (ref "S_1_C2") (pin "17") (pinfunction "GND_17") (pintype "passive"))
      (node (ref "S_1_C2") (pin "6") (pinfunction "GND_6") (pintype "passive"))
      (node (ref "S_1_C3") (pin "17") (pinfunction "GND_17") (pintype "passive"))
      (node (ref "S_1_C3") (pin "6") (pinfunction "GND_6") (pintype "passive"))
      (node (ref "S_1_C4") (pin "17") (pinfunction "GND_17") (pintype "passive"))
      (node (ref "S_1_C4") (pin "6") (pinfunction "GND_6") (pintype "passive"))
      (node (ref "S_1_C5") (pin "17") (pinfunction "GND_17") (pintype "passive"))
      (node (ref "S_1_C5") (pin "6") (pinfunction "GND_6") (pintype "passive"))
      (node (ref "S_1_C6") (pin "17") (pinfunction "GND_17") (pintype "passive"))
      (node (ref "S_1_C6") (pin "6") (pinfunction "GND_6") (pintype "passive"))
      (node (ref "S_2_C1") (pin "17") (pinfunction "GND_17") (pintype "passive"))
      (node (ref "S_2_C1") (pin "6") (pinfunction "GND_6") (pintype "passive"))
      (node (ref "S_2_C2") (pin "17") (pinfunction "GND_17") (pintype "passive"))
      (node (ref "S_2_C2") (pin "6") (pinfunction "GND_6") (pintype "passive"))
      (node (ref "S_2_C3") (pin "17") (pinfunction "GND_17") (pintype "passive"))
      (node (ref "S_2_C3") (pin "6") (pinfunction "GND_6") (pintype "passive"))
      (node (ref "S_2_C4") (pin "17") (pinfunction "GND_17") (pintype "passive"))
      (node (ref "S_2_C4") (pin "6") (pinfunction "GND_6") (pintype "passive"))
      (node (ref "S_2_C5") (pin "17") (pinfunction "GND_17") (pintype "passive"))
      (node (ref "S_2_C5") (pin "6") (pinfunction "GND_6") (pintype "passive"))
      (node (ref "S_2_C6") (pin "17") (pinfunction "GND_17") (pintype "passive"))
      (node (ref "S_2_C6") (pin "6") (pinfunction "GND_6") (pintype "passive"))
      (node (ref "S_3_C1") (pin "17") (pinfunction "GND_17") (pintype "passive"))
      (node (ref "S_3_C1") (pin "6") (pinfunction "GND_6") (pintype "passive"))
      (node (ref "S_3_C2") (pin "17") (pinfunction "GND_17") (pintype "passive"))
      (node (ref "S_3_C2") (pin "6") (pinfunction "GND_6") (pintype "passive"))
      (node (ref "S_3_C3") (pin "17") (pinfunction "GND_17") (pintype "passive"))
      (node (ref "S_3_C3") (pin "6") (pinfunction "GND_6") (pintype "passive"))
      (node (ref "S_3_C4") (pin "17") (pinfunction "GND_17") (pintype "passive"))
      (node (ref "S_3_C4") (pin "6") (pinfunction "GND_6") (pintype "passive"))
      (node (ref "S_3_C5") (pin "17") (pinfunction "GND_17") (pintype "passive"))
      (node (ref "S_3_C5") (pin "6") (pinfunction "GND_6") (pintype "passive"))
      (node (ref "S_3_C6") (pin "17") (pinfunction "GND_17") (pintype "passive"))
      (node (ref "S_3_C6") (pin "6") (pinfunction "GND_6") (pintype "passive"))
      (node (ref "S_4_C1") (pin "17") (pinfunction "GND_17") (pintype "passive"))
      (node (ref "S_4_C1") (pin "6") (pinfunction "GND_6") (pintype "passive"))
      (node (ref "S_4_C2") (pin "17") (pinfunction "GND_17") (pintype "passive"))
      (node (ref "S_4_C2") (pin "6") (pinfunction "GND_6") (pintype "passive"))
      (node (ref "S_4_C3") (pin "17") (pinfunction "GND_17") (pintype "passive"))
      (node (ref "S_4_C3") (pin "6") (pinfunction "GND_6") (pintype "passive"))
      (node (ref "S_4_C4") (pin "17") (pinfunction "GND_17") (pintype "passive"))
      (node (ref "S_4_C4") (pin "6") (pinfunction "GND_6") (pintype "passive"))
      (node (ref "S_4_C5") (pin "17") (pinfunction "GND_17") (pintype "passive"))
      (node (ref "S_4_C5") (pin "6") (pinfunction "GND_6") (pintype "passive"))
      (node (ref "S_4_C6") (pin "17") (pinfunction "GND_17") (pintype "passive"))
      (node (ref "S_4_C6") (pin "6") (pinfunction "GND_6") (pintype "passive"))
      (node (ref "U14") (pin "13") (pinfunction "/OE_13") (pintype "passive"))
      (node (ref "U14") (pin "8") (pinfunction "GND_8") (pintype "passive"))
      (node (ref "U15") (pin "13") (pinfunction "/OE_13") (pintype "passive"))
      (node (ref "U15") (pin "8") (pinfunction "GND_8") (pintype "passive"))
      (node (ref "U16") (pin "1") (pinfunction "GND_1") (pintype "passive"))
      (node (ref "U2") (pin "4") (pinfunction "GND_4") (pintype "passive"))
      (node (ref "U2") (pin "9") (pinfunction "GND_9") (pintype "passive"))
      (node (ref "U3") (pin "2") (pinfunction "GND_2") (pintype "passive"))
      (node (ref "U4") (pin "1") (pinfunction "GND_1") (pintype "passive"))
      (node (ref "U5") (pin "13") (pinfunction "/OE_13") (pintype "passive"))
      (node (ref "U5") (pin "8") (pinfunction "GND_8") (pintype "passive"))
      (node (ref "U6") (pin "23") (pinfunction "VSS_1_23") (pintype "power_in"))
      (node (ref "U6") (pin "35") (pinfunction "VSS_2_35") (pintype "power_in"))
      (node (ref "U6") (pin "47") (pinfunction "VSS_3_47") (pintype "power_in"))
      (node (ref "U6") (pin "8") (pinfunction "VSSA_8") (pintype "power_in"))
    )
    (net (code "290") (name "JTAG_VDD") (class "Default")
      (node (ref "C15") (pin "1") (pinfunction "1_1") (pintype "passive"))
      (node (ref "JTAG/ISP") (pin "1") (pinfunction "JTAG_VDD_1") (pintype "passive"))
      (node (ref "P_1_C1") (pin "5") (pinfunction "VIN_5") (pintype "passive"))
      (node (ref "P_1_C2") (pin "5") (pinfunction "VIN_5") (pintype "passive"))
      (node (ref "P_1_C3") (pin "5") (pinfunction "VIN_5") (pintype "passive"))
      (node (ref "P_1_C4") (pin "5") (pinfunction "VIN_5") (pintype "passive"))
      (node (ref "P_1_C5") (pin "5") (pinfunction "VIN_5") (pintype "passive"))
      (node (ref "P_1_C6") (pin "5") (pinfunction "VIN_5") (pintype "passive"))
      (node (ref "P_2_C1") (pin "5") (pinfunction "VIN_5") (pintype "passive"))
      (node (ref "P_2_C2") (pin "5") (pinfunction "VIN_5") (pintype "passive"))
      (node (ref "P_2_C3") (pin "5") (pinfunction "VIN_5") (pintype "passive"))
      (node (ref "P_2_C4") (pin "5") (pinfunction "VIN_5") (pintype "passive"))
      (node (ref "P_2_C5") (pin "5") (pinfunction "VIN_5") (pintype "passive"))
      (node (ref "P_2_C6") (pin "5") (pinfunction "VIN_5") (pintype "passive"))
      (node (ref "P_3_C1") (pin "5") (pinfunction "VIN_5") (pintype "passive"))
      (node (ref "P_3_C2") (pin "5") (pinfunction "VIN_5") (pintype "passive"))
      (node (ref "P_3_C3") (pin "5") (pinfunction "VIN_5") (pintype "passive"))
      (node (ref "P_3_C4") (pin "5") (pinfunction "VIN_5") (pintype "passive"))
      (node (ref "P_3_C5") (pin "5") (pinfunction "VIN_5") (pintype "passive"))
      (node (ref "P_3_C6") (pin "5") (pinfunction "VIN_5") (pintype "passive"))
      (node (ref "P_4_C1") (pin "5") (pinfunction "VIN_5") (pintype "passive"))
      (node (ref "P_4_C2") (pin "5") (pinfunction "VIN_5") (pintype "passive"))
      (node (ref "P_4_C3") (pin "5") (pinfunction "VIN_5") (pintype "passive"))
      (node (ref "P_4_C4") (pin "5") (pinfunction "VIN_5") (pintype "passive"))
      (node (ref "P_4_C5") (pin "5") (pinfunction "VIN_5") (pintype "passive"))
      (node (ref "P_4_C6") (pin "5") (pinfunction "VIN_5") (pintype "passive"))
    )
    (net (code "291") (name "Net-(C51-Pad2)") (class "Default")
      (node (ref "C51") (pin "2") (pinfunction "2_2") (pintype "passive"))
      (node (ref "R10") (pin "2") (pinfunction "2_2") (pintype "passive"))
    )
    (net (code "292") (name "Net-(D1-A)") (class "Default")
      (node (ref "D1") (pin "1") (pinfunction "A_1") (pintype "passive"))
      (node (ref "P0") (pin "1") (pinfunction "1_1") (pintype "passive"))
    )
    (net (code "293") (name "Net-(D1-K)") (class "Default")
      (node (ref "D1") (pin "2") (pinfunction "K_2") (pintype "passive"))
      (node (ref "F1") (pin "1") (pinfunction "1_1") (pintype "passive"))
    )
    (net (code "294") (name "Net-(D4-K)") (class "Default")
      (node (ref "C21") (pin "1") (pinfunction "1_1") (pintype "passive"))
      (node (ref "D4") (pin "2") (pinfunction "K_2") (pintype "passive"))
      (node (ref "U16") (pin "2") (pinfunction "VIN_2") (pintype "passive"))
    )
    (net (code "295") (name "Net-(D5-K)") (class "Default")
      (node (ref "C5") (pin "1") (pinfunction "1_1") (pintype "passive"))
      (node (ref "D5") (pin "2") (pinfunction "K_2") (pintype "passive"))
      (node (ref "U4") (pin "2") (pinfunction "VIN_2") (pintype "passive"))
    )
    (net (code "296") (name "Net-(D8-K)") (class "Default")
      (node (ref "C49") (pin "1") (pinfunction "1_1") (pintype "passive"))
      (node (ref "D8") (pin "2") (pinfunction "K_2") (pintype "passive"))
      (node (ref "L4") (pin "1") (pinfunction "1_1") (pintype "passive"))
      (node (ref "U2") (pin "3") (pinfunction "SW_3") (pintype "passive"))
    )
    (net (code "297") (name "Net-(J1-Pad3)") (class "Default")
      (node (ref "J1") (pin "3") (pinfunction "3_3") (pintype "passive"))
      (node (ref "R2") (pin "1") (pinfunction "1_1") (pintype "passive"))
    )
    (net (code "298") (name "Net-(J1-Pad7)") (class "Default")
      (node (ref "J1") (pin "7") (pinfunction "7_7") (pintype "passive"))
      (node (ref "R1") (pin "1") (pinfunction "1_1") (pintype "passive"))
    )
    (net (code "299") (name "Net-(J1-Pad8)") (class "Default")
      (node (ref "J1") (pin "8") (pinfunction "8_8") (pintype "passive"))
      (node (ref "R5") (pin "1") (pinfunction "1_1") (pintype "passive"))
    )
    (net (code "300") (name "Net-(J1-Pad9)") (class "Default")
      (node (ref "J1") (pin "9") (pinfunction "9_9") (pintype "passive"))
      (node (ref "R9") (pin "1") (pinfunction "1_1") (pintype "passive"))
    )
    (net (code "301") (name "Net-(LD0-A)") (class "Default")
      (node (ref "LD0") (pin "1") (pinfunction "A_1") (pintype "passive"))
      (node (ref "R3") (pin "2") (pinfunction "2_2") (pintype "passive"))
    )
    (net (code "302") (name "Net-(P23-Pad2)") (class "Default")
      (node (ref "P23") (pin "2") (pinfunction "2_2") (pintype "passive"))
      (node (ref "R43") (pin "1") (pinfunction "1_1") (pintype "passive"))
    )
    (net (code "303") (name "Net-(P_1_C1-ISET)") (class "Default")
      (node (ref "P_1_C1") (pin "3") (pinfunction "ISET_3") (pintype "passive"))
      (node (ref "R29") (pin "1") (pinfunction "1_1") (pintype "passive"))
    )
    (net (code "304") (name "Net-(P_1_C2-ISET)") (class "Default")
      (node (ref "P_1_C2") (pin "3") (pinfunction "ISET_3") (pintype "passive"))
      (node (ref "R30") (pin "1") (pinfunction "1_1") (pintype "passive"))
    )
    (net (code "305") (name "Net-(P_1_C3-ISET)") (class "Default")
      (node (ref "P_1_C3") (pin "3") (pinfunction "ISET_3") (pintype "passive"))
      (node (ref "R31") (pin "1") (pinfunction "1_1") (pintype "passive"))
    )
    (net (code "306") (name "Net-(P_1_C4-ISET)") (class "Default")
      (node (ref "P_1_C4") (pin "3") (pinfunction "ISET_3") (pintype "passive"))
      (node (ref "R32") (pin "1") (pinfunction "1_1") (pintype "passive"))
    )
    (net (code "307") (name "Net-(P_1_C5-ISET)") (class "Default")
      (node (ref "P_1_C5") (pin "3") (pinfunction "ISET_3") (pintype "passive"))
      (node (ref "R33") (pin "1") (pinfunction "1_1") (pintype "passive"))
    )
    (net (code "308") (name "Net-(P_1_C6-ISET)") (class "Default")
      (node (ref "P_1_C6") (pin "3") (pinfunction "ISET_3") (pintype "passive"))
      (node (ref "R34") (pin "1") (pinfunction "1_1") (pintype "passive"))
    )
    (net (code "309") (name "Net-(P_2_C1-ISET)") (class "Default")
      (node (ref "P_2_C1") (pin "3") (pinfunction "ISET_3") (pintype "passive"))
      (node (ref "R57") (pin "1") (pinfunction "1_1") (pintype "passive"))
    )
    (net (code "310") (name "Net-(P_2_C2-ISET)") (class "Default")
      (node (ref "P_2_C2") (pin "3") (pinfunction "ISET_3") (pintype "passive"))
      (node (ref "R52") (pin "1") (pinfunction "1_1") (pintype "passive"))
    )
    (net (code "311") (name "Net-(P_2_C3-ISET)") (class "Default")
      (node (ref "P_2_C3") (pin "3") (pinfunction "ISET_3") (pintype "passive"))
      (node (ref "R53") (pin "1") (pinfunction "1_1") (pintype "passive"))
    )
    (net (code "312") (name "Net-(P_2_C4-ISET)") (class "Default")
      (node (ref "P_2_C4") (pin "3") (pinfunction "ISET_3") (pintype "passive"))
      (node (ref "R54") (pin "1") (pinfunction "1_1") (pintype "passive"))
    )
    (net (code "313") (name "Net-(P_2_C5-ISET)") (class "Default")
      (node (ref "P_2_C5") (pin "3") (pinfunction "ISET_3") (pintype "passive"))
      (node (ref "R55") (pin "1") (pinfunction "1_1") (pintype "passive"))
    )
    (net (code "314") (name "Net-(P_2_C6-ISET)") (class "Default")
      (node (ref "P_2_C6") (pin "3") (pinfunction "ISET_3") (pintype "passive"))
      (node (ref "R56") (pin "1") (pinfunction "1_1") (pintype "passive"))
    )
    (net (code "315") (name "Net-(P_3_C1-ISET)") (class "Default")
      (node (ref "P_3_C1") (pin "3") (pinfunction "ISET_3") (pintype "passive"))
      (node (ref "R61") (pin "1") (pinfunction "1_1") (pintype "passive"))
    )
    (net (code "316") (name "Net-(P_3_C2-ISET)") (class "Default")
      (node (ref "P_3_C2") (pin "3") (pinfunction "ISET_3") (pintype "passive"))
      (node (ref "R62") (pin "1") (pinfunction "1_1") (pintype "passive"))
    )
    (net (code "317") (name "Net-(P_3_C3-ISET)") (class "Default")
      (node (ref "P_3_C3") (pin "3") (pinfunction "ISET_3") (pintype "passive"))
      (node (ref "R63") (pin "1") (pinfunction "1_1") (pintype "passive"))
    )
    (net (code "318") (name "Net-(P_3_C4-ISET)") (class "Default")
      (node (ref "P_3_C4") (pin "3") (pinfunction "ISET_3") (pintype "passive"))
      (node (ref "R64") (pin "1") (pinfunction "1_1") (pintype "passive"))
    )
    (net (code "319") (name "Net-(P_3_C5-ISET)") (class "Default")
      (node (ref "P_3_C5") (pin "3") (pinfunction "ISET_3") (pintype "passive"))
      (node (ref "R65") (pin "1") (pinfunction "1_1") (pintype "passive"))
    )
    (net (code "320") (name "Net-(P_3_C6-ISET)") (class "Default")
      (node (ref "P_3_C6") (pin "3") (pinfunction "ISET_3") (pintype "passive"))
      (node (ref "R66") (pin "1") (pinfunction "1_1") (pintype "passive"))
    )
    (net (code "321") (name "Net-(P_4_C1-ISET)") (class "Default")
      (node (ref "P_4_C1") (pin "3") (pinfunction "ISET_3") (pintype "passive"))
      (node (ref "R71") (pin "1") (pinfunction "1_1") (pintype "passive"))
    )
    (net (code "322") (name "Net-(P_4_C2-ISET)") (class "Default")
      (node (ref "P_4_C2") (pin "3") (pinfunction "ISET_3") (pintype "passive"))
      (node (ref "R72") (pin "1") (pinfunction "1_1") (pintype "passive"))
    )
    (net (code "323") (name "Net-(P_4_C3-ISET)") (class "Default")
      (node (ref "P_4_C3") (pin "3") (pinfunction "ISET_3") (pintype "passive"))
      (node (ref "R73") (pin "1") (pinfunction "1_1") (pintype "passive"))
    )
    (net (code "324") (name "Net-(P_4_C4-ISET)") (class "Default")
      (node (ref "P_4_C4") (pin "3") (pinfunction "ISET_3") (pintype "passive"))
      (node (ref "R74") (pin "1") (pinfunction "1_1") (pintype "passive"))
    )
    (net (code "325") (name "Net-(P_4_C5-ISET)") (class "Default")
      (node (ref "P_4_C5") (pin "3") (pinfunction "ISET_3") (pintype "passive"))
      (node (ref "R75") (pin "1") (pinfunction "1_1") (pintype "passive"))
    )
    (net (code "326") (name "Net-(P_4_C6-ISET)") (class "Default")
      (node (ref "P_4_C6") (pin "3") (pinfunction "ISET_3") (pintype "passive"))
      (node (ref "R76") (pin "1") (pinfunction "1_1") (pintype "passive"))
    )
    (net (code "327") (name "Net-(Q7-B)") (class "Default")
      (node (ref "Q7") (pin "1") (pinfunction "B_1") (pintype "passive"))
      (node (ref "R20") (pin "2") (pinfunction "2_2") (pintype "passive"))
      (node (ref "R21") (pin "2") (pinfunction "2_2") (pintype "passive"))
    )
    (net (code "328") (name "Net-(Q7-C)") (class "Default")
      (node (ref "LS1") (pin "2") (pinfunction "2_2") (pintype "passive"))
      (node (ref "Q7") (pin "3") (pinfunction "C_3") (pintype "passive"))
    )
    (net (code "329") (name "Net-(R36-Pad2)") (class "Default")
      (node (ref "R36") (pin "2") (pinfunction "2_2") (pintype "passive"))
      (node (ref "S1") (pin "3") (pinfunction "3_3") (pintype "passive"))
      (node (ref "S1") (pin "4") (pinfunction "4_4") (pintype "passive"))
    )
    (net (code "330") (name "Net-(R37-Pad2)") (class "Default")
      (node (ref "R37") (pin "2") (pinfunction "2_2") (pintype "passive"))
      (node (ref "S2") (pin "3") (pinfunction "3_3") (pintype "passive"))
      (node (ref "S2") (pin "4") (pinfunction "4_4") (pintype "passive"))
    )
    (net (code "331") (name "Net-(R59-Pad1)") (class "Default")
      (node (ref "R59") (pin "1") (pinfunction "1_1") (pintype "passive"))
      (node (ref "SW1") (pin "2") (pinfunction "2_2") (pintype "passive"))
    )
    (net (code "332") (name "Net-(U2-BS)") (class "Default")
      (node (ref "C49") (pin "2") (pinfunction "2_2") (pintype "passive"))
      (node (ref "U2") (pin "1") (pinfunction "BS_1") (pintype "passive"))
    )
    (net (code "333") (name "Net-(U2-COMP)") (class "Default")
      (node (ref "C51") (pin "1") (pinfunction "1_1") (pintype "passive"))
      (node (ref "U2") (pin "6") (pinfunction "COMP_6") (pintype "passive"))
    )
    (net (code "334") (name "Net-(U2-EN)") (class "Default")
      (node (ref "R6") (pin "1") (pinfunction "1_1") (pintype "passive"))
      (node (ref "U2") (pin "7") (pinfunction "EN_7") (pintype "passive"))
    )
    (net (code "335") (name "Net-(U2-FB)") (class "Default")
      (node (ref "R7") (pin "2") (pinfunction "2_2") (pintype "passive"))
      (node (ref "R8") (pin "1") (pinfunction "1_1") (pintype "passive"))
      (node (ref "U2") (pin "5") (pinfunction "FB_5") (pintype "passive"))
    )
    (net (code "336") (name "Net-(U2-SS)") (class "Default")
      (node (ref "C50") (pin "1") (pinfunction "1_1") (pintype "passive"))
      (node (ref "U2") (pin "8") (pinfunction "SS_8") (pintype "passive"))
    )
    (net (code "337") (name "Net-(U5-{slash}SRCLR)") (class "Default")
      (node (ref "R68") (pin "2") (pinfunction "2_2") (pintype "passive"))
      (node (ref "U5") (pin "10") (pinfunction "/SRCLR_10") (pintype "passive"))
    )
    (net (code "338") (name "Net-(U6-VDDA)") (class "Default")
      (node (ref "C27") (pin "1") (pinfunction "1_1") (pintype "passive"))
      (node (ref "R15") (pin "1") (pinfunction "1_1") (pintype "passive"))
      (node (ref "U6") (pin "9") (pinfunction "VDDA_9") (pintype "power_in"))
    )
    (net (code "339") (name "Net-(U14-{slash}SRCLR)") (class "Default")
      (node (ref "R69") (pin "2") (pinfunction "2_2") (pintype "passive"))
      (node (ref "U14") (pin "10") (pinfunction "/SRCLR_10") (pintype "passive"))
    )
    (net (code "340") (name "Net-(U15-{slash}SRCLR)") (class "Default")
      (node (ref "R67") (pin "2") (pinfunction "2_2") (pintype "passive"))
      (node (ref "U15") (pin "10") (pinfunction "/SRCLR_10") (pintype "passive"))
    )
    (net (code "341") (name "unconnected-(J-I-S-COM3-Pad8)") (class "Default")
      (node (ref "J-I-S") (pin "8") (pinfunction "COM3_8") (pintype "passive+no_connect"))
    )
    (net (code "342") (name "unconnected-(J-I-S-COM4-Pad12)") (class "Default")
      (node (ref "J-I-S") (pin "12") (pinfunction "COM4_12") (pintype "passive+no_connect"))
    )
    (net (code "343") (name "unconnected-(J-I-S-IN3-4-Pad10)") (class "Default")
      (node (ref "J-I-S") (pin "10") (pinfunction "IN3-4_10") (pintype "passive+no_connect"))
    )
    (net (code "344") (name "unconnected-(J-I-S-NC3-Pad9)") (class "Default")
      (node (ref "J-I-S") (pin "9") (pinfunction "NC3_9") (pintype "passive+no_connect"))
    )
    (net (code "345") (name "unconnected-(J-I-S-NC4-Pad13)") (class "Default")
      (node (ref "J-I-S") (pin "13") (pinfunction "NC4_13") (pintype "passive+no_connect"))
    )
    (net (code "346") (name "unconnected-(J-I-S-NO3-Pad7)") (class "Default")
      (node (ref "J-I-S") (pin "7") (pinfunction "NO3_7") (pintype "passive+no_connect"))
    )
    (net (code "347") (name "unconnected-(J-I-S-NO4-Pad11)") (class "Default")
      (node (ref "J-I-S") (pin "11") (pinfunction "NO4_11") (pintype "passive+no_connect"))
    )
    (net (code "348") (name "unconnected-(J1-MH1-Pad10)") (class "Default")
      (node (ref "J1") (pin "10") (pinfunction "MH1_10") (pintype "passive"))
    )
    (net (code "349") (name "unconnected-(J1-MH2-Pad11)") (class "Default")
      (node (ref "J1") (pin "11") (pinfunction "MH2_11") (pintype "passive"))
    )
    (net (code "350") (name "unconnected-(J1-Pad2)") (class "Default")
      (node (ref "J1") (pin "2") (pinfunction "2_2") (pintype "passive"))
    )
    (net (code "351") (name "unconnected-(J1-Pad4)") (class "Default")
      (node (ref "J1") (pin "4") (pinfunction "4_4") (pintype "passive"))
    )
    (net (code "352") (name "unconnected-(J1-Pad6)") (class "Default")
      (node (ref "J1") (pin "6") (pinfunction "6_6") (pintype "passive"))
    )
    (net (code "353") (name "unconnected-(S_1_C1-NC1-Pad1)") (class "Default")
      (node (ref "S_1_C1") (pin "1") (pinfunction "NC1_1") (pintype "passive+no_connect"))
    )
    (net (code "354") (name "unconnected-(S_1_C1-NC2-Pad5)") (class "Default")
      (node (ref "S_1_C1") (pin "5") (pinfunction "NC2_5") (pintype "passive+no_connect"))
    )
    (net (code "355") (name "unconnected-(S_1_C1-NC3-Pad9)") (class "Default")
      (node (ref "S_1_C1") (pin "9") (pinfunction "NC3_9") (pintype "passive+no_connect"))
    )
    (net (code "356") (name "unconnected-(S_1_C1-NC4-Pad13)") (class "Default")
      (node (ref "S_1_C1") (pin "13") (pinfunction "NC4_13") (pintype "passive+no_connect"))
    )
    (net (code "357") (name "unconnected-(S_1_C2-NC1-Pad1)") (class "Default")
      (node (ref "S_1_C2") (pin "1") (pinfunction "NC1_1") (pintype "passive+no_connect"))
    )
    (net (code "358") (name "unconnected-(S_1_C2-NC2-Pad5)") (class "Default")
      (node (ref "S_1_C2") (pin "5") (pinfunction "NC2_5") (pintype "passive+no_connect"))
    )
    (net (code "359") (name "unconnected-(S_1_C2-NC3-Pad9)") (class "Default")
      (node (ref "S_1_C2") (pin "9") (pinfunction "NC3_9") (pintype "passive+no_connect"))
    )
    (net (code "360") (name "unconnected-(S_1_C2-NC4-Pad13)") (class "Default")
      (node (ref "S_1_C2") (pin "13") (pinfunction "NC4_13") (pintype "passive+no_connect"))
    )
    (net (code "361") (name "unconnected-(S_1_C3-NC1-Pad1)") (class "Default")
      (node (ref "S_1_C3") (pin "1") (pinfunction "NC1_1") (pintype "passive+no_connect"))
    )
    (net (code "362") (name "unconnected-(S_1_C3-NC2-Pad5)") (class "Default")
      (node (ref "S_1_C3") (pin "5") (pinfunction "NC2_5") (pintype "passive+no_connect"))
    )
    (net (code "363") (name "unconnected-(S_1_C3-NC3-Pad9)") (class "Default")
      (node (ref "S_1_C3") (pin "9") (pinfunction "NC3_9") (pintype "passive+no_connect"))
    )
    (net (code "364") (name "unconnected-(S_1_C3-NC4-Pad13)") (class "Default")
      (node (ref "S_1_C3") (pin "13") (pinfunction "NC4_13") (pintype "passive+no_connect"))
    )
    (net (code "365") (name "unconnected-(S_1_C4-NC1-Pad1)") (class "Default")
      (node (ref "S_1_C4") (pin "1") (pinfunction "NC1_1") (pintype "passive+no_connect"))
    )
    (net (code "366") (name "unconnected-(S_1_C4-NC2-Pad5)") (class "Default")
      (node (ref "S_1_C4") (pin "5") (pinfunction "NC2_5") (pintype "passive+no_connect"))
    )
    (net (code "367") (name "unconnected-(S_1_C4-NC3-Pad9)") (class "Default")
      (node (ref "S_1_C4") (pin "9") (pinfunction "NC3_9") (pintype "passive+no_connect"))
    )
    (net (code "368") (name "unconnected-(S_1_C4-NC4-Pad13)") (class "Default")
      (node (ref "S_1_C4") (pin "13") (pinfunction "NC4_13") (pintype "passive+no_connect"))
    )
    (net (code "369") (name "unconnected-(S_1_C5-NC1-Pad1)") (class "Default")
      (node (ref "S_1_C5") (pin "1") (pinfunction "NC1_1") (pintype "passive+no_connect"))
    )
    (net (code "370") (name "unconnected-(S_1_C5-NC2-Pad5)") (class "Default")
      (node (ref "S_1_C5") (pin "5") (pinfunction "NC2_5") (pintype "passive+no_connect"))
    )
    (net (code "371") (name "unconnected-(S_1_C5-NC3-Pad9)") (class "Default")
      (node (ref "S_1_C5") (pin "9") (pinfunction "NC3_9") (pintype "passive+no_connect"))
    )
    (net (code "372") (name "unconnected-(S_1_C5-NC4-Pad13)") (class "Default")
      (node (ref "S_1_C5") (pin "13") (pinfunction "NC4_13") (pintype "passive+no_connect"))
    )
    (net (code "373") (name "unconnected-(S_1_C6-NC1-Pad1)") (class "Default")
      (node (ref "S_1_C6") (pin "1") (pinfunction "NC1_1") (pintype "passive+no_connect"))
    )
    (net (code "374") (name "unconnected-(S_1_C6-NC2-Pad5)") (class "Default")
      (node (ref "S_1_C6") (pin "5") (pinfunction "NC2_5") (pintype "passive+no_connect"))
    )
    (net (code "375") (name "unconnected-(S_1_C6-NC3-Pad9)") (class "Default")
      (node (ref "S_1_C6") (pin "9") (pinfunction "NC3_9") (pintype "passive+no_connect"))
    )
    (net (code "376") (name "unconnected-(S_1_C6-NC4-Pad13)") (class "Default")
      (node (ref "S_1_C6") (pin "13") (pinfunction "NC4_13") (pintype "passive+no_connect"))
    )
    (net (code "377") (name "unconnected-(S_2_C1-NC1-Pad1)") (class "Default")
      (node (ref "S_2_C1") (pin "1") (pinfunction "NC1_1") (pintype "passive+no_connect"))
    )
    (net (code "378") (name "unconnected-(S_2_C1-NC2-Pad5)") (class "Default")
      (node (ref "S_2_C1") (pin "5") (pinfunction "NC2_5") (pintype "passive+no_connect"))
    )
    (net (code "379") (name "unconnected-(S_2_C1-NC3-Pad9)") (class "Default")
      (node (ref "S_2_C1") (pin "9") (pinfunction "NC3_9") (pintype "passive+no_connect"))
    )
    (net (code "380") (name "unconnected-(S_2_C1-NC4-Pad13)") (class "Default")
      (node (ref "S_2_C1") (pin "13") (pinfunction "NC4_13") (pintype "passive+no_connect"))
    )
    (net (code "381") (name "unconnected-(S_2_C2-NC1-Pad1)") (class "Default")
      (node (ref "S_2_C2") (pin "1") (pinfunction "NC1_1") (pintype "passive+no_connect"))
    )
    (net (code "382") (name "unconnected-(S_2_C2-NC2-Pad5)") (class "Default")
      (node (ref "S_2_C2") (pin "5") (pinfunction "NC2_5") (pintype "passive+no_connect"))
    )
    (net (code "383") (name "unconnected-(S_2_C2-NC3-Pad9)") (class "Default")
      (node (ref "S_2_C2") (pin "9") (pinfunction "NC3_9") (pintype "passive+no_connect"))
    )
    (net (code "384") (name "unconnected-(S_2_C2-NC4-Pad13)") (class "Default")
      (node (ref "S_2_C2") (pin "13") (pinfunction "NC4_13") (pintype "passive+no_connect"))
    )
    (net (code "385") (name "unconnected-(S_2_C3-NC1-Pad1)") (class "Default")
      (node (ref "S_2_C3") (pin "1") (pinfunction "NC1_1") (pintype "passive+no_connect"))
    )
    (net (code "386") (name "unconnected-(S_2_C3-NC2-Pad5)") (class "Default")
      (node (ref "S_2_C3") (pin "5") (pinfunction "NC2_5") (pintype "passive+no_connect"))
    )
    (net (code "387") (name "unconnected-(S_2_C3-NC3-Pad9)") (class "Default")
      (node (ref "S_2_C3") (pin "9") (pinfunction "NC3_9") (pintype "passive+no_connect"))
    )
    (net (code "388") (name "unconnected-(S_2_C3-NC4-Pad13)") (class "Default")
      (node (ref "S_2_C3") (pin "13") (pinfunction "NC4_13") (pintype "passive+no_connect"))
    )
    (net (code "389") (name "unconnected-(S_2_C4-NC1-Pad1)") (class "Default")
      (node (ref "S_2_C4") (pin "1") (pinfunction "NC1_1") (pintype "passive+no_connect"))
    )
    (net (code "390") (name "unconnected-(S_2_C4-NC2-Pad5)") (class "Default")
      (node (ref "S_2_C4") (pin "5") (pinfunction "NC2_5") (pintype "passive+no_connect"))
    )
    (net (code "391") (name "unconnected-(S_2_C4-NC3-Pad9)") (class "Default")
      (node (ref "S_2_C4") (pin "9") (pinfunction "NC3_9") (pintype "passive+no_connect"))
    )
    (net (code "392") (name "unconnected-(S_2_C4-NC4-Pad13)") (class "Default")
      (node (ref "S_2_C4") (pin "13") (pinfunction "NC4_13") (pintype "passive+no_connect"))
    )
    (net (code "393") (name "unconnected-(S_2_C5-NC1-Pad1)") (class "Default")
      (node (ref "S_2_C5") (pin "1") (pinfunction "NC1_1") (pintype "passive+no_connect"))
    )
    (net (code "394") (name "unconnected-(S_2_C5-NC2-Pad5)") (class "Default")
      (node (ref "S_2_C5") (pin "5") (pinfunction "NC2_5") (pintype "passive+no_connect"))
    )
    (net (code "395") (name "unconnected-(S_2_C5-NC3-Pad9)") (class "Default")
      (node (ref "S_2_C5") (pin "9") (pinfunction "NC3_9") (pintype "passive+no_connect"))
    )
    (net (code "396") (name "unconnected-(S_2_C5-NC4-Pad13)") (class "Default")
      (node (ref "S_2_C5") (pin "13") (pinfunction "NC4_13") (pintype "passive+no_connect"))
    )
    (net (code "397") (name "unconnected-(S_2_C6-NC1-Pad1)") (class "Default")
      (node (ref "S_2_C6") (pin "1") (pinfunction "NC1_1") (pintype "passive+no_connect"))
    )
    (net (code "398") (name "unconnected-(S_2_C6-NC2-Pad5)") (class "Default")
      (node (ref "S_2_C6") (pin "5") (pinfunction "NC2_5") (pintype "passive+no_connect"))
    )
    (net (code "399") (name "unconnected-(S_2_C6-NC3-Pad9)") (class "Default")
      (node (ref "S_2_C6") (pin "9") (pinfunction "NC3_9") (pintype "passive+no_connect"))
    )
    (net (code "400") (name "unconnected-(S_2_C6-NC4-Pad13)") (class "Default")
      (node (ref "S_2_C6") (pin "13") (pinfunction "NC4_13") (pintype "passive+no_connect"))
    )
    (net (code "401") (name "unconnected-(S_3_C1-NC1-Pad1)") (class "Default")
      (node (ref "S_3_C1") (pin "1") (pinfunction "NC1_1") (pintype "passive+no_connect"))
    )
    (net (code "402") (name "unconnected-(S_3_C1-NC2-Pad5)") (class "Default")
      (node (ref "S_3_C1") (pin "5") (pinfunction "NC2_5") (pintype "passive+no_connect"))
    )
    (net (code "403") (name "unconnected-(S_3_C1-NC3-Pad9)") (class "Default")
      (node (ref "S_3_C1") (pin "9") (pinfunction "NC3_9") (pintype "passive+no_connect"))
    )
    (net (code "404") (name "unconnected-(S_3_C1-NC4-Pad13)") (class "Default")
      (node (ref "S_3_C1") (pin "13") (pinfunction "NC4_13") (pintype "passive+no_connect"))
    )
    (net (code "405") (name "unconnected-(S_3_C2-NC1-Pad1)") (class "Default")
      (node (ref "S_3_C2") (pin "1") (pinfunction "NC1_1") (pintype "passive+no_connect"))
    )
    (net (code "406") (name "unconnected-(S_3_C2-NC2-Pad5)") (class "Default")
      (node (ref "S_3_C2") (pin "5") (pinfunction "NC2_5") (pintype "passive+no_connect"))
    )
    (net (code "407") (name "unconnected-(S_3_C2-NC3-Pad9)") (class "Default")
      (node (ref "S_3_C2") (pin "9") (pinfunction "NC3_9") (pintype "passive+no_connect"))
    )
    (net (code "408") (name "unconnected-(S_3_C2-NC4-Pad13)") (class "Default")
      (node (ref "S_3_C2") (pin "13") (pinfunction "NC4_13") (pintype "passive+no_connect"))
    )
    (net (code "409") (name "unconnected-(S_3_C3-NC1-Pad1)") (class "Default")
      (node (ref "S_3_C3") (pin "1") (pinfunction "NC1_1") (pintype "passive+no_connect"))
    )
    (net (code "410") (name "unconnected-(S_3_C3-NC2-Pad5)") (class "Default")
      (node (ref "S_3_C3") (pin "5") (pinfunction "NC2_5") (pintype "passive+no_connect"))
    )
    (net (code "411") (name "unconnected-(S_3_C3-NC3-Pad9)") (class "Default")
      (node (ref "S_3_C3") (pin "9") (pinfunction "NC3_9") (pintype "passive+no_connect"))
    )
    (net (code "412") (name "unconnected-(S_3_C3-NC4-Pad13)") (class "Default")
      (node (ref "S_3_C3") (pin "13") (pinfunction "NC4_13") (pintype "passive+no_connect"))
    )
    (net (code "413") (name "unconnected-(S_3_C4-NC1-Pad1)") (class "Default")
      (node (ref "S_3_C4") (pin "1") (pinfunction "NC1_1") (pintype "passive+no_connect"))
    )
    (net (code "414") (name "unconnected-(S_3_C4-NC2-Pad5)") (class "Default")
      (node (ref "S_3_C4") (pin "5") (pinfunction "NC2_5") (pintype "passive+no_connect"))
    )
    (net (code "415") (name "unconnected-(S_3_C4-NC3-Pad9)") (class "Default")
      (node (ref "S_3_C4") (pin "9") (pinfunction "NC3_9") (pintype "passive+no_connect"))
    )
    (net (code "416") (name "unconnected-(S_3_C4-NC4-Pad13)") (class "Default")
      (node (ref "S_3_C4") (pin "13") (pinfunction "NC4_13") (pintype "passive+no_connect"))
    )
    (net (code "417") (name "unconnected-(S_3_C5-NC1-Pad1)") (class "Default")
      (node (ref "S_3_C5") (pin "1") (pinfunction "NC1_1") (pintype "passive+no_connect"))
    )
    (net (code "418") (name "unconnected-(S_3_C5-NC2-Pad5)") (class "Default")
      (node (ref "S_3_C5") (pin "5") (pinfunction "NC2_5") (pintype "passive+no_connect"))
    )
    (net (code "419") (name "unconnected-(S_3_C5-NC3-Pad9)") (class "Default")
      (node (ref "S_3_C5") (pin "9") (pinfunction "NC3_9") (pintype "passive+no_connect"))
    )
    (net (code "420") (name "unconnected-(S_3_C5-NC4-Pad13)") (class "Default")
      (node (ref "S_3_C5") (pin "13") (pinfunction "NC4_13") (pintype "passive+no_connect"))
    )
    (net (code "421") (name "unconnected-(S_3_C6-NC1-Pad1)") (class "Default")
      (node (ref "S_3_C6") (pin "1") (pinfunction "NC1_1") (pintype "passive+no_connect"))
    )
    (net (code "422") (name "unconnected-(S_3_C6-NC2-Pad5)") (class "Default")
      (node (ref "S_3_C6") (pin "5") (pinfunction "NC2_5") (pintype "passive+no_connect"))
    )
    (net (code "423") (name "unconnected-(S_3_C6-NC3-Pad9)") (class "Default")
      (node (ref "S_3_C6") (pin "9") (pinfunction "NC3_9") (pintype "passive+no_connect"))
    )
    (net (code "424") (name "unconnected-(S_3_C6-NC4-Pad13)") (class "Default")
      (node (ref "S_3_C6") (pin "13") (pinfunction "NC4_13") (pintype "passive+no_connect"))
    )
    (net (code "425") (name "unconnected-(S_4_C1-NC1-Pad1)") (class "Default")
      (node (ref "S_4_C1") (pin "1") (pinfunction "NC1_1") (pintype "passive+no_connect"))
    )
    (net (code "426") (name "unconnected-(S_4_C1-NC2-Pad5)") (class "Default")
      (node (ref "S_4_C1") (pin "5") (pinfunction "NC2_5") (pintype "passive+no_connect"))
    )
    (net (code "427") (name "unconnected-(S_4_C1-NC3-Pad9)") (class "Default")
      (node (ref "S_4_C1") (pin "9") (pinfunction "NC3_9") (pintype "passive+no_connect"))
    )
    (net (code "428") (name "unconnected-(S_4_C1-NC4-Pad13)") (class "Default")
      (node (ref "S_4_C1") (pin "13") (pinfunction "NC4_13") (pintype "passive+no_connect"))
    )
    (net (code "429") (name "unconnected-(S_4_C2-NC1-Pad1)") (class "Default")
      (node (ref "S_4_C2") (pin "1") (pinfunction "NC1_1") (pintype "passive+no_connect"))
    )
    (net (code "430") (name "unconnected-(S_4_C2-NC2-Pad5)") (class "Default")
      (node (ref "S_4_C2") (pin "5") (pinfunction "NC2_5") (pintype "passive+no_connect"))
    )
    (net (code "431") (name "unconnected-(S_4_C2-NC3-Pad9)") (class "Default")
      (node (ref "S_4_C2") (pin "9") (pinfunction "NC3_9") (pintype "passive+no_connect"))
    )
    (net (code "432") (name "unconnected-(S_4_C2-NC4-Pad13)") (class "Default")
      (node (ref "S_4_C2") (pin "13") (pinfunction "NC4_13") (pintype "passive+no_connect"))
    )
    (net (code "433") (name "unconnected-(S_4_C3-NC1-Pad1)") (class "Default")
      (node (ref "S_4_C3") (pin "1") (pinfunction "NC1_1") (pintype "passive+no_connect"))
    )
    (net (code "434") (name "unconnected-(S_4_C3-NC2-Pad5)") (class "Default")
      (node (ref "S_4_C3") (pin "5") (pinfunction "NC2_5") (pintype "passive+no_connect"))
    )
    (net (code "435") (name "unconnected-(S_4_C3-NC3-Pad9)") (class "Default")
      (node (ref "S_4_C3") (pin "9") (pinfunction "NC3_9") (pintype "passive+no_connect"))
    )
    (net (code "436") (name "unconnected-(S_4_C3-NC4-Pad13)") (class "Default")
      (node (ref "S_4_C3") (pin "13") (pinfunction "NC4_13") (pintype "passive+no_connect"))
    )
    (net (code "437") (name "unconnected-(S_4_C4-NC1-Pad1)") (class "Default")
      (node (ref "S_4_C4") (pin "1") (pinfunction "NC1_1") (pintype "passive+no_connect"))
    )
    (net (code "438") (name "unconnected-(S_4_C4-NC2-Pad5)") (class "Default")
      (node (ref "S_4_C4") (pin "5") (pinfunction "NC2_5") (pintype "passive+no_connect"))
    )
    (net (code "439") (name "unconnected-(S_4_C4-NC3-Pad9)") (class "Default")
      (node (ref "S_4_C4") (pin "9") (pinfunction "NC3_9") (pintype "passive+no_connect"))
    )
    (net (code "440") (name "unconnected-(S_4_C4-NC4-Pad13)") (class "Default")
      (node (ref "S_4_C4") (pin "13") (pinfunction "NC4_13") (pintype "passive+no_connect"))
    )
    (net (code "441") (name "unconnected-(S_4_C5-NC1-Pad1)") (class "Default")
      (node (ref "S_4_C5") (pin "1") (pinfunction "NC1_1") (pintype "passive+no_connect"))
    )
    (net (code "442") (name "unconnected-(S_4_C5-NC2-Pad5)") (class "Default")
      (node (ref "S_4_C5") (pin "5") (pinfunction "NC2_5") (pintype "passive+no_connect"))
    )
    (net (code "443") (name "unconnected-(S_4_C5-NC3-Pad9)") (class "Default")
      (node (ref "S_4_C5") (pin "9") (pinfunction "NC3_9") (pintype "passive+no_connect"))
    )
    (net (code "444") (name "unconnected-(S_4_C5-NC4-Pad13)") (class "Default")
      (node (ref "S_4_C5") (pin "13") (pinfunction "NC4_13") (pintype "passive+no_connect"))
    )
    (net (code "445") (name "unconnected-(S_4_C6-NC1-Pad1)") (class "Default")
      (node (ref "S_4_C6") (pin "1") (pinfunction "NC1_1") (pintype "passive+no_connect"))
    )
    (net (code "446") (name "unconnected-(S_4_C6-NC2-Pad5)") (class "Default")
      (node (ref "S_4_C6") (pin "5") (pinfunction "NC2_5") (pintype "passive+no_connect"))
    )
    (net (code "447") (name "unconnected-(S_4_C6-NC3-Pad9)") (class "Default")
      (node (ref "S_4_C6") (pin "9") (pinfunction "NC3_9") (pintype "passive+no_connect"))
    )
    (net (code "448") (name "unconnected-(S_4_C6-NC4-Pad13)") (class "Default")
      (node (ref "S_4_C6") (pin "13") (pinfunction "NC4_13") (pintype "passive+no_connect"))
    )
    (net (code "449") (name "unconnected-(U6-PA0-WKUP-Pad10)") (class "Default")
      (node (ref "U6") (pin "10") (pinfunction "PA0-WKUP_10") (pintype "bidirectional"))
    )
    (net (code "450") (name "unconnected-(U6-PA1-Pad11)") (class "Default")
      (node (ref "U6") (pin "11") (pinfunction "PA1_11") (pintype "bidirectional"))
    )
    (net (code "451") (name "unconnected-(U6-PA4-Pad14)") (class "Default")
      (node (ref "U6") (pin "14") (pinfunction "PA4_14") (pintype "bidirectional"))
    )
    (net (code "452") (name "unconnected-(U6-PA5-Pad15)") (class "Default")
      (node (ref "U6") (pin "15") (pinfunction "PA5_15") (pintype "bidirectional"))
    )
    (net (code "453") (name "unconnected-(U6-PA6-Pad16)") (class "Default")
      (node (ref "U6") (pin "16") (pinfunction "PA6_16") (pintype "bidirectional"))
    )
    (net (code "454") (name "unconnected-(U6-PA12-Pad33)") (class "Default")
      (node (ref "U6") (pin "33") (pinfunction "PA12_33") (pintype "bidirectional"))
    )
    (net (code "455") (name "unconnected-(U6-PA15{slash}JTDI-Pad38)") (class "Default")
      (node (ref "U6") (pin "38") (pinfunction "PA15/JTDI_38") (pintype "bidirectional"))
    )
    (net (code "456") (name "unconnected-(U6-PB0-Pad18)") (class "Default")
      (node (ref "U6") (pin "18") (pinfunction "PB0_18") (pintype "bidirectional"))
    )
    (net (code "457") (name "unconnected-(U6-PB1-Pad19)") (class "Default")
      (node (ref "U6") (pin "19") (pinfunction "PB1_19") (pintype "bidirectional"))
    )
    (net (code "458") (name "unconnected-(U6-PB3{slash}JTDO-Pad39)") (class "Default")
      (node (ref "U6") (pin "39") (pinfunction "PB3/JTDO_39") (pintype "bidirectional"))
    )
    (net (code "459") (name "unconnected-(U6-PB4{slash}JNTRST-Pad40)") (class "Default")
      (node (ref "U6") (pin "40") (pinfunction "PB4/JNTRST_40") (pintype "bidirectional"))
    )
    (net (code "460") (name "unconnected-(U6-PB5-Pad41)") (class "Default")
      (node (ref "U6") (pin "41") (pinfunction "PB5_41") (pintype "bidirectional"))
    )
    (net (code "461") (name "unconnected-(U6-PB12-Pad25)") (class "Default")
      (node (ref "U6") (pin "25") (pinfunction "PB12_25") (pintype "bidirectional"))
    )
    (net (code "462") (name "unconnected-(U6-PB13-Pad26)") (class "Default")
      (node (ref "U6") (pin "26") (pinfunction "PB13_26") (pintype "bidirectional"))
    )
    (net (code "463") (name "unconnected-(U6-PC13-TAMPER-RTC-Pad2)") (class "Default")
      (node (ref "U6") (pin "2") (pinfunction "PC13-TAMPER-RTC_2") (pintype "bidirectional"))
    )
    (net (code "464") (name "unconnected-(U15-QH'-Pad9)") (class "Default")
      (node (ref "U15") (pin "9") (pinfunction "QH'_9") (pintype "passive+no_connect"))
    )
    (net (code "465") (name "unconnected-(Y1-GROUND-Pad2)") (class "Default")
      (node (ref "Y1") (pin "2") (pinfunction "GROUND_2") (pintype "passive"))
    )
    (net (code "466") (name "unconnected-(Y1-GROUND-Pad4)") (class "Default")
      (node (ref "Y1") (pin "4") (pinfunction "GROUND_4") (pintype "passive"))
    )
  )
)
